# 1_4.net
KiCad netlist of a schematic drawn in Altium Designer
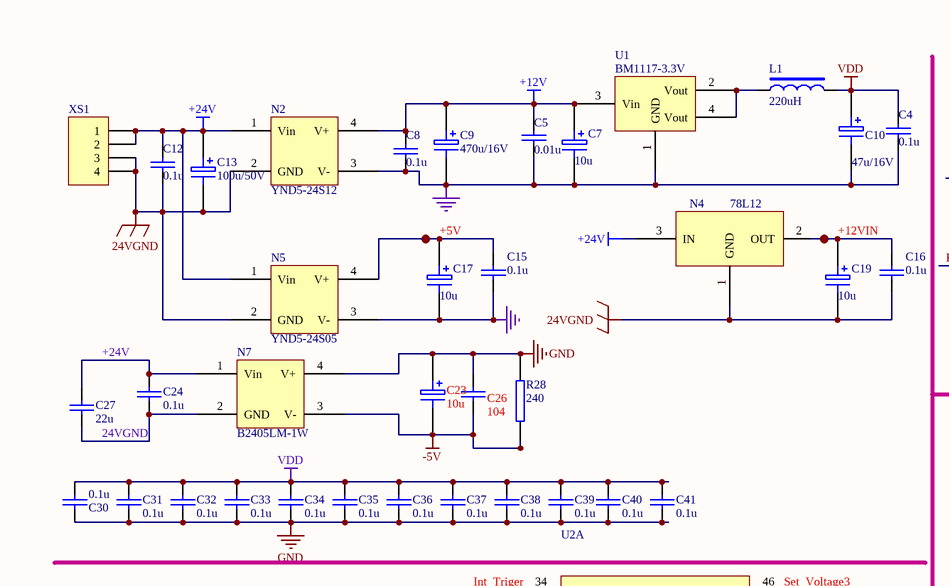
[diagram p0: 总控制板1控4.SchDoc, top left]
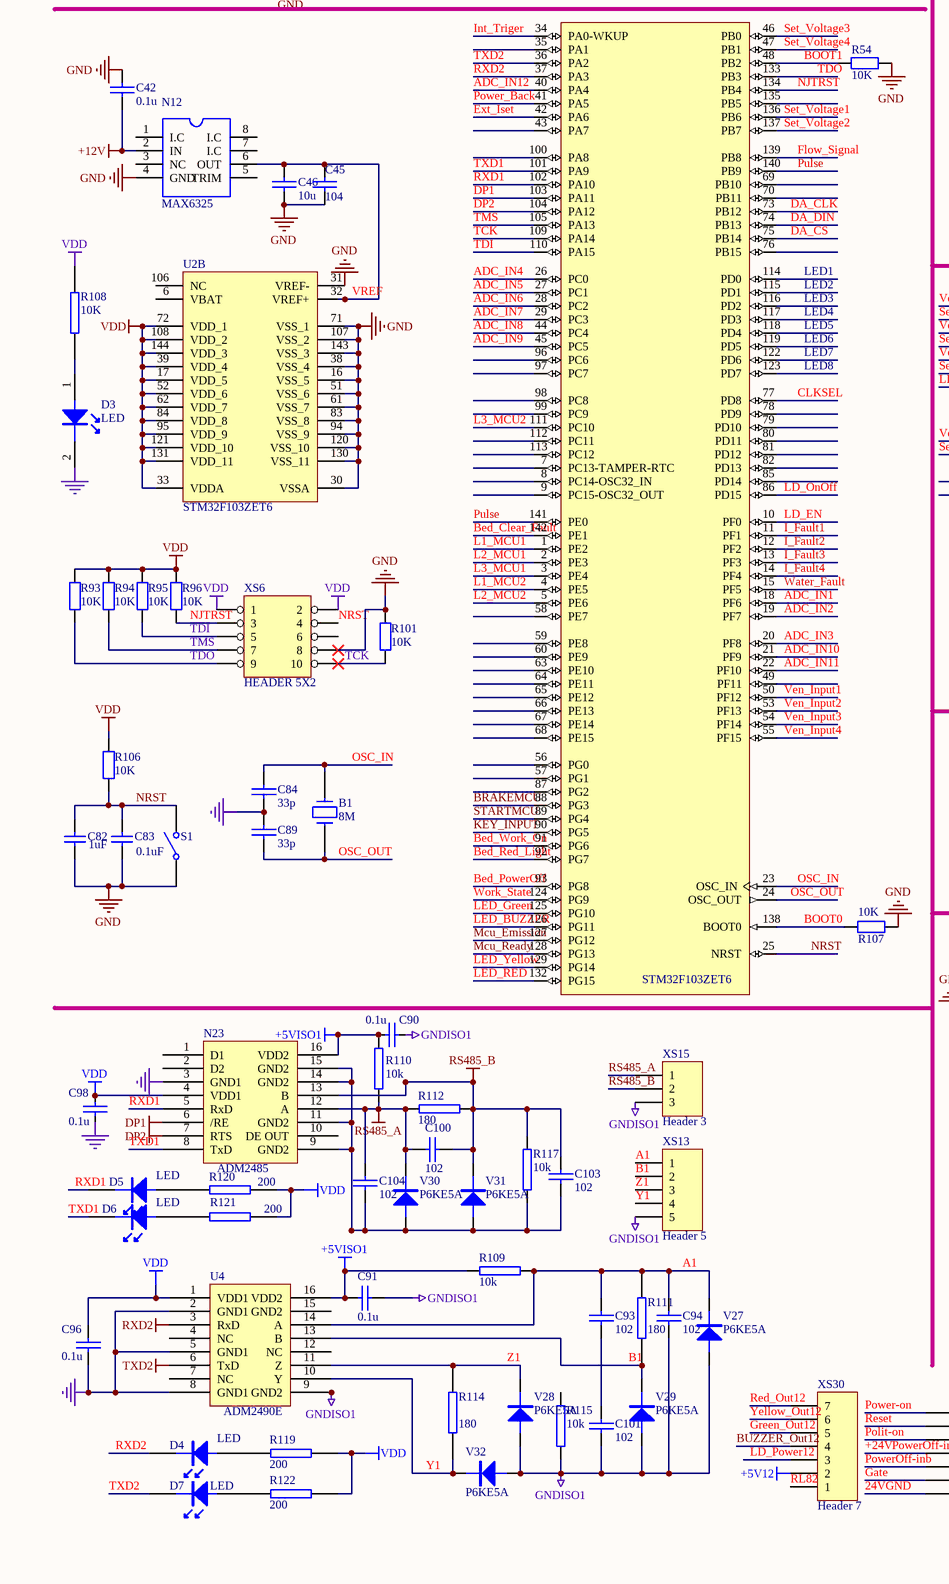
[diagram p1: 总控制板1控4.SchDoc, bottom left]
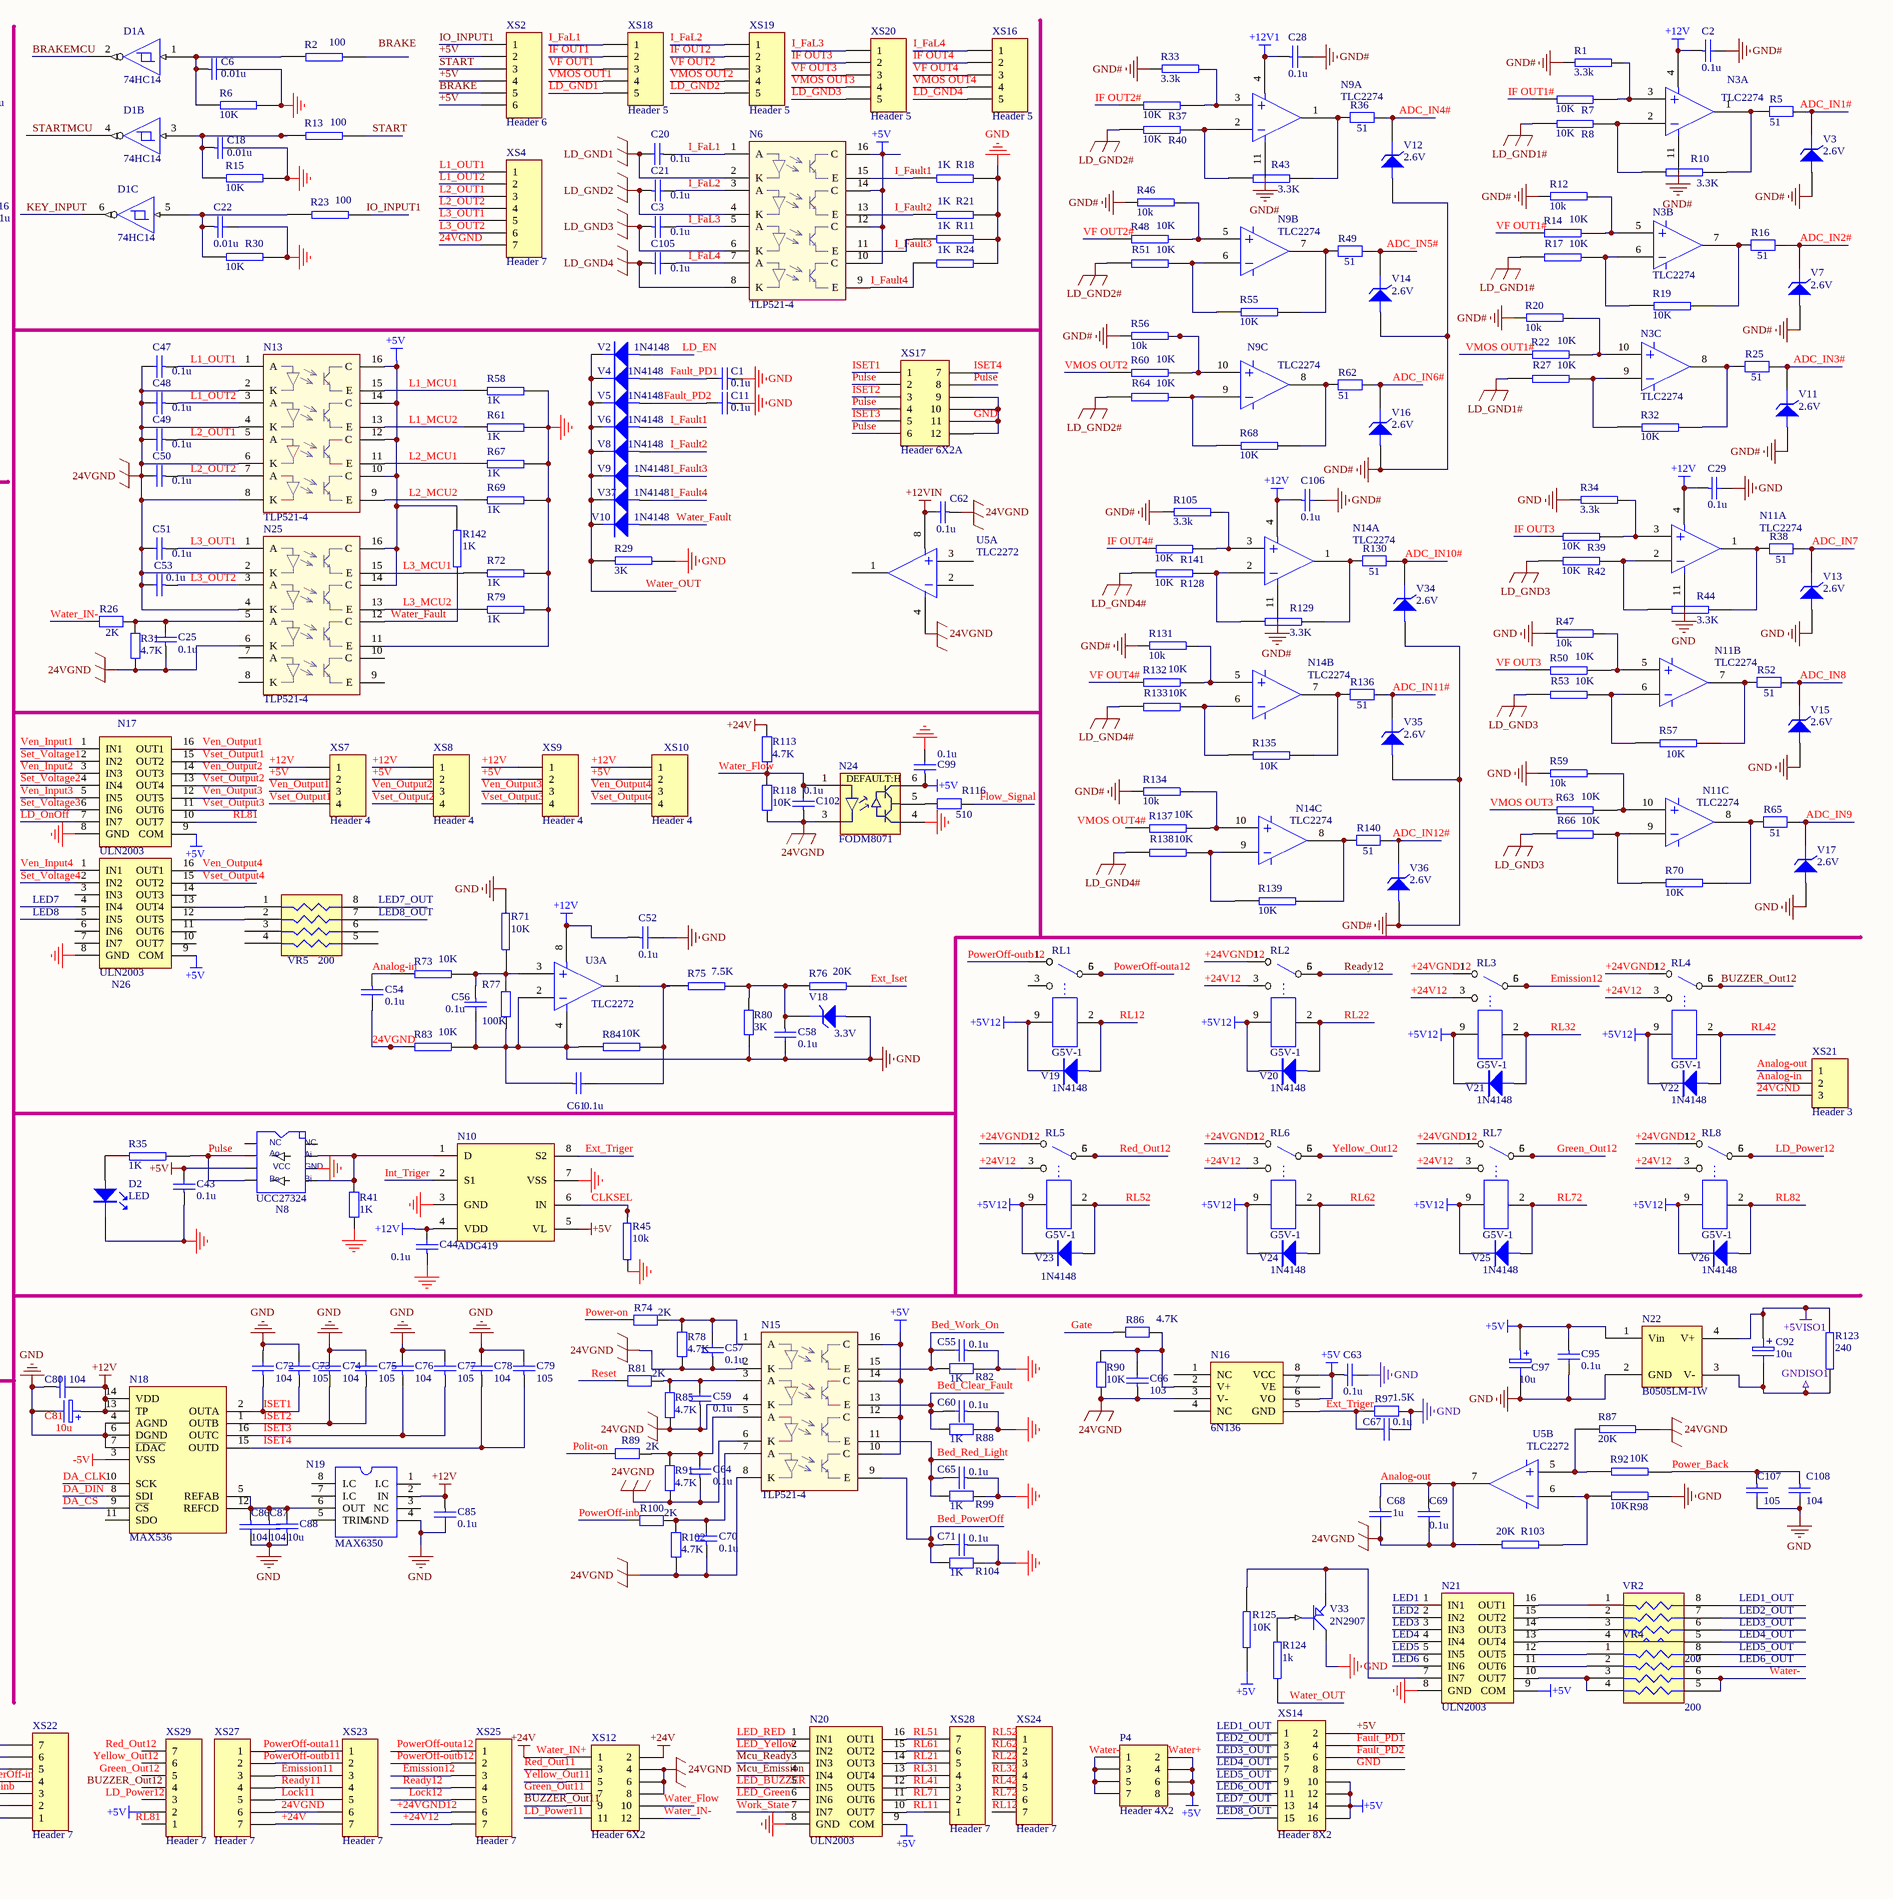
[diagram p2: 总控制板1控4.SchDoc, bottom right]

(export (version "E")
  (design (tool "Eeschema 10.0.6"))
  (components
    (comp (ref "B1")
      (value "8M")
      (footprint "CRY_SMB")
      (description "Crystal")
      (libsource (lib "*") (part "CRYSTAL"))
    )
    (comp (ref "C1") (value "0.1u") (footprint "0805") (libsource (lib "") (part "CAP_1")))
    (comp (ref "C2")
      (value "0.1u")
      (footprint "0805")
      (description "Capacitor")
      (libsource (lib "*") (part "CAP"))
    )
    (comp (ref "C3")
      (value "0.1u")
      (footprint "0805")
      (description "Capacitor")
      (libsource (lib "*") (part "CAP"))
    )
    (comp (ref "C4")
      (value "0.1u")
      (footprint "0805")
      (description "Capacitor")
      (libsource (lib "*") (part "CAP"))
    )
    (comp (ref "C5")
      (value "0.01u")
      (footprint "0805")
      (description "Capacitor")
      (libsource (lib "*") (part "CAP"))
    )
    (comp (ref "C6")
      (value "0.01u")
      (footprint "0805")
      (description "Capacitor")
      (libsource (lib "*") (part "CAP"))
    )
    (comp (ref "C7")
      (value "10u")
      (footprint "1206")
      (description "Electrolytic Capacitor")
      (libsource (lib "*") (part "ELECTRO1"))
    )
    (comp (ref "C8")
      (value "0.1u")
      (footprint "0805")
      (description "Capacitor")
      (libsource (lib "*") (part "CAP"))
    )
    (comp (ref "C9")
      (value "470u/16V")
      (footprint "3008")
      (description "Electrolytic Capacitor")
      (libsource (lib "*") (part "ELECTRO1"))
    )
    (comp (ref "C10")
      (value "47u/16V")
      (footprint "1206")
      (description "Electrolytic Capacitor")
      (libsource (lib "*") (part "ELECTRO1"))
    )
    (comp (ref "C11") (value "0.1u") (footprint "0805") (libsource (lib "") (part "CAP_1")))
    (comp (ref "C12")
      (value "0.1u")
      (footprint "0805")
      (description "Capacitor")
      (libsource (lib "*") (part "CAP"))
    )
    (comp (ref "C13")
      (value "100u/50V")
      (footprint "CD5-8")
      (description "Electrolytic Capacitor")
      (libsource (lib "*") (part "ELECTRO1"))
    )
    (comp (ref "C15") (value "0.1u") (footprint "0805") (libsource (lib "") (part "CAP_1")))
    (comp (ref "C16") (value "0.1u") (footprint "0805") (libsource (lib "") (part "CAP_1")))
    (comp (ref "C17")
      (value "10u")
      (footprint "1206")
      (description "Electrolytic Capacitor")
      (libsource (lib "*") (part "ELECTRO1"))
    )
    (comp (ref "C18")
      (value "0.01u")
      (footprint "0805")
      (description "Capacitor")
      (libsource (lib "*") (part "CAP"))
    )
    (comp (ref "C19")
      (value "10u")
      (footprint "1206")
      (description "Electrolytic Capacitor")
      (libsource (lib "*") (part "ELECTRO1"))
    )
    (comp (ref "C20")
      (value "0.1u")
      (footprint "0805")
      (description "Capacitor")
      (libsource (lib "*") (part "CAP"))
    )
    (comp (ref "C21")
      (value "0.1u")
      (footprint "0805")
      (description "Capacitor")
      (libsource (lib "*") (part "CAP"))
    )
    (comp (ref "C22")
      (value "0.01u")
      (footprint "0805")
      (description "Capacitor")
      (libsource (lib "*") (part "CAP"))
    )
    (comp (ref "C23")
      (value "10u")
      (footprint "1206")
      (description "Electrolytic Capacitor")
      (libsource (lib "*") (part "ELECTRO1"))
    )
    (comp (ref "C24")
      (value "0.1u")
      (footprint "0805")
      (description "Capacitor")
      (libsource (lib "*") (part "CAP"))
    )
    (comp (ref "C25") (value "0.1u") (footprint "0805") (libsource (lib "") (part "CAP_1")))
    (comp (ref "C26")
      (value "104")
      (footprint "0805")
      (description "Capacitor")
      (libsource (lib "*") (part "CAP"))
    )
    (comp (ref "C27")
      (value "22u")
      (footprint "1206")
      (description "Capacitor")
      (libsource (lib "*") (part "CAP"))
    )
    (comp (ref "C28")
      (value "0.1u")
      (footprint "0805")
      (description "Capacitor")
      (libsource (lib "*") (part "CAP"))
    )
    (comp (ref "C29")
      (value "0.1u")
      (footprint "0805")
      (description "Capacitor")
      (libsource (lib "*") (part "CAP"))
    )
    (comp (ref "C30")
      (value "0.1u")
      (footprint "0805")
      (description "Capacitor")
      (libsource (lib "*") (part "CAP"))
    )
    (comp (ref "C31")
      (value "0.1u")
      (footprint "0805")
      (description "Capacitor")
      (libsource (lib "*") (part "CAP"))
    )
    (comp (ref "C32")
      (value "0.1u")
      (footprint "0805")
      (description "Capacitor")
      (libsource (lib "*") (part "CAP"))
    )
    (comp (ref "C33")
      (value "0.1u")
      (footprint "0805")
      (description "Capacitor")
      (libsource (lib "*") (part "CAP"))
    )
    (comp (ref "C34")
      (value "0.1u")
      (footprint "0805")
      (description "Capacitor")
      (libsource (lib "*") (part "CAP"))
    )
    (comp (ref "C35")
      (value "0.1u")
      (footprint "0805")
      (description "Capacitor")
      (libsource (lib "*") (part "CAP"))
    )
    (comp (ref "C36")
      (value "0.1u")
      (footprint "0805")
      (description "Capacitor")
      (libsource (lib "*") (part "CAP"))
    )
    (comp (ref "C37")
      (value "0.1u")
      (footprint "0805")
      (description "Capacitor")
      (libsource (lib "*") (part "CAP"))
    )
    (comp (ref "C38")
      (value "0.1u")
      (footprint "0805")
      (description "Capacitor")
      (libsource (lib "*") (part "CAP"))
    )
    (comp (ref "C39")
      (value "0.1u")
      (footprint "0805")
      (description "Capacitor")
      (libsource (lib "*") (part "CAP"))
    )
    (comp (ref "C40")
      (value "0.1u")
      (footprint "0805")
      (description "Capacitor")
      (libsource (lib "*") (part "CAP"))
    )
    (comp (ref "C41")
      (value "0.1u")
      (footprint "0805")
      (description "Capacitor")
      (libsource (lib "*") (part "CAP"))
    )
    (comp (ref "C42") (value "0.1u") (footprint "0805") (libsource (lib "") (part "CAP_1")))
    (comp (ref "C43") (value "0.1u") (footprint "0805") (libsource (lib "") (part "CAP_1")))
    (comp (ref "C44") (value "0.1u") (footprint "0805") (libsource (lib "") (part "CAP_1")))
    (comp (ref "C45") (value "104") (footprint "0805") (libsource (lib "THT") (part "CAP")))
    (comp (ref "C46") (value "10u") (footprint "0805") (libsource (lib "") (part "CAP_1")))
    (comp (ref "C47")
      (value "0.1u")
      (footprint "0805")
      (description "Capacitor")
      (libsource (lib "*") (part "CAP"))
    )
    (comp (ref "C48")
      (value "0.1u")
      (footprint "0805")
      (description "Capacitor")
      (libsource (lib "*") (part "CAP"))
    )
    (comp (ref "C49")
      (value "0.1u")
      (footprint "0805")
      (description "Capacitor")
      (libsource (lib "*") (part "CAP"))
    )
    (comp (ref "C50")
      (value "0.1u")
      (footprint "0805")
      (description "Capacitor")
      (libsource (lib "*") (part "CAP"))
    )
    (comp (ref "C51")
      (value "0.1u")
      (footprint "0805")
      (description "Capacitor")
      (libsource (lib "*") (part "CAP"))
    )
    (comp (ref "C52")
      (value "0.1u")
      (footprint "0805")
      (description "Capacitor")
      (libsource (lib "*") (part "CAP"))
    )
    (comp (ref "C53")
      (value "0.1u")
      (footprint "0805")
      (description "Capacitor")
      (libsource (lib "*") (part "CAP"))
    )
    (comp (ref "C54")
      (value "0.1u")
      (footprint "0805")
      (description "Capacitor")
      (libsource (lib "*") (part "CAP"))
    )
    (comp (ref "C55") (value "0.1u") (footprint "0805") (libsource (lib "") (part "CAP_1")))
    (comp (ref "C56")
      (value "0.1u")
      (footprint "0805")
      (description "Capacitor")
      (libsource (lib "*") (part "CAP"))
    )
    (comp (ref "C57") (value "0.1u") (footprint "0805") (libsource (lib "") (part "CAP_1")))
    (comp (ref "C58")
      (value "0.1u")
      (footprint "0805")
      (description "Capacitor")
      (libsource (lib "*") (part "CAP"))
    )
    (comp (ref "C59") (value "0.1u") (footprint "0805") (libsource (lib "") (part "CAP_1")))
    (comp (ref "C60") (value "0.1u") (footprint "0805") (libsource (lib "") (part "CAP_1")))
    (comp (ref "C61")
      (value "0.1u")
      (footprint "0805")
      (description "Capacitor")
      (libsource (lib "*") (part "CAP"))
    )
    (comp (ref "C62")
      (value "0.1u")
      (footprint "0805")
      (description "Capacitor")
      (libsource (lib "*") (part "CAP"))
    )
    (comp (ref "C63")
      (value "0.1u")
      (footprint "0805")
      (description "Capacitor")
      (libsource (lib "*") (part "CAP"))
    )
    (comp (ref "C64") (value "0.1u") (footprint "0805") (libsource (lib "") (part "CAP_1")))
    (comp (ref "C65") (value "0.1u") (footprint "0805") (libsource (lib "") (part "CAP_1")))
    (comp (ref "C66") (value "103") (footprint "0805") (libsource (lib "") (part "CAP_1")))
    (comp (ref "C67") (value "0.1u") (footprint "0805") (libsource (lib "") (part "CAP_1")))
    (comp (ref "C68")
      (value "1u")
      (footprint "0805")
      (description "Capacitor")
      (libsource (lib "*") (part "CAP"))
    )
    (comp (ref "C69")
      (value "0.1u")
      (footprint "0805")
      (description "Capacitor")
      (libsource (lib "*") (part "CAP"))
    )
    (comp (ref "C70") (value "0.1u") (footprint "0805") (libsource (lib "") (part "CAP_1")))
    (comp (ref "C71") (value "0.1u") (footprint "0805") (libsource (lib "") (part "CAP_1")))
    (comp (ref "C72") (value "104") (footprint "0805") (libsource (lib "THT") (part "CAP")))
    (comp (ref "C73") (value "105") (footprint "0805") (libsource (lib "THT") (part "CAP")))
    (comp (ref "C74") (value "104") (footprint "0805") (libsource (lib "THT") (part "CAP")))
    (comp (ref "C75") (value "105") (footprint "0805") (libsource (lib "THT") (part "CAP")))
    (comp (ref "C76") (value "104") (footprint "0805") (libsource (lib "THT") (part "CAP")))
    (comp (ref "C77") (value "105") (footprint "0805") (libsource (lib "THT") (part "CAP")))
    (comp (ref "C78") (value "104") (footprint "0805") (libsource (lib "THT") (part "CAP")))
    (comp (ref "C79") (value "105") (footprint "0805") (libsource (lib "THT") (part "CAP")))
    (comp (ref "C80") (value "104") (footprint "0805") (libsource (lib "THT") (part "CAP")))
    (comp (ref "C81")
      (value "10u")
      (footprint "1206")
      (description "Electrolytic Capacitor")
      (libsource (lib "*") (part "ELECTRO1"))
    )
    (comp (ref "C82")
      (value "1uF")
      (footprint "0805")
      (description "Capacitor")
      (fields (field (name "PUBLISHER") "Altium Limited"))
      (libsource (lib "Miscellaneous Devices") (part "Cap"))
    )
    (comp (ref "C83")
      (value "0.1uF")
      (footprint "0805")
      (description "Capacitor")
      (fields (field (name "PUBLISHER") "Altium Limited"))
      (libsource (lib "Miscellaneous Devices") (part "Cap"))
    )
    (comp (ref "C84")
      (value "33p")
      (footprint "0805")
      (description "Capacitor")
      (libsource (lib "*") (part "CAP"))
    )
    (comp (ref "C85") (value "0.1u") (footprint "0805") (libsource (lib "") (part "CAP_1")))
    (comp (ref "C86") (value "104") (footprint "0805") (libsource (lib "THT") (part "CAP")))
    (comp (ref "C87") (value "104") (footprint "0805") (libsource (lib "THT") (part "CAP")))
    (comp (ref "C88") (value "10u") (footprint "0805") (libsource (lib "") (part "CAP_1")))
    (comp (ref "C89")
      (value "33p")
      (footprint "0805")
      (description "Capacitor")
      (libsource (lib "*") (part "CAP"))
    )
    (comp (ref "C90") (value "0.1u") (footprint "0805") (libsource (lib "") (part "CAP_2")))
    (comp (ref "C91")
      (value "0.1u")
      (footprint "0805")
      (description "Capacitor")
      (libsource (lib "*") (part "CAP"))
    )
    (comp (ref "C92")
      (value "10u")
      (footprint "1206")
      (description "Electrolytic Capacitor")
      (libsource (lib "*") (part "ELECTRO1"))
    )
    (comp (ref "C93")
      (value "102")
      (footprint "0805")
      (description "Capacitor")
      (libsource (lib "*") (part "CAP"))
    )
    (comp (ref "C94")
      (value "102")
      (footprint "0805")
      (description "Capacitor")
      (libsource (lib "*") (part "CAP"))
    )
    (comp (ref "C95")
      (value "0.1u")
      (footprint "0805")
      (description "Capacitor")
      (libsource (lib "*") (part "CAP"))
    )
    (comp (ref "C96")
      (value "0.1u")
      (footprint "0805")
      (description "Capacitor")
      (libsource (lib "*") (part "CAP"))
    )
    (comp (ref "C97")
      (value "10u")
      (footprint "1206")
      (description "Electrolytic Capacitor")
      (libsource (lib "*") (part "ELECTRO1"))
    )
    (comp (ref "C98") (value "0.1u") (footprint "0805") (libsource (lib "") (part "CAP_2")))
    (comp (ref "C99") (value "0.1u") (footprint "0805") (libsource (lib "") (part "CAP_1")))
    (comp (ref "C100")
      (value "102")
      (footprint "0805")
      (description "Capacitor")
      (libsource (lib "*") (part "CAP"))
    )
    (comp (ref "C101")
      (value "102")
      (footprint "0805")
      (description "Capacitor")
      (libsource (lib "*") (part "CAP"))
    )
    (comp (ref "C102") (value "0.1u") (footprint "0805") (libsource (lib "") (part "CAP_1")))
    (comp (ref "C103")
      (value "102")
      (footprint "0805")
      (description "Capacitor")
      (libsource (lib "*") (part "CAP"))
    )
    (comp (ref "C104")
      (value "102")
      (footprint "0805")
      (description "Capacitor")
      (libsource (lib "*") (part "CAP"))
    )
    (comp (ref "C105")
      (value "0.1u")
      (footprint "0805")
      (description "Capacitor")
      (libsource (lib "*") (part "CAP"))
    )
    (comp (ref "C106")
      (value "0.1u")
      (footprint "0805")
      (description "Capacitor")
      (libsource (lib "*") (part "CAP"))
    )
    (comp (ref "C107") (value "105") (footprint "0805") (libsource (lib "THT") (part "CAP")))
    (comp (ref "C108") (value "104") (footprint "0805") (libsource (lib "THT") (part "CAP")))
    (comp (ref "D1") (value "74HC14") (footprint "SO-14") (libsource (lib "*") (part "4584")))
    (comp (ref "D2") (value "LED") (footprint "1206A") (libsource (lib "*") (part "LED")))
    (comp (ref "D3") (value "LED") (footprint "1206A") (libsource (lib "") (part "LED_1")))
    (comp (ref "D4") (value "LED") (footprint "1206A") (libsource (lib "*") (part "LED")))
    (comp (ref "D5") (value "LED") (footprint "1206A") (libsource (lib "*") (part "LED")))
    (comp (ref "D6") (value "LED") (footprint "1206A") (libsource (lib "*") (part "LED")))
    (comp (ref "D7") (value "LED") (footprint "1206A") (libsource (lib "*") (part "LED")))
    (comp (ref "L1") (value "220uH") (footprint "1812") (libsource (lib "*") (part "L")))
    (comp (ref "N2") (value "YND5-24S12") (footprint "YND5") (libsource (lib "*") (part "B0505LM")))
    (comp (ref "N3") (value "TLC2274") (footprint "SO-14") (libsource (lib "*") (part "LM124")))
    (comp (ref "N4") (value "78L12") (footprint "TO-92_2") (libsource (lib "*") (part "VOL")))
    (comp (ref "N5") (value "YND5-24S05") (footprint "YND5") (libsource (lib "*") (part "B0505LM")))
    (comp (ref "N6")
      (value "TLP521-4")
      (footprint "ILEAD-16")
      (libsource (lib "work_ruilei") (part "TLP521-4"))
    )
    (comp (ref "N7") (value "B2405LM-1W") (footprint "B0505LM") (libsource (lib "*") (part "B0505LM")))
    (comp (ref "N8") (value "UCC27324") (footprint "SO-8") (libsource (lib "框图2") (part "UCC27324")))
    (comp (ref "N9") (value "TLC2274") (footprint "SO-14") (libsource (lib "*") (part "LM124")))
    (comp (ref "N10") (value "ADG419") (footprint "SO-8") (libsource (lib "40hz") (part "ADG419")))
    (comp (ref "N11") (value "TLC2274") (footprint "SO-14") (libsource (lib "*") (part "LM124")))
    (comp (ref "N12") (value "MAX6325") (footprint "SO-8") (libsource (lib "") (part "MAX6341_1")))
    (comp (ref "N13")
      (value "TLP521-4")
      (footprint "ILEAD-16")
      (libsource (lib "work_ruilei") (part "TLP521-4"))
    )
    (comp (ref "N14") (value "TLC2274") (footprint "SO-14") (libsource (lib "*") (part "LM124")))
    (comp (ref "N15")
      (value "TLP521-4")
      (footprint "ILEAD-16")
      (libsource (lib "work_ruilei") (part "TLP521-4"))
    )
    (comp (ref "N16") (value "6N136") (footprint "ILEAD-8") (libsource (lib "*") (part "HCPL2601")))
    (comp (ref "N17")
      (value "ULN2003")
      (footprint "SOIC127P600-16N")
      (libsource (lib "work_ruilei") (part "ULN2003A"))
    )
    (comp (ref "N18") (value "MAX536") (footprint "SOIC-16") (libsource (lib "work_ruilei") (part "MAX536")))
    (comp (ref "N19") (value "MAX6350") (footprint "SO-8") (libsource (lib "TH2") (part "MAX6341")))
    (comp (ref "N20")
      (value "ULN2003")
      (footprint "SOIC127P600-16N")
      (libsource (lib "work_ruilei") (part "ULN2003A"))
    )
    (comp (ref "N21")
      (value "ULN2003")
      (footprint "SOIC127P600-16N")
      (libsource (lib "work_ruilei") (part "ULN2003A"))
    )
    (comp (ref "N22") (value "B0505LM-1W") (footprint "B0505LM") (libsource (lib "*") (part "B0505LM")))
    (comp (ref "N23") (value "ADM2485") (footprint "SOIC-16") (libsource (lib "C8051F021") (part "ADM2485")))
    (comp (ref "N24") (value "FODM8071") (footprint "SO-8") (libsource (lib "work_ruilei") (part "FODM8071")))
    (comp (ref "N25")
      (value "TLP521-4")
      (footprint "ILEAD-16")
      (libsource (lib "work_ruilei") (part "TLP521-4"))
    )
    (comp (ref "N26")
      (value "ULN2003")
      (footprint "SOIC127P600-16N")
      (libsource (lib "work_ruilei") (part "ULN2003A"))
    )
    (comp (ref "P4")
      (value "Header 4X2")
      (footprint "HDR2X4")
      (description "Header, 4-Pin, Dual row")
      (fields (field (name "PUBLISHER") "Altium Limited"))
      (libsource (lib "Miscellaneous Connectors") (part "Header 4X2"))
    )
    (comp (ref "R1") (value "3.3k") (footprint "0805") (libsource (lib "*") (part "R")))
    (comp (ref "R2") (value "100") (footprint "0805") (libsource (lib "*") (part "RES2")))
    (comp (ref "R5")
      (value "51")
      (footprint "0805")
      (description "Resistor")
      (fields (field (name "PUBLISHER") "Altium Limited"))
      (libsource (lib "") (part "Res2_2"))
    )
    (comp (ref "R6") (value "10K") (footprint "0805") (libsource (lib "*") (part "RES2")))
    (comp (ref "R7") (value "10K") (footprint "0805") (libsource (lib "*") (part "RES2")))
    (comp (ref "R8") (value "10K") (footprint "0805") (libsource (lib "*") (part "RES2")))
    (comp (ref "R10") (value "3.3K") (footprint "0805") (libsource (lib "*") (part "RES2")))
    (comp (ref "R11") (value "1K") (footprint "0805") (libsource (lib "*") (part "RES2")))
    (comp (ref "R12") (value "10k") (footprint "0805") (libsource (lib "*") (part "R")))
    (comp (ref "R13") (value "100") (footprint "0805") (libsource (lib "*") (part "RES2")))
    (comp (ref "R14") (value "10K") (footprint "0805") (libsource (lib "*") (part "RES2")))
    (comp (ref "R15") (value "10K") (footprint "0805") (libsource (lib "*") (part "RES2")))
    (comp (ref "R16")
      (value "51")
      (footprint "0805")
      (description "Resistor")
      (fields (field (name "PUBLISHER") "Altium Limited"))
      (libsource (lib "") (part "Res2_2"))
    )
    (comp (ref "R17") (value "10K") (footprint "0805") (libsource (lib "*") (part "RES2")))
    (comp (ref "R18") (value "1K") (footprint "0805") (libsource (lib "*") (part "RES2")))
    (comp (ref "R19") (value "10K") (footprint "0805") (libsource (lib "*") (part "RES2")))
    (comp (ref "R20") (value "10k") (footprint "0805") (libsource (lib "*") (part "R")))
    (comp (ref "R21") (value "1K") (footprint "0805") (libsource (lib "*") (part "RES2")))
    (comp (ref "R22") (value "10K") (footprint "0805") (libsource (lib "*") (part "RES2")))
    (comp (ref "R23") (value "100") (footprint "0805") (libsource (lib "*") (part "RES2")))
    (comp (ref "R24") (value "1K") (footprint "0805") (libsource (lib "*") (part "RES2")))
    (comp (ref "R25")
      (value "51")
      (footprint "0805")
      (description "Resistor")
      (fields (field (name "PUBLISHER") "Altium Limited"))
      (libsource (lib "") (part "Res2_2"))
    )
    (comp (ref "R26")
      (value "2K")
      (footprint "0805")
      (description "Resistor")
      (fields (field (name "PUBLISHER") "Altium Limited"))
      (libsource (lib "") (part "Res2_2"))
    )
    (comp (ref "R27") (value "10K") (footprint "0805") (libsource (lib "*") (part "RES2")))
    (comp (ref "R28") (value "240") (footprint "1206") (libsource (lib "*") (part "RES2")))
    (comp (ref "R29") (value "3K") (footprint "0805") (libsource (lib "*") (part "RES2")))
    (comp (ref "R30") (value "10K") (footprint "0805") (libsource (lib "*") (part "RES2")))
    (comp (ref "R31")
      (value "4.7K")
      (footprint "0805")
      (description "Resistor")
      (fields (field (name "PUBLISHER") "Altium Limited"))
      (libsource (lib "Miscellaneous Devices") (part "Res2"))
    )
    (comp (ref "R32") (value "10K") (footprint "0805") (libsource (lib "*") (part "RES2")))
    (comp (ref "R33") (value "3.3k") (footprint "0805") (libsource (lib "*") (part "R")))
    (comp (ref "R34") (value "3.3k") (footprint "0805") (libsource (lib "*") (part "R")))
    (comp (ref "R35") (value "1K") (footprint "0805") (libsource (lib "*") (part "RES2")))
    (comp (ref "R36")
      (value "51")
      (footprint "0805")
      (description "Resistor")
      (fields (field (name "PUBLISHER") "Altium Limited"))
      (libsource (lib "") (part "Res2_2"))
    )
    (comp (ref "R37") (value "10K") (footprint "0805") (libsource (lib "*") (part "RES2")))
    (comp (ref "R38")
      (value "51")
      (footprint "0805")
      (description "Resistor")
      (fields (field (name "PUBLISHER") "Altium Limited"))
      (libsource (lib "") (part "Res2_2"))
    )
    (comp (ref "R39") (value "10K") (footprint "0805") (libsource (lib "*") (part "RES2")))
    (comp (ref "R40") (value "10K") (footprint "0805") (libsource (lib "*") (part "RES2")))
    (comp (ref "R41")
      (value "1K")
      (footprint "0805")
      (description "Resistor")
      (fields (field (name "PUBLISHER") "Altium Limited"))
      (libsource (lib "Miscellaneous Devices") (part "Res2"))
    )
    (comp (ref "R42") (value "10K") (footprint "0805") (libsource (lib "*") (part "RES2")))
    (comp (ref "R43") (value "3.3K") (footprint "0805") (libsource (lib "*") (part "RES2")))
    (comp (ref "R44") (value "3.3K") (footprint "0805") (libsource (lib "*") (part "RES2")))
    (comp (ref "R45") (value "10k") (footprint "0805") (libsource (lib "") (part "R_1")))
    (comp (ref "R46") (value "10k") (footprint "0805") (libsource (lib "*") (part "R")))
    (comp (ref "R47") (value "10k") (footprint "0805") (libsource (lib "*") (part "R")))
    (comp (ref "R48") (value "10K") (footprint "0805") (libsource (lib "*") (part "RES2")))
    (comp (ref "R49")
      (value "51")
      (footprint "0805")
      (description "Resistor")
      (fields (field (name "PUBLISHER") "Altium Limited"))
      (libsource (lib "") (part "Res2_2"))
    )
    (comp (ref "R50") (value "10K") (footprint "0805") (libsource (lib "*") (part "RES2")))
    (comp (ref "R51") (value "10K") (footprint "0805") (libsource (lib "*") (part "RES2")))
    (comp (ref "R52")
      (value "51")
      (footprint "0805")
      (description "Resistor")
      (fields (field (name "PUBLISHER") "Altium Limited"))
      (libsource (lib "") (part "Res2_2"))
    )
    (comp (ref "R53") (value "10K") (footprint "0805") (libsource (lib "*") (part "RES2")))
    (comp (ref "R54")
      (value "10K")
      (footprint "0805")
      (description "Resistor")
      (fields (field (name "PUBLISHER") "Altium Limited"))
      (libsource (lib "") (part "Res2_2"))
    )
    (comp (ref "R55") (value "10K") (footprint "0805") (libsource (lib "*") (part "RES2")))
    (comp (ref "R56") (value "10k") (footprint "0805") (libsource (lib "*") (part "R")))
    (comp (ref "R57") (value "10K") (footprint "0805") (libsource (lib "*") (part "RES2")))
    (comp (ref "R58") (value "1K") (footprint "0805") (libsource (lib "*") (part "RES2")))
    (comp (ref "R59") (value "10k") (footprint "0805") (libsource (lib "*") (part "R")))
    (comp (ref "R60") (value "10K") (footprint "0805") (libsource (lib "*") (part "RES2")))
    (comp (ref "R61") (value "1K") (footprint "0805") (libsource (lib "*") (part "RES2")))
    (comp (ref "R62")
      (value "51")
      (footprint "0805")
      (description "Resistor")
      (fields (field (name "PUBLISHER") "Altium Limited"))
      (libsource (lib "") (part "Res2_2"))
    )
    (comp (ref "R63") (value "10K") (footprint "0805") (libsource (lib "*") (part "RES2")))
    (comp (ref "R64") (value "10K") (footprint "0805") (libsource (lib "*") (part "RES2")))
    (comp (ref "R65")
      (value "51")
      (footprint "0805")
      (description "Resistor")
      (fields (field (name "PUBLISHER") "Altium Limited"))
      (libsource (lib "") (part "Res2_2"))
    )
    (comp (ref "R66") (value "10K") (footprint "0805") (libsource (lib "*") (part "RES2")))
    (comp (ref "R67") (value "1K") (footprint "0805") (libsource (lib "*") (part "RES2")))
    (comp (ref "R68") (value "10K") (footprint "0805") (libsource (lib "*") (part "RES2")))
    (comp (ref "R69") (value "1K") (footprint "0805") (libsource (lib "*") (part "RES2")))
    (comp (ref "R70") (value "10K") (footprint "0805") (libsource (lib "*") (part "RES2")))
    (comp (ref "R71") (value "10K") (footprint "0805") (libsource (lib "*") (part "RES2")))
    (comp (ref "R72") (value "1K") (footprint "0805") (libsource (lib "*") (part "RES2")))
    (comp (ref "R73") (value "10K") (footprint "0805") (libsource (lib "*") (part "RES2")))
    (comp (ref "R74")
      (value "2K")
      (footprint "0805")
      (description "Resistor")
      (fields (field (name "PUBLISHER") "Altium Limited"))
      (libsource (lib "") (part "Res2_2"))
    )
    (comp (ref "R75") (value "7.5K") (footprint "0805") (libsource (lib "*") (part "RES2")))
    (comp (ref "R76") (value "20K") (footprint "0805") (libsource (lib "*") (part "RES2")))
    (comp (ref "R77")
      (value "100K")
      (footprint "0805")
      (description "Resistor")
      (fields (field (name "PUBLISHER") "Altium Limited"))
      (libsource (lib "") (part "Res2_3"))
    )
    (comp (ref "R78")
      (value "4.7K")
      (footprint "0805")
      (description "Resistor")
      (fields (field (name "PUBLISHER") "Altium Limited"))
      (libsource (lib "Miscellaneous Devices") (part "Res2"))
    )
    (comp (ref "R79") (value "1K") (footprint "0805") (libsource (lib "*") (part "RES2")))
    (comp (ref "R80")
      (value "3K")
      (footprint "0805")
      (description "Resistor")
      (fields (field (name "PUBLISHER") "Altium Limited"))
      (libsource (lib "Miscellaneous Devices") (part "Res2"))
    )
    (comp (ref "R81")
      (value "2K")
      (footprint "0805")
      (description "Resistor")
      (fields (field (name "PUBLISHER") "Altium Limited"))
      (libsource (lib "") (part "Res2_2"))
    )
    (comp (ref "R82")
      (value "1K")
      (footprint "0805")
      (description "Resistor")
      (fields (field (name "PUBLISHER") "Altium Limited"))
      (libsource (lib "") (part "Res2_1"))
    )
    (comp (ref "R83") (value "10K") (footprint "0805") (libsource (lib "*") (part "RES2")))
    (comp (ref "R84") (value "10K") (footprint "0805") (libsource (lib "*") (part "RES2")))
    (comp (ref "R85")
      (value "4.7K")
      (footprint "0805")
      (description "Resistor")
      (fields (field (name "PUBLISHER") "Altium Limited"))
      (libsource (lib "Miscellaneous Devices") (part "Res2"))
    )
    (comp (ref "R86")
      (value "4.7K")
      (footprint "1206")
      (description "Resistor")
      (fields (field (name "PUBLISHER") "Altium Limited"))
      (libsource (lib "") (part "Res2_2"))
    )
    (comp (ref "R87") (value "20K") (footprint "0805") (libsource (lib "") (part "RES2_2")))
    (comp (ref "R88")
      (value "1K")
      (footprint "0805")
      (description "Resistor")
      (fields (field (name "PUBLISHER") "Altium Limited"))
      (libsource (lib "") (part "Res2_1"))
    )
    (comp (ref "R89")
      (value "2K")
      (footprint "0805")
      (description "Resistor")
      (fields (field (name "PUBLISHER") "Altium Limited"))
      (libsource (lib "") (part "Res2_2"))
    )
    (comp (ref "R90")
      (value "10K")
      (footprint "0805")
      (description "Resistor")
      (fields (field (name "PUBLISHER") "Altium Limited"))
      (libsource (lib "Miscellaneous Devices") (part "Res2"))
    )
    (comp (ref "R91")
      (value "4.7K")
      (footprint "0805")
      (description "Resistor")
      (fields (field (name "PUBLISHER") "Altium Limited"))
      (libsource (lib "Miscellaneous Devices") (part "Res2"))
    )
    (comp (ref "R92") (value "10K") (footprint "0805") (libsource (lib "*") (part "RES2")))
    (comp (ref "R93")
      (value "10K")
      (footprint "0805")
      (description "Resistor")
      (fields (field (name "PUBLISHER") "Altium Limited"))
      (libsource (lib "Miscellaneous Devices") (part "Res2"))
    )
    (comp (ref "R94")
      (value "10K")
      (footprint "0805")
      (description "Resistor")
      (fields (field (name "PUBLISHER") "Altium Limited"))
      (libsource (lib "Miscellaneous Devices") (part "Res2"))
    )
    (comp (ref "R95")
      (value "10K")
      (footprint "0805")
      (description "Resistor")
      (fields (field (name "PUBLISHER") "Altium Limited"))
      (libsource (lib "Miscellaneous Devices") (part "Res2"))
    )
    (comp (ref "R96")
      (value "10K")
      (footprint "0805")
      (description "Resistor")
      (fields (field (name "PUBLISHER") "Altium Limited"))
      (libsource (lib "Miscellaneous Devices") (part "Res2"))
    )
    (comp (ref "R97")
      (value "1.5K")
      (footprint "0805")
      (description "Resistor")
      (fields (field (name "PUBLISHER") "Altium Limited"))
      (libsource (lib "") (part "Res2_1"))
    )
    (comp (ref "R98") (value "10K") (footprint "0805") (libsource (lib "*") (part "RES2")))
    (comp (ref "R99")
      (value "1K")
      (footprint "0805")
      (description "Resistor")
      (fields (field (name "PUBLISHER") "Altium Limited"))
      (libsource (lib "") (part "Res2_1"))
    )
    (comp (ref "R100")
      (value "2K")
      (footprint "0805")
      (description "Resistor")
      (fields (field (name "PUBLISHER") "Altium Limited"))
      (libsource (lib "") (part "Res2_2"))
    )
    (comp (ref "R101")
      (value "10K")
      (footprint "0805")
      (description "Resistor")
      (fields (field (name "PUBLISHER") "Altium Limited"))
      (libsource (lib "Miscellaneous Devices") (part "Res2"))
    )
    (comp (ref "R102")
      (value "4.7K")
      (footprint "0805")
      (description "Resistor")
      (fields (field (name "PUBLISHER") "Altium Limited"))
      (libsource (lib "Miscellaneous Devices") (part "Res2"))
    )
    (comp (ref "R103") (value "20K") (footprint "0805") (libsource (lib "*") (part "RES2")))
    (comp (ref "R104")
      (value "1K")
      (footprint "0805")
      (description "Resistor")
      (fields (field (name "PUBLISHER") "Altium Limited"))
      (libsource (lib "") (part "Res2_1"))
    )
    (comp (ref "R105") (value "3.3k") (footprint "0805") (libsource (lib "*") (part "R")))
    (comp (ref "R106")
      (value "10K")
      (footprint "0805")
      (description "Resistor")
      (fields (field (name "Comment") "Res2") (field (name "PUBLISHER") "Altium Limited"))
      (libsource (lib "") (part "Res2_3"))
    )
    (comp (ref "R107")
      (value "10K")
      (footprint "0805")
      (description "Resistor")
      (fields (field (name "PUBLISHER") "Altium Limited"))
      (libsource (lib "") (part "Res2_2"))
    )
    (comp (ref "R108") (value "10K") (footprint "0805") (libsource (lib "*") (part "RES2")))
    (comp (ref "R109") (value "10k") (footprint "0805") (libsource (lib "") (part "R_1")))
    (comp (ref "R110") (value "10k") (footprint "0805") (libsource (lib "") (part "R_1")))
    (comp (ref "R111") (value "180") (footprint "1206") (libsource (lib "*") (part "RES2")))
    (comp (ref "R112") (value "180") (footprint "1206") (libsource (lib "") (part "RES2_1")))
    (comp (ref "R113")
      (value "4.7K")
      (footprint "0805")
      (description "Resistor")
      (fields (field (name "PUBLISHER") "Altium Limited"))
      (libsource (lib "") (part "Res2_4"))
    )
    (comp (ref "R114") (value "180") (footprint "1206") (libsource (lib "*") (part "RES2")))
    (comp (ref "R115") (value "10k") (footprint "0805") (libsource (lib "") (part "R_1")))
    (comp (ref "R116")
      (value "510")
      (footprint "0805")
      (description "Resistor")
      (fields (field (name "PUBLISHER") "Altium Limited"))
      (libsource (lib "") (part "Res2_2"))
    )
    (comp (ref "R117") (value "10k") (footprint "0805") (libsource (lib "") (part "R_1")))
    (comp (ref "R118")
      (value "10K")
      (footprint "0805")
      (description "Resistor")
      (fields (field (name "PUBLISHER") "Altium Limited"))
      (libsource (lib "Miscellaneous Devices") (part "Res2"))
    )
    (comp (ref "R119") (value "200") (footprint "0805") (libsource (lib "*") (part "RES2")))
    (comp (ref "R120") (value "200") (footprint "0805") (libsource (lib "*") (part "RES2")))
    (comp (ref "R121") (value "200") (footprint "0805") (libsource (lib "*") (part "RES2")))
    (comp (ref "R122") (value "200") (footprint "0805") (libsource (lib "*") (part "RES2")))
    (comp (ref "R123") (value "240") (footprint "1206") (libsource (lib "*") (part "RES2")))
    (comp (ref "R124") (value "1k") (footprint "1206") (libsource (lib "*") (part "RES2")))
    (comp (ref "R125") (value "10K") (footprint "0805") (libsource (lib "") (part "RES2_2")))
    (comp (ref "R128") (value "10K") (footprint "0805") (libsource (lib "*") (part "RES2")))
    (comp (ref "R129") (value "3.3K") (footprint "0805") (libsource (lib "*") (part "RES2")))
    (comp (ref "R130")
      (value "51")
      (footprint "0805")
      (description "Resistor")
      (fields (field (name "PUBLISHER") "Altium Limited"))
      (libsource (lib "") (part "Res2_2"))
    )
    (comp (ref "R131") (value "10k") (footprint "0805") (libsource (lib "*") (part "R")))
    (comp (ref "R132") (value "10K") (footprint "0805") (libsource (lib "*") (part "RES2")))
    (comp (ref "R133") (value "10K") (footprint "0805") (libsource (lib "*") (part "RES2")))
    (comp (ref "R134") (value "10k") (footprint "0805") (libsource (lib "*") (part "R")))
    (comp (ref "R135") (value "10K") (footprint "0805") (libsource (lib "*") (part "RES2")))
    (comp (ref "R136")
      (value "51")
      (footprint "0805")
      (description "Resistor")
      (fields (field (name "PUBLISHER") "Altium Limited"))
      (libsource (lib "") (part "Res2_2"))
    )
    (comp (ref "R137") (value "10K") (footprint "0805") (libsource (lib "*") (part "RES2")))
    (comp (ref "R138") (value "10K") (footprint "0805") (libsource (lib "*") (part "RES2")))
    (comp (ref "R139") (value "10K") (footprint "0805") (libsource (lib "*") (part "RES2")))
    (comp (ref "R140")
      (value "51")
      (footprint "0805")
      (description "Resistor")
      (fields (field (name "PUBLISHER") "Altium Limited"))
      (libsource (lib "") (part "Res2_2"))
    )
    (comp (ref "R141") (value "10K") (footprint "0805") (libsource (lib "*") (part "RES2")))
    (comp (ref "R142") (value "1K") (footprint "0805") (libsource (lib "") (part "RES2_2")))
    (comp (ref "RL1") (value "G5V-1") (footprint "G5V-1") (libsource (lib "work_ruilei") (part "G5V-1")))
    (comp (ref "RL2") (value "G5V-1") (footprint "G5V-1") (libsource (lib "work_ruilei") (part "G5V-1")))
    (comp (ref "RL3") (value "G5V-1") (footprint "G5V-1") (libsource (lib "work_ruilei") (part "G5V-1")))
    (comp (ref "RL4") (value "G5V-1") (footprint "G5V-1") (libsource (lib "work_ruilei") (part "G5V-1")))
    (comp (ref "RL5") (value "G5V-1") (footprint "G5V-1") (libsource (lib "work_ruilei") (part "G5V-1")))
    (comp (ref "RL6") (value "G5V-1") (footprint "G5V-1") (libsource (lib "work_ruilei") (part "G5V-1")))
    (comp (ref "RL7") (value "G5V-1") (footprint "G5V-1") (libsource (lib "work_ruilei") (part "G5V-1")))
    (comp (ref "RL8") (value "G5V-1") (footprint "G5V-1") (libsource (lib "work_ruilei") (part "G5V-1")))
    (comp (ref "S1")
      (value "SW-SPST")
      (footprint "KEY_3*6*2.5")
      (description "Single-Pole, Single-Throw Switch")
      (fields (field (name "PUBLISHER") "Altium Limited"))
      (libsource (lib "Miscellaneous Devices") (part "SW-SPST"))
    )
    (comp (ref "U1") (value "BM1117-3.3V") (footprint "SOT-223") (libsource (lib "*") (part "BM1117")))
    (comp (ref "U2")
      (value "STM32F103ZET6")
      (footprint "LQFP144_N")
      (libsource (lib "STMicroelectronics STM32 F1") (part "STM32F103ZET6"))
    )
    (comp (ref "U3") (value "TLC2272") (footprint "SO-8") (libsource (lib "*") (part "1458")))
    (comp (ref "U4") (value "ADM2490E") (footprint "SOIC-16") (libsource (lib "*") (part "ADM2490E")))
    (comp (ref "U5") (value "TLC2272") (footprint "SO-8") (libsource (lib "*") (part "1458")))
    (comp (ref "V2") (value "1N4148") (footprint "1206A") (libsource (lib "*") (part "D")))
    (comp (ref "V3")
      (value "2.6V")
      (footprint "1206A")
      (description "Zener Diode")
      (libsource (lib "*") (part "ZENER3"))
    )
    (comp (ref "V4") (value "1N4148") (footprint "1206A") (libsource (lib "*") (part "D")))
    (comp (ref "V5") (value "1N4148") (footprint "1206A") (libsource (lib "*") (part "D")))
    (comp (ref "V6") (value "1N4148") (footprint "1206A") (libsource (lib "*") (part "D")))
    (comp (ref "V7")
      (value "2.6V")
      (footprint "1206A")
      (description "Zener Diode")
      (libsource (lib "*") (part "ZENER3"))
    )
    (comp (ref "V8") (value "1N4148") (footprint "1206A") (libsource (lib "*") (part "D")))
    (comp (ref "V9") (value "1N4148") (footprint "1206A") (libsource (lib "*") (part "D")))
    (comp (ref "V10") (value "1N4148") (footprint "1206A") (libsource (lib "*") (part "D")))
    (comp (ref "V11")
      (value "2.6V")
      (footprint "1206A")
      (description "Zener Diode")
      (libsource (lib "*") (part "ZENER3"))
    )
    (comp (ref "V12")
      (value "2.6V")
      (footprint "1206A")
      (description "Zener Diode")
      (libsource (lib "*") (part "ZENER3"))
    )
    (comp (ref "V13")
      (value "2.6V")
      (footprint "1206A")
      (description "Zener Diode")
      (libsource (lib "*") (part "ZENER3"))
    )
    (comp (ref "V14")
      (value "2.6V")
      (footprint "1206A")
      (description "Zener Diode")
      (libsource (lib "*") (part "ZENER3"))
    )
    (comp (ref "V15")
      (value "2.6V")
      (footprint "1206A")
      (description "Zener Diode")
      (libsource (lib "*") (part "ZENER3"))
    )
    (comp (ref "V16")
      (value "2.6V")
      (footprint "1206A")
      (description "Zener Diode")
      (libsource (lib "*") (part "ZENER3"))
    )
    (comp (ref "V17")
      (value "2.6V")
      (footprint "1206A")
      (description "Zener Diode")
      (libsource (lib "*") (part "ZENER3"))
    )
    (comp (ref "V18")
      (value "3.3V")
      (footprint "1206A")
      (description "Zener Diode")
      (libsource (lib "*") (part "ZENER3"))
    )
    (comp (ref "V19") (value "1N4148") (footprint "1206A") (libsource (lib "") (part "D_1")))
    (comp (ref "V20") (value "1N4148") (footprint "1206A") (libsource (lib "") (part "D_1")))
    (comp (ref "V21") (value "1N4148") (footprint "1206A") (libsource (lib "") (part "D_1")))
    (comp (ref "V22") (value "1N4148") (footprint "1206A") (libsource (lib "") (part "D_1")))
    (comp (ref "V23") (value "1N4148") (footprint "1206A") (libsource (lib "") (part "D_1")))
    (comp (ref "V24") (value "1N4148") (footprint "1206A") (libsource (lib "") (part "D_1")))
    (comp (ref "V25") (value "1N4148") (footprint "1206A") (libsource (lib "") (part "D_1")))
    (comp (ref "V26") (value "1N4148") (footprint "1206A") (libsource (lib "") (part "D_1")))
    (comp (ref "V27") (value "P6KE5A") (footprint "1206-D") (libsource (lib "*") (part "DIODE")))
    (comp (ref "V28") (value "P6KE5A") (footprint "1206-D") (libsource (lib "*") (part "DIODE")))
    (comp (ref "V29") (value "P6KE5A") (footprint "1206-D") (libsource (lib "*") (part "DIODE")))
    (comp (ref "V30") (value "P6KE5A") (footprint "1206-D") (libsource (lib "*") (part "DIODE")))
    (comp (ref "V31") (value "P6KE5A") (footprint "1206-D") (libsource (lib "*") (part "DIODE")))
    (comp (ref "V32") (value "P6KE5A") (footprint "1206-D") (libsource (lib "*") (part "DIODE")))
    (comp (ref "V33") (value "2N2907") (footprint "SOT-23") (libsource (lib "TH1") (part "PNP2")))
    (comp (ref "V34")
      (value "2.6V")
      (footprint "1206A")
      (description "Zener Diode")
      (libsource (lib "*") (part "ZENER3"))
    )
    (comp (ref "V35")
      (value "2.6V")
      (footprint "1206A")
      (description "Zener Diode")
      (libsource (lib "*") (part "ZENER3"))
    )
    (comp (ref "V36")
      (value "2.6V")
      (footprint "1206A")
      (description "Zener Diode")
      (libsource (lib "*") (part "ZENER3"))
    )
    (comp (ref "V37") (value "1N4148") (footprint "1206A") (libsource (lib "*") (part "D")))
    (comp (ref "VR2") (value "200") (footprint "MINZIP") (libsource (lib "bom9200") (part "RN-742")))
    (comp (ref "VR4") (value "200") (footprint "MINZIP") (libsource (lib "bom9200") (part "RN-742")))
    (comp (ref "VR5") (value "200") (footprint "MINZIP") (libsource (lib "bom9200") (part "RN-742")))
    (comp (ref "XS1")
      (value "Header 4")
      (footprint "SIP-4")
      (description "Header, 4-Pin")
      (fields (field (name "PUBLISHER") "Altium Limited"))
      (libsource (lib "") (part "Header 4_1"))
    )
    (comp (ref "XS2")
      (value "Header 6")
      (footprint "SIP-6")
      (description "Header, 6-Pin")
      (fields (field (name "PUBLISHER") "Altium Limited"))
      (libsource (lib "Miscellaneous Connectors") (part "Header 6"))
    )
    (comp (ref "XS4")
      (value "Header 7")
      (footprint "SIP-7")
      (description "Header, 7-Pin")
      (fields (field (name "PUBLISHER") "Altium Limited"))
      (libsource (lib "Miscellaneous Connectors") (part "Header 7"))
    )
    (comp (ref "XS6") (value "HEADER 5X2") (footprint "PHD-2*5") (libsource (lib "*") (part "HEADER 5X2")))
    (comp (ref "XS7")
      (value "Header 4")
      (footprint "SIP-4")
      (description "Header, 4-Pin")
      (fields (field (name "PUBLISHER") "Altium Limited"))
      (libsource (lib "Miscellaneous Connectors") (part "Header 4"))
    )
    (comp (ref "XS8")
      (value "Header 4")
      (footprint "SIP-4")
      (description "Header, 4-Pin")
      (fields (field (name "PUBLISHER") "Altium Limited"))
      (libsource (lib "Miscellaneous Connectors") (part "Header 4"))
    )
    (comp (ref "XS9")
      (value "Header 4")
      (footprint "SIP-4")
      (description "Header, 4-Pin")
      (fields (field (name "PUBLISHER") "Altium Limited"))
      (libsource (lib "Miscellaneous Connectors") (part "Header 4"))
    )
    (comp (ref "XS10")
      (value "Header 4")
      (footprint "SIP-4")
      (description "Header, 4-Pin")
      (fields (field (name "PUBLISHER") "Altium Limited"))
      (libsource (lib "Miscellaneous Connectors") (part "Header 4"))
    )
    (comp (ref "XS12")
      (value "Header 6X2")
      (footprint "PHD-2*6")
      (description "Header, 6-Pin, Dual row")
      (fields (field (name "PUBLISHER") "Altium Limited"))
      (libsource (lib "Miscellaneous Connectors") (part "Header 6X2"))
    )
    (comp (ref "XS13")
      (value "Header 5")
      (footprint "SIP-5")
      (description "Header, 5-Pin")
      (fields (field (name "PUBLISHER") "Altium Limited"))
      (libsource (lib "Miscellaneous Connectors") (part "Header 5"))
    )
    (comp (ref "XS14")
      (value "Header 8X2")
      (footprint "HDR2X8")
      (description "Header, 8-Pin, Dual row")
      (fields (field (name "PUBLISHER") "Altium Limited"))
      (libsource (lib "Miscellaneous Connectors") (part "Header 8X2"))
    )
    (comp (ref "XS15")
      (value "Header 3")
      (footprint "SIP-3")
      (description "Header, 3-Pin")
      (fields (field (name "PUBLISHER") "Altium Limited"))
      (libsource (lib "Miscellaneous Connectors") (part "Header 3"))
    )
    (comp (ref "XS16")
      (value "Header 5")
      (footprint "SIP-5")
      (description "Header, 5-Pin")
      (fields (field (name "PUBLISHER") "Altium Limited"))
      (libsource (lib "Miscellaneous Connectors") (part "Header 5"))
    )
    (comp (ref "XS17")
      (value "Header 6X2A")
      (footprint "HDR2X6_CEN")
      (description "Header, 6-Pin, Dual row")
      (fields (field (name "PUBLISHER") "Altium Limited"))
      (libsource (lib "Miscellaneous Connectors") (part "Header 6X2A"))
    )
    (comp (ref "XS18")
      (value "Header 5")
      (footprint "SIP-5")
      (description "Header, 5-Pin")
      (fields (field (name "PUBLISHER") "Altium Limited"))
      (libsource (lib "Miscellaneous Connectors") (part "Header 5"))
    )
    (comp (ref "XS19")
      (value "Header 5")
      (footprint "SIP-5")
      (description "Header, 5-Pin")
      (fields (field (name "PUBLISHER") "Altium Limited"))
      (libsource (lib "Miscellaneous Connectors") (part "Header 5"))
    )
    (comp (ref "XS20")
      (value "Header 5")
      (footprint "SIP-5")
      (description "Header, 5-Pin")
      (fields (field (name "PUBLISHER") "Altium Limited"))
      (libsource (lib "Miscellaneous Connectors") (part "Header 5"))
    )
    (comp (ref "XS21")
      (value "Header 3")
      (footprint "sip-3")
      (description "Header, 3-Pin")
      (fields (field (name "PUBLISHER") "Altium Limited"))
      (libsource (lib "Miscellaneous Connectors") (part "Header 3"))
    )
    (comp (ref "XS22")
      (value "Header 7")
      (footprint "sip-7")
      (description "Header, 7-Pin")
      (fields (field (name "PUBLISHER") "Altium Limited"))
      (libsource (lib "") (part "Header 7_1"))
    )
    (comp (ref "XS23")
      (value "Header 7")
      (footprint "sip-7")
      (description "Header, 7-Pin")
      (fields (field (name "PUBLISHER") "Altium Limited"))
      (libsource (lib "Miscellaneous Connectors") (part "Header 7"))
    )
    (comp (ref "XS24")
      (value "Header 7")
      (footprint "HDR1X7")
      (description "Header, 7-Pin")
      (fields (field (name "PUBLISHER") "Altium Limited"))
      (libsource (lib "Miscellaneous Connectors") (part "Header 7"))
    )
    (comp (ref "XS25")
      (value "Header 7")
      (footprint "HDR1X7")
      (description "Header, 7-Pin")
      (fields (field (name "PUBLISHER") "Altium Limited"))
      (libsource (lib "Miscellaneous Connectors") (part "Header 7"))
    )
    (comp (ref "XS27")
      (value "Header 7")
      (footprint "HDR1X7")
      (description "Header, 7-Pin")
      (fields (field (name "PUBLISHER") "Altium Limited"))
      (libsource (lib "") (part "Header 7_2"))
    )
    (comp (ref "XS28")
      (value "Header 7")
      (footprint "HDR1X7")
      (description "Header, 7-Pin")
      (fields (field (name "PUBLISHER") "Altium Limited"))
      (libsource (lib "") (part "Header 7_1"))
    )
    (comp (ref "XS29")
      (value "Header 7")
      (footprint "HDR1X7")
      (description "Header, 7-Pin")
      (fields (field (name "PUBLISHER") "Altium Limited"))
      (libsource (lib "") (part "Header 7_1"))
    )
    (comp (ref "XS30")
      (value "Header 7")
      (footprint "HDR1X7")
      (description "Header, 7-Pin")
      (fields (field (name "PUBLISHER") "Altium Limited"))
      (libsource (lib "") (part "Header 7_1"))
    )
  )
  (nets
    (net (code "1") (name "+5V") (class "Default")
      (node (ref "C15") (pin "1") (pinfunction "1_1") (pintype "passive"))
      (node (ref "C17") (pin "1") (pinfunction "1_1") (pintype "passive"))
      (node (ref "C43") (pin "2") (pinfunction "2_2") (pintype "passive"))
      (node (ref "C63") (pin "1") (pinfunction "1_1") (pintype "passive"))
      (node (ref "C95") (pin "1") (pinfunction "1_1") (pintype "passive"))
      (node (ref "C97") (pin "1") (pinfunction "1_1") (pintype "passive"))
      (node (ref "C99") (pin "1") (pinfunction "1_1") (pintype "passive"))
      (node (ref "D1") (pin "14") (pinfunction "+5V_14") (pintype "power_in"))
      (node (ref "N10") (pin "5") (pinfunction "VL_5") (pintype "passive"))
      (node (ref "N13") (pin "10") (pinfunction "C_10") (pintype "passive"))
      (node (ref "N13") (pin "12") (pinfunction "C_12") (pintype "passive"))
      (node (ref "N13") (pin "14") (pinfunction "C_14") (pintype "passive"))
      (node (ref "N13") (pin "16") (pinfunction "C_16") (pintype "passive"))
      (node (ref "N15") (pin "10") (pinfunction "C_10") (pintype "passive"))
      (node (ref "N15") (pin "12") (pinfunction "C_12") (pintype "passive"))
      (node (ref "N15") (pin "14") (pinfunction "C_14") (pintype "passive"))
      (node (ref "N15") (pin "16") (pinfunction "C_16") (pintype "passive"))
      (node (ref "N16") (pin "6") (pinfunction "VO_6") (pintype "passive"))
      (node (ref "N16") (pin "8") (pinfunction "VCC_8") (pintype "passive"))
      (node (ref "N17") (pin "9") (pinfunction "COM_9") (pintype "passive"))
      (node (ref "N20") (pin "9") (pinfunction "COM_9") (pintype "passive"))
      (node (ref "N21") (pin "9") (pinfunction "COM_9") (pintype "passive"))
      (node (ref "N22") (pin "1") (pinfunction "Vin_1") (pintype "passive"))
      (node (ref "N24") (pin "6") (pinfunction "VDD_6") (pintype "passive"))
      (node (ref "N25") (pin "14") (pinfunction "C_14") (pintype "passive"))
      (node (ref "N25") (pin "16") (pinfunction "C_16") (pintype "passive"))
      (node (ref "N26") (pin "9") (pinfunction "COM_9") (pintype "passive"))
      (node (ref "N5") (pin "4") (pinfunction "V+_4") (pintype "passive"))
      (node (ref "N6") (pin "10") (pinfunction "C_10") (pintype "passive"))
      (node (ref "N6") (pin "12") (pinfunction "C_12") (pintype "passive"))
      (node (ref "N6") (pin "14") (pinfunction "C_14") (pintype "passive"))
      (node (ref "N6") (pin "16") (pinfunction "C_16") (pintype "passive"))
      (node (ref "N8") (pin "6") (pinfunction "VCC_6") (pintype "passive"))
      (node (ref "P4") (pin "2") (pinfunction "2_2") (pintype "passive"))
      (node (ref "P4") (pin "4") (pinfunction "4_4") (pintype "passive"))
      (node (ref "P4") (pin "6") (pinfunction "6_6") (pintype "passive"))
      (node (ref "P4") (pin "8") (pinfunction "8_8") (pintype "passive"))
      (node (ref "R125") (pin "1") (pinfunction "1_1") (pintype "passive"))
      (node (ref "R142") (pin "2") (pinfunction "2_2") (pintype "passive"))
      (node (ref "XS10") (pin "2") (pinfunction "2_2") (pintype "passive"))
      (node (ref "XS14") (pin "10") (pinfunction "10_10") (pintype "passive"))
      (node (ref "XS14") (pin "12") (pinfunction "12_12") (pintype "passive"))
      (node (ref "XS14") (pin "14") (pinfunction "14_14") (pintype "passive"))
      (node (ref "XS14") (pin "16") (pinfunction "16_16") (pintype "passive"))
      (node (ref "XS14") (pin "2") (pinfunction "2_2") (pintype "passive"))
      (node (ref "XS2") (pin "2") (pinfunction "2_2") (pintype "passive"))
      (node (ref "XS2") (pin "4") (pinfunction "4_4") (pintype "passive"))
      (node (ref "XS2") (pin "6") (pinfunction "6_6") (pintype "passive"))
      (node (ref "XS29") (pin "2") (pinfunction "2_2") (pintype "passive"))
      (node (ref "XS7") (pin "2") (pinfunction "2_2") (pintype "passive"))
      (node (ref "XS8") (pin "2") (pinfunction "2_2") (pintype "passive"))
      (node (ref "XS9") (pin "2") (pinfunction "2_2") (pintype "passive"))
    )
    (net (code "2") (name "+5V12") (class "Default")
      (node (ref "RL1") (pin "9") (pinfunction "9_9") (pintype "passive"))
      (node (ref "RL2") (pin "9") (pinfunction "9_9") (pintype "passive"))
      (node (ref "RL3") (pin "9") (pinfunction "9_9") (pintype "passive"))
      (node (ref "RL4") (pin "9") (pinfunction "9_9") (pintype "passive"))
      (node (ref "RL5") (pin "9") (pinfunction "9_9") (pintype "passive"))
      (node (ref "RL6") (pin "9") (pinfunction "9_9") (pintype "passive"))
      (node (ref "RL7") (pin "9") (pinfunction "9_9") (pintype "passive"))
      (node (ref "RL8") (pin "9") (pinfunction "9_9") (pintype "passive"))
      (node (ref "V19") (pin "2") (pinfunction "K_2") (pintype "passive"))
      (node (ref "V20") (pin "2") (pinfunction "K_2") (pintype "passive"))
      (node (ref "V21") (pin "2") (pinfunction "K_2") (pintype "passive"))
      (node (ref "V22") (pin "2") (pinfunction "K_2") (pintype "passive"))
      (node (ref "V23") (pin "2") (pinfunction "K_2") (pintype "passive"))
      (node (ref "V24") (pin "2") (pinfunction "K_2") (pintype "passive"))
      (node (ref "V25") (pin "2") (pinfunction "K_2") (pintype "passive"))
      (node (ref "V26") (pin "2") (pinfunction "K_2") (pintype "passive"))
      (node (ref "XS30") (pin "2") (pinfunction "2_2") (pintype "passive"))
    )
    (net (code "3") (name "+5VISO1") (class "Default")
      (node (ref "C90") (pin "2") (pintype "passive"))
      (node (ref "C91") (pin "2") (pinfunction "2_2") (pintype "passive"))
      (node (ref "C92") (pin "1") (pinfunction "1_1") (pintype "passive"))
      (node (ref "N22") (pin "4") (pinfunction "V+_4") (pintype "passive"))
      (node (ref "N23") (pin "16") (pinfunction "VDD2_16") (pintype "passive"))
      (node (ref "R109") (pin "1") (pinfunction "1_1") (pintype "passive"))
      (node (ref "R110") (pin "1") (pinfunction "1_1") (pintype "passive"))
      (node (ref "R123") (pin "2") (pinfunction "2_2") (pintype "passive"))
      (node (ref "U4") (pin "16") (pinfunction "VDD2_16") (pintype "passive"))
    )
    (net (code "4") (name "+12V") (class "Default")
      (node (ref "C106") (pin "1") (pinfunction "1_1") (pintype "passive"))
      (node (ref "C2") (pin "1") (pinfunction "1_1") (pintype "passive"))
      (node (ref "C29") (pin "1") (pinfunction "1_1") (pintype "passive"))
      (node (ref "C42") (pin "1") (pinfunction "1_1") (pintype "passive"))
      (node (ref "C44") (pin "2") (pinfunction "2_2") (pintype "passive"))
      (node (ref "C5") (pin "1") (pinfunction "1_1") (pintype "passive"))
      (node (ref "C52") (pin "1") (pinfunction "1_1") (pintype "passive"))
      (node (ref "C7") (pin "1") (pinfunction "1_1") (pintype "passive"))
      (node (ref "C8") (pin "1") (pinfunction "1_1") (pintype "passive"))
      (node (ref "C80") (pin "2") (pintype "passive"))
      (node (ref "C81") (pin "1") (pinfunction "1_1") (pintype "passive"))
      (node (ref "C85") (pin "1") (pinfunction "1_1") (pintype "passive"))
      (node (ref "C9") (pin "1") (pinfunction "1_1") (pintype "passive"))
      (node (ref "N10") (pin "4") (pinfunction "VDD_4") (pintype "passive"))
      (node (ref "N11") (pin "4") (pintype "passive"))
      (node (ref "N12") (pin "2") (pinfunction "IN_2") (pintype "passive"))
      (node (ref "N14") (pin "4") (pintype "passive"))
      (node (ref "N18") (pin "13") (pinfunction "TP_13") (pintype "passive"))
      (node (ref "N18") (pin "14") (pinfunction "VDD_14") (pintype "passive"))
      (node (ref "N19") (pin "2") (pinfunction "IN_2") (pintype "passive"))
      (node (ref "N2") (pin "4") (pinfunction "V+_4") (pintype "passive"))
      (node (ref "N3") (pin "4") (pintype "passive"))
      (node (ref "U1") (pin "3") (pinfunction "Vin_3") (pintype "passive"))
      (node (ref "U3") (pin "8") (pintype "passive"))
      (node (ref "XS10") (pin "1") (pinfunction "1_1") (pintype "passive"))
      (node (ref "XS7") (pin "1") (pinfunction "1_1") (pintype "passive"))
      (node (ref "XS8") (pin "1") (pinfunction "1_1") (pintype "passive"))
      (node (ref "XS9") (pin "1") (pinfunction "1_1") (pintype "passive"))
    )
    (net (code "5") (name "+12V1") (class "Default")
      (node (ref "C28") (pin "1") (pinfunction "1_1") (pintype "passive"))
      (node (ref "N9") (pin "4") (pintype "passive"))
    )
    (net (code "6") (name "+12VIN") (class "Default")
      (node (ref "C16") (pin "1") (pinfunction "1_1") (pintype "passive"))
      (node (ref "C19") (pin "1") (pinfunction "1_1") (pintype "passive"))
      (node (ref "C62") (pin "2") (pinfunction "2_2") (pintype "passive"))
      (node (ref "N4") (pin "2") (pinfunction "OUT_2") (pintype "passive"))
      (node (ref "U5") (pin "8") (pintype "passive"))
    )
    (net (code "7") (name "+24V") (class "Default")
      (node (ref "C12") (pin "1") (pinfunction "1_1") (pintype "passive"))
      (node (ref "C13") (pin "1") (pinfunction "1_1") (pintype "passive"))
      (node (ref "C24") (pin "2") (pinfunction "2_2") (pintype "passive"))
      (node (ref "C27") (pin "2") (pinfunction "2_2") (pintype "passive"))
      (node (ref "N2") (pin "1") (pinfunction "Vin_1") (pintype "passive"))
      (node (ref "N4") (pin "3") (pinfunction "IN_3") (pintype "passive"))
      (node (ref "N5") (pin "1") (pinfunction "Vin_1") (pintype "passive"))
      (node (ref "N7") (pin "1") (pinfunction "Vin_1") (pintype "passive"))
      (node (ref "R113") (pin "2") (pinfunction "2_2") (pintype "passive"))
      (node (ref "XS1") (pin "1") (pinfunction "1_1") (pintype "passive"))
      (node (ref "XS1") (pin "2") (pinfunction "2_2") (pintype "passive"))
      (node (ref "XS12") (pin "1") (pinfunction "1_1") (pintype "passive"))
      (node (ref "XS12") (pin "2") (pinfunction "2_2") (pintype "passive"))
      (node (ref "XS22") (pin "4") (pinfunction "4_4") (pintype "passive"))
      (node (ref "XS23") (pin "7") (pinfunction "7_7") (pintype "passive"))
      (node (ref "XS27") (pin "7") (pinfunction "7_7") (pintype "passive"))
    )
    (net (code "8") (name "-5V") (class "Default")
      (node (ref "C23") (pin "2") (pinfunction "2_2") (pintype "passive"))
      (node (ref "C26") (pin "2") (pinfunction "2_2") (pintype "passive"))
      (node (ref "N18") (pin "3") (pinfunction "VSS_3") (pintype "passive"))
      (node (ref "N7") (pin "3") (pinfunction "V-_3") (pintype "passive"))
      (node (ref "R28") (pin "1") (pinfunction "1_1") (pintype "passive"))
    )
    (net (code "9") (name "/+24V12") (class "Default")
      (node (ref "RL2") (pin "3") (pinfunction "3_3") (pintype "passive"))
      (node (ref "RL3") (pin "3") (pinfunction "3_3") (pintype "passive"))
      (node (ref "RL4") (pin "3") (pinfunction "3_3") (pintype "passive"))
      (node (ref "RL5") (pin "3") (pinfunction "3_3") (pintype "passive"))
      (node (ref "RL6") (pin "3") (pinfunction "3_3") (pintype "passive"))
      (node (ref "RL7") (pin "3") (pinfunction "3_3") (pintype "passive"))
      (node (ref "RL8") (pin "3") (pinfunction "3_3") (pintype "passive"))
      (node (ref "XS25") (pin "7") (pinfunction "7_7") (pintype "passive"))
    )
    (net (code "10") (name "/+24VGND12") (class "Default")
      (node (ref "RL2") (pin "1") (pinfunction "5_1") (pintype "passive"))
      (node (ref "RL3") (pin "1") (pinfunction "5_1") (pintype "passive"))
      (node (ref "RL4") (pin "1") (pinfunction "5_1") (pintype "passive"))
      (node (ref "RL5") (pin "1") (pinfunction "5_1") (pintype "passive"))
      (node (ref "RL6") (pin "1") (pinfunction "5_1") (pintype "passive"))
      (node (ref "RL7") (pin "1") (pinfunction "5_1") (pintype "passive"))
      (node (ref "RL8") (pin "1") (pinfunction "5_1") (pintype "passive"))
      (node (ref "XS25") (pin "6") (pinfunction "6_6") (pintype "passive"))
    )
    (net (code "11") (name "/A1") (class "Default")
      (node (ref "C93") (pin "1") (pinfunction "1_1") (pintype "passive"))
      (node (ref "C94") (pin "1") (pinfunction "1_1") (pintype "passive"))
      (node (ref "R109") (pin "2") (pinfunction "2_2") (pintype "passive"))
      (node (ref "R111") (pin "1") (pinfunction "1_1") (pintype "passive"))
      (node (ref "U4") (pin "14") (pinfunction "A_14") (pintype "passive"))
      (node (ref "V27") (pin "K") (pintype "passive"))
      (node (ref "XS13") (pin "1") (pinfunction "1_1") (pintype "passive"))
    )
    (net (code "12") (name "/ADC_IN1") (class "Default")
      (node (ref "U2") (pin "18") (pinfunction "PF6_18") (pintype "bidirectional"))
    )
    (net (code "14") (name "/ADC_IN2") (class "Default")
      (node (ref "U2") (pin "19") (pinfunction "PF7_19") (pintype "bidirectional"))
    )
    (net (code "15") (name "/ADC_IN2#") (class "Default")
      (node (ref "R16") (pin "1") (pinfunction "1_1") (pintype "passive"))
      (node (ref "V7") (pin "2") (pinfunction "K_2") (pintype "passive"))
    )
    (net (code "16") (name "/ADC_IN3") (class "Default")
      (node (ref "U2") (pin "20") (pinfunction "PF8_20") (pintype "bidirectional"))
    )
    (net (code "17") (name "/ADC_IN3#") (class "Default")
      (node (ref "R25") (pin "1") (pinfunction "1_1") (pintype "passive"))
      (node (ref "V11") (pin "2") (pinfunction "K_2") (pintype "passive"))
    )
    (net (code "18") (name "/ADC_IN4") (class "Default")
      (node (ref "U2") (pin "26") (pinfunction "PC0_26") (pintype "bidirectional"))
    )
    (net (code "19") (name "/ADC_IN4#") (class "Default")
      (node (ref "R36") (pin "1") (pinfunction "1_1") (pintype "passive"))
      (node (ref "V12") (pin "2") (pinfunction "K_2") (pintype "passive"))
    )
    (net (code "20") (name "/ADC_IN5") (class "Default")
      (node (ref "U2") (pin "27") (pinfunction "PC1_27") (pintype "bidirectional"))
    )
    (net (code "21") (name "/ADC_IN5#") (class "Default")
      (node (ref "R49") (pin "1") (pinfunction "1_1") (pintype "passive"))
      (node (ref "V14") (pin "2") (pinfunction "K_2") (pintype "passive"))
    )
    (net (code "22") (name "/ADC_IN6") (class "Default")
      (node (ref "U2") (pin "28") (pinfunction "PC2_28") (pintype "bidirectional"))
    )
    (net (code "23") (name "/ADC_IN6#") (class "Default")
      (node (ref "R62") (pin "1") (pinfunction "1_1") (pintype "passive"))
      (node (ref "V16") (pin "2") (pinfunction "K_2") (pintype "passive"))
    )
    (net (code "24") (name "/ADC_IN7") (class "Default")
      (node (ref "R38") (pin "1") (pinfunction "1_1") (pintype "passive"))
      (node (ref "U2") (pin "29") (pinfunction "PC3_29") (pintype "bidirectional"))
      (node (ref "V13") (pin "2") (pinfunction "K_2") (pintype "passive"))
    )
    (net (code "25") (name "/ADC_IN8") (class "Default")
      (node (ref "R52") (pin "1") (pinfunction "1_1") (pintype "passive"))
      (node (ref "U2") (pin "44") (pinfunction "PC4_44") (pintype "bidirectional"))
      (node (ref "V15") (pin "2") (pinfunction "K_2") (pintype "passive"))
    )
    (net (code "26") (name "/ADC_IN9") (class "Default")
      (node (ref "R65") (pin "1") (pinfunction "1_1") (pintype "passive"))
      (node (ref "U2") (pin "45") (pinfunction "PC5_45") (pintype "bidirectional"))
      (node (ref "V17") (pin "2") (pinfunction "K_2") (pintype "passive"))
    )
    (net (code "27") (name "/ADC_IN10") (class "Default")
      (node (ref "U2") (pin "21") (pinfunction "PF9_21") (pintype "bidirectional"))
    )
    (net (code "28") (name "/ADC_IN10#") (class "Default")
      (node (ref "R130") (pin "1") (pinfunction "1_1") (pintype "passive"))
      (node (ref "V34") (pin "2") (pinfunction "K_2") (pintype "passive"))
    )
    (net (code "29") (name "/ADC_IN11") (class "Default")
      (node (ref "U2") (pin "22") (pinfunction "PF10_22") (pintype "bidirectional"))
    )
    (net (code "30") (name "/ADC_IN11#") (class "Default")
      (node (ref "R136") (pin "1") (pinfunction "1_1") (pintype "passive"))
      (node (ref "V35") (pin "2") (pinfunction "K_2") (pintype "passive"))
    )
    (net (code "31") (name "/ADC_IN12") (class "Default")
      (node (ref "U2") (pin "40") (pinfunction "PA4_40") (pintype "bidirectional"))
    )
    (net (code "32") (name "/ADC_IN12#") (class "Default")
      (node (ref "R140") (pin "1") (pinfunction "1_1") (pintype "passive"))
      (node (ref "V36") (pin "2") (pinfunction "K_2") (pintype "passive"))
    )
    (net (code "33") (name "/Analog-in") (class "Default")
      (node (ref "C54") (pin "1") (pinfunction "1_1") (pintype "passive"))
      (node (ref "R73") (pin "1") (pinfunction "1_1") (pintype "passive"))
      (node (ref "XS21") (pin "2") (pinfunction "2_2") (pintype "passive"))
    )
    (net (code "34") (name "/B1") (class "Default")
      (node (ref "R111") (pin "2") (pinfunction "2_2") (pintype "passive"))
      (node (ref "U4") (pin "13") (pinfunction "B_13") (pintype "passive"))
      (node (ref "V29") (pin "K") (pintype "passive"))
      (node (ref "XS13") (pin "2") (pinfunction "2_2") (pintype "passive"))
    )
    (net (code "35") (name "/BOOT0") (class "Default")
      (node (ref "R107") (pin "2") (pinfunction "2_2") (pintype "passive"))
      (node (ref "U2") (pin "138") (pinfunction "BOOT0_138") (pintype "input"))
    )
    (net (code "36") (name "/BOOT1") (class "Default")
      (node (ref "R54") (pin "2") (pinfunction "2_2") (pintype "passive"))
      (node (ref "U2") (pin "48") (pinfunction "PB2_48") (pintype "bidirectional"))
    )
    (net (code "37") (name "/BRAKE") (class "Default")
      (node (ref "XS2") (pin "5") (pinfunction "5_5") (pintype "passive"))
    )
    (net (code "38") (name "/BRAKEMCU") (class "Default")
      (node (ref "D1") (pin "2") (pintype "output"))
      (node (ref "U2") (pin "88") (pinfunction "PG3_88") (pintype "bidirectional"))
    )
    (net (code "39") (name "/BUZZER_Out11") (class "Default")
      (node (ref "XS12") (pin "9") (pinfunction "9_9") (pintype "passive"))
    )
    (net (code "40") (name "/BUZZER_Out12") (class "Default")
      (node (ref "RL4") (pin "5") (pinfunction "5_5") (pintype "passive"))
      (node (ref "RL4") (pin "6") (pinfunction "6_6") (pintype "passive"))
      (node (ref "XS30") (pin "4") (pinfunction "4_4") (pintype "passive"))
    )
    (net (code "41") (name "/Bed_Clear_Fault") (class "Default")
      (node (ref "C60") (pin "2") (pinfunction "2_2") (pintype "passive"))
      (node (ref "N15") (pin "13") (pinfunction "E_13") (pintype "passive"))
      (node (ref "R88") (pin "1") (pinfunction "1_1") (pintype "passive"))
      (node (ref "U2") (pin "142") (pinfunction "PE1_142") (pintype "bidirectional"))
    )
    (net (code "42") (name "/Bed_PowerOff") (class "Default")
      (node (ref "C71") (pin "2") (pinfunction "2_2") (pintype "passive"))
      (node (ref "N15") (pin "9") (pinfunction "E_9") (pintype "passive"))
      (node (ref "R104") (pin "1") (pinfunction "1_1") (pintype "passive"))
      (node (ref "U2") (pin "93") (pinfunction "PG8_93") (pintype "bidirectional"))
    )
    (net (code "43") (name "/Bed_Red_Light") (class "Default")
      (node (ref "C65") (pin "2") (pinfunction "2_2") (pintype "passive"))
      (node (ref "N15") (pin "11") (pinfunction "E_11") (pintype "passive"))
      (node (ref "R99") (pin "1") (pinfunction "1_1") (pintype "passive"))
      (node (ref "U2") (pin "92") (pinfunction "PG7_92") (pintype "bidirectional"))
    )
    (net (code "44") (name "/Bed_Work_On") (class "Default")
      (node (ref "C55") (pin "2") (pinfunction "2_2") (pintype "passive"))
      (node (ref "N15") (pin "15") (pinfunction "E_15") (pintype "passive"))
      (node (ref "R82") (pin "1") (pinfunction "1_1") (pintype "passive"))
      (node (ref "U2") (pin "91") (pinfunction "PG6_91") (pintype "bidirectional"))
    )
    (net (code "45") (name "/CLKSEL") (class "Default")
      (node (ref "N10") (pin "6") (pinfunction "IN_6") (pintype "passive"))
      (node (ref "R45") (pin "2") (pinfunction "2_2") (pintype "passive"))
      (node (ref "U2") (pin "77") (pinfunction "PD8_77") (pintype "bidirectional"))
    )
    (net (code "46") (name "/DA_CLK") (class "Default")
      (node (ref "N18") (pin "10") (pinfunction "SCK_10") (pintype "passive"))
      (node (ref "U2") (pin "73") (pinfunction "PB12_73") (pintype "bidirectional"))
    )
    (net (code "47") (name "/DA_CS") (class "Default")
      (node (ref "N18") (pin "9") (pinfunction "~{CS}_9") (pintype "passive"))
      (node (ref "U2") (pin "75") (pinfunction "PB14_75") (pintype "bidirectional"))
    )
    (net (code "48") (name "/DA_DIN") (class "Default")
      (node (ref "N18") (pin "8") (pinfunction "SDI_8") (pintype "passive"))
      (node (ref "U2") (pin "74") (pinfunction "PB13_74") (pintype "bidirectional"))
    )
    (net (code "49") (name "/Emission11") (class "Default")
      (node (ref "XS23") (pin "3") (pinfunction "3_3") (pintype "passive"))
      (node (ref "XS27") (pin "3") (pinfunction "3_3") (pintype "passive"))
    )
    (net (code "50") (name "/Emission12") (class "Default")
      (node (ref "RL3") (pin "5") (pinfunction "5_5") (pintype "passive"))
      (node (ref "RL3") (pin "6") (pinfunction "6_6") (pintype "passive"))
      (node (ref "XS25") (pin "3") (pinfunction "3_3") (pintype "passive"))
    )
    (net (code "51") (name "/Ext_Iset") (class "Default")
      (node (ref "R76") (pin "2") (pinfunction "2_2") (pintype "passive"))
      (node (ref "U2") (pin "42") (pinfunction "PA6_42") (pintype "bidirectional"))
    )
    (net (code "52") (name "/Ext_Triger") (class "Default")
      (node (ref "C67") (pin "2") (pinfunction "2_2") (pintype "passive"))
      (node (ref "N10") (pin "8") (pinfunction "S2_8") (pintype "passive"))
      (node (ref "N16") (pin "5") (pinfunction "GND_5") (pintype "passive"))
      (node (ref "R97") (pin "1") (pinfunction "1_1") (pintype "passive"))
    )
    (net (code "53") (name "/Fault_PD1") (class "Default")
      (node (ref "C1") (pin "2") (pinfunction "2_2") (pintype "passive"))
      (node (ref "V4") (pin "1") (pinfunction "A_1") (pintype "passive"))
      (node (ref "XS14") (pin "4") (pinfunction "4_4") (pintype "passive"))
    )
    (net (code "54") (name "/Fault_PD2") (class "Default")
      (node (ref "C11") (pin "2") (pinfunction "2_2") (pintype "passive"))
      (node (ref "V5") (pin "1") (pinfunction "A_1") (pintype "passive"))
      (node (ref "XS14") (pin "6") (pinfunction "6_6") (pintype "passive"))
    )
    (net (code "55") (name "/Flow_Signal") (class "Default")
      (node (ref "R116") (pin "1") (pinfunction "1_1") (pintype "passive"))
      (node (ref "U2") (pin "139") (pinfunction "PB8_139") (pintype "bidirectional"))
    )
    (net (code "56") (name "/Gate") (class "Default")
      (node (ref "R86") (pin "2") (pinfunction "2_2") (pintype "passive"))
      (node (ref "XS22") (pin "2") (pinfunction "2_2") (pintype "passive"))
    )
    (net (code "57") (name "/Green_Out11") (class "Default")
      (node (ref "XS12") (pin "7") (pinfunction "7_7") (pintype "passive"))
    )
    (net (code "58") (name "/Green_Out12") (class "Default")
      (node (ref "RL7") (pin "5") (pinfunction "5_5") (pintype "passive"))
      (node (ref "RL7") (pin "6") (pinfunction "6_6") (pintype "passive"))
      (node (ref "XS30") (pin "5") (pinfunction "5_5") (pintype "passive"))
    )
    (net (code "59") (name "/IF OUT1") (class "Default")
      (node (ref "XS18") (pin "2") (pinfunction "2_2") (pintype "passive"))
    )
    (net (code "60") (name "/IF OUT1#") (class "Default")
      (node (ref "R7") (pin "1") (pinfunction "1_1") (pintype "passive"))
    )
    (net (code "61") (name "/IF OUT2") (class "Default")
      (node (ref "XS19") (pin "2") (pinfunction "2_2") (pintype "passive"))
    )
    (net (code "62") (name "/IF OUT2#") (class "Default")
      (node (ref "R37") (pin "1") (pinfunction "1_1") (pintype "passive"))
    )
    (net (code "63") (name "/IF OUT3") (class "Default")
      (node (ref "R39") (pin "1") (pinfunction "1_1") (pintype "passive"))
      (node (ref "XS20") (pin "2") (pinfunction "2_2") (pintype "passive"))
    )
    (net (code "64") (name "/IF OUT4") (class "Default")
      (node (ref "XS16") (pin "2") (pinfunction "2_2") (pintype "passive"))
    )
    (net (code "65") (name "/IF OUT4#") (class "Default")
      (node (ref "R141") (pin "1") (pinfunction "1_1") (pintype "passive"))
    )
    (net (code "66") (name "/IO_INPUT1") (class "Default")
      (node (ref "XS2") (pin "1") (pinfunction "1_1") (pintype "passive"))
    )
    (net (code "67") (name "/ISET1") (class "Default")
      (node (ref "C72") (pin "1") (pintype "passive"))
      (node (ref "C73") (pin "1") (pintype "passive"))
      (node (ref "N18") (pin "2") (pinfunction "OUTA_2") (pintype "passive"))
      (node (ref "XS17") (pin "ISET1") (pinfunction "1_ISET1") (pintype "passive"))
    )
    (net (code "68") (name "/ISET2") (class "Default")
      (node (ref "C74") (pin "1") (pintype "passive"))
      (node (ref "C75") (pin "1") (pintype "passive"))
      (node (ref "N18") (pin "1") (pinfunction "OUTB_1") (pintype "passive"))
      (node (ref "XS17") (pin "3") (pinfunction "3_3") (pintype "passive"))
    )
    (net (code "69") (name "/ISET3") (class "Default")
      (node (ref "C76") (pin "1") (pintype "passive"))
      (node (ref "C77") (pin "1") (pintype "passive"))
      (node (ref "N18") (pin "16") (pinfunction "OUTC_16") (pintype "passive"))
      (node (ref "XS17") (pin "5") (pinfunction "5_5") (pintype "passive"))
    )
    (net (code "70") (name "/ISET4") (class "Default")
      (node (ref "C78") (pin "1") (pintype "passive"))
      (node (ref "C79") (pin "1") (pintype "passive"))
      (node (ref "N18") (pin "15") (pinfunction "OUTD_15") (pintype "passive"))
      (node (ref "XS17") (pin "7") (pinfunction "7_7") (pintype "passive"))
    )
    (net (code "71") (name "/I_FaL1") (class "Default")
      (node (ref "C20") (pin "1") (pinfunction "1_1") (pintype "passive"))
      (node (ref "N6") (pin "1") (pinfunction "A_1") (pintype "passive"))
      (node (ref "XS18") (pin "1") (pinfunction "1_1") (pintype "passive"))
    )
    (net (code "72") (name "/I_FaL2") (class "Default")
      (node (ref "C21") (pin "2") (pinfunction "2_2") (pintype "passive"))
      (node (ref "N6") (pin "3") (pinfunction "A_3") (pintype "passive"))
      (node (ref "XS19") (pin "1") (pinfunction "1_1") (pintype "passive"))
    )
    (net (code "73") (name "/I_FaL3") (class "Default")
      (node (ref "C3") (pin "2") (pinfunction "2_2") (pintype "passive"))
      (node (ref "N6") (pin "5") (pinfunction "A_5") (pintype "passive"))
      (node (ref "XS20") (pin "1") (pinfunction "1_1") (pintype "passive"))
    )
    (net (code "74") (name "/I_FaL4") (class "Default")
      (node (ref "C105") (pin "2") (pinfunction "2_2") (pintype "passive"))
      (node (ref "N6") (pin "7") (pinfunction "A_7") (pintype "passive"))
      (node (ref "XS16") (pin "1") (pinfunction "1_1") (pintype "passive"))
    )
    (net (code "75") (name "/I_Fault1") (class "Default")
      (node (ref "N6") (pin "15") (pinfunction "E_15") (pintype "passive"))
      (node (ref "R18") (pin "1") (pinfunction "1_1") (pintype "passive"))
      (node (ref "U2") (pin "11") (pinfunction "PF1_11") (pintype "bidirectional"))
      (node (ref "V6") (pin "1") (pinfunction "A_1") (pintype "passive"))
    )
    (net (code "76") (name "/I_Fault2") (class "Default")
      (node (ref "N6") (pin "13") (pinfunction "E_13") (pintype "passive"))
      (node (ref "R21") (pin "1") (pinfunction "1_1") (pintype "passive"))
      (node (ref "U2") (pin "12") (pinfunction "PF2_12") (pintype "bidirectional"))
      (node (ref "V8") (pin "1") (pinfunction "A_1") (pintype "passive"))
    )
    (net (code "77") (name "/I_Fault3") (class "Default")
      (node (ref "N6") (pin "11") (pinfunction "E_11") (pintype "passive"))
      (node (ref "R11") (pin "1") (pinfunction "1_1") (pintype "passive"))
      (node (ref "U2") (pin "13") (pinfunction "PF3_13") (pintype "bidirectional"))
      (node (ref "V9") (pin "1") (pinfunction "A_1") (pintype "passive"))
    )
    (net (code "78") (name "/I_Fault4") (class "Default")
      (node (ref "N6") (pin "9") (pinfunction "E_9") (pintype "passive"))
      (node (ref "R24") (pin "1") (pinfunction "1_1") (pintype "passive"))
      (node (ref "U2") (pin "14") (pinfunction "PF4_14") (pintype "bidirectional"))
      (node (ref "V37") (pin "1") (pinfunction "A_1") (pintype "passive"))
    )
    (net (code "79") (name "/Int_Triger") (class "Default")
      (node (ref "N10") (pin "2") (pinfunction "S1_2") (pintype "passive"))
      (node (ref "U2") (pin "34") (pinfunction "PA0-WKUP_34") (pintype "bidirectional"))
    )
    (net (code "80") (name "/KEY_INPUT") (class "Default")
      (node (ref "D1") (pin "6") (pintype "output"))
      (node (ref "U2") (pin "90") (pinfunction "PG5_90") (pintype "bidirectional"))
    )
    (net (code "81") (name "/L1_MCU1") (class "Default")
      (node (ref "N13") (pin "15") (pinfunction "E_15") (pintype "passive"))
      (node (ref "R58") (pin "1") (pinfunction "1_1") (pintype "passive"))
      (node (ref "U2") (pin "1") (pinfunction "PE2_1") (pintype "bidirectional"))
    )
    (net (code "82") (name "/L1_MCU2") (class "Default")
      (node (ref "N13") (pin "13") (pinfunction "E_13") (pintype "passive"))
      (node (ref "R61") (pin "1") (pinfunction "1_1") (pintype "passive"))
      (node (ref "U2") (pin "4") (pinfunction "PE5_4") (pintype "bidirectional"))
    )
    (net (code "83") (name "/L1_OUT1") (class "Default")
      (node (ref "C47") (pin "1") (pinfunction "1_1") (pintype "passive"))
      (node (ref "N13") (pin "1") (pinfunction "A_1") (pintype "passive"))
      (node (ref "XS4") (pin "1") (pinfunction "1_1") (pintype "passive"))
    )
    (net (code "84") (name "/L1_OUT2") (class "Default")
      (node (ref "C48") (pin "1") (pinfunction "1_1") (pintype "passive"))
      (node (ref "N13") (pin "3") (pinfunction "A_3") (pintype "passive"))
      (node (ref "XS4") (pin "2") (pinfunction "2_2") (pintype "passive"))
    )
    (net (code "85") (name "/L2_MCU1") (class "Default")
      (node (ref "N13") (pin "11") (pinfunction "E_11") (pintype "passive"))
      (node (ref "R67") (pin "1") (pinfunction "1_1") (pintype "passive"))
      (node (ref "U2") (pin "2") (pinfunction "PE3_2") (pintype "bidirectional"))
    )
    (net (code "86") (name "/L2_MCU2") (class "Default")
      (node (ref "N13") (pin "9") (pinfunction "E_9") (pintype "passive"))
      (node (ref "R69") (pin "1") (pinfunction "1_1") (pintype "passive"))
      (node (ref "U2") (pin "5") (pinfunction "PE6_5") (pintype "bidirectional"))
    )
    (net (code "87") (name "/L2_OUT1") (class "Default")
      (node (ref "C49") (pin "1") (pinfunction "1_1") (pintype "passive"))
      (node (ref "N13") (pin "5") (pinfunction "A_5") (pintype "passive"))
      (node (ref "XS4") (pin "3") (pinfunction "3_3") (pintype "passive"))
    )
    (net (code "88") (name "/L2_OUT2") (class "Default")
      (node (ref "C50") (pin "1") (pinfunction "1_1") (pintype "passive"))
      (node (ref "N13") (pin "7") (pinfunction "A_7") (pintype "passive"))
      (node (ref "XS4") (pin "4") (pinfunction "4_4") (pintype "passive"))
    )
    (net (code "89") (name "/L3_MCU1") (class "Default")
      (node (ref "N25") (pin "15") (pinfunction "E_15") (pintype "passive"))
      (node (ref "R72") (pin "1") (pinfunction "1_1") (pintype "passive"))
      (node (ref "U2") (pin "3") (pinfunction "PE4_3") (pintype "bidirectional"))
    )
    (net (code "90") (name "/L3_MCU2") (class "Default")
      (node (ref "N25") (pin "13") (pinfunction "E_13") (pintype "passive"))
      (node (ref "R79") (pin "1") (pinfunction "1_1") (pintype "passive"))
      (node (ref "U2") (pin "111") (pinfunction "PC10_111") (pintype "bidirectional"))
    )
    (net (code "91") (name "/L3_OUT1") (class "Default")
      (node (ref "C51") (pin "1") (pinfunction "1_1") (pintype "passive"))
      (node (ref "N25") (pin "1") (pinfunction "A_1") (pintype "passive"))
      (node (ref "XS4") (pin "5") (pinfunction "5_5") (pintype "passive"))
    )
    (net (code "92") (name "/L3_OUT2") (class "Default")
      (node (ref "C53") (pin "1") (pinfunction "1_1") (pintype "passive"))
      (node (ref "N25") (pin "3") (pinfunction "A_3") (pintype "passive"))
      (node (ref "XS4") (pin "6") (pinfunction "6_6") (pintype "passive"))
    )
    (net (code "93") (name "/LD_EN") (class "Default")
      (node (ref "U2") (pin "10") (pinfunction "PF0_10") (pintype "bidirectional"))
      (node (ref "V2") (pin "1") (pinfunction "A_1") (pintype "passive"))
    )
    (net (code "94") (name "/LD_OnOff") (class "Default")
      (node (ref "N17") (pin "7") (pinfunction "IN7_7") (pintype "passive"))
      (node (ref "U2") (pin "86") (pinfunction "PD15_86") (pintype "bidirectional"))
    )
    (net (code "95") (name "/LD_Power11") (class "Default")
      (node (ref "XS12") (pin "11") (pinfunction "11_11") (pintype "passive"))
    )
    (net (code "96") (name "/LD_Power12") (class "Default")
      (node (ref "RL8") (pin "5") (pinfunction "5_5") (pintype "passive"))
      (node (ref "RL8") (pin "6") (pinfunction "6_6") (pintype "passive"))
      (node (ref "XS30") (pin "3") (pinfunction "3_3") (pintype "passive"))
    )
    (net (code "97") (name "/LED1") (class "Default")
      (node (ref "N21") (pin "1") (pinfunction "IN1_1") (pintype "passive"))
      (node (ref "U2") (pin "114") (pinfunction "PD0_114") (pintype "bidirectional"))
    )
    (net (code "98") (name "/LED1_OUT") (class "Default")
      (node (ref "VR2") (pin "8") (pinfunction "8_8") (pintype "passive"))
      (node (ref "XS14") (pin "1") (pinfunction "1_1") (pintype "passive"))
    )
    (net (code "99") (name "/LED2") (class "Default")
      (node (ref "N21") (pin "2") (pinfunction "IN2_2") (pintype "passive"))
      (node (ref "U2") (pin "115") (pinfunction "PD1_115") (pintype "bidirectional"))
    )
    (net (code "100") (name "/LED2_OUT") (class "Default")
      (node (ref "VR2") (pin "7") (pinfunction "7_7") (pintype "passive"))
      (node (ref "XS14") (pin "3") (pinfunction "3_3") (pintype "passive"))
    )
    (net (code "101") (name "/LED3") (class "Default")
      (node (ref "N21") (pin "3") (pinfunction "IN3_3") (pintype "passive"))
      (node (ref "U2") (pin "116") (pinfunction "PD2_116") (pintype "bidirectional"))
    )
    (net (code "102") (name "/LED3_OUT") (class "Default")
      (node (ref "VR2") (pin "6") (pinfunction "6_6") (pintype "passive"))
      (node (ref "XS14") (pin "5") (pinfunction "5_5") (pintype "passive"))
    )
    (net (code "103") (name "/LED4") (class "Default")
      (node (ref "N21") (pin "4") (pinfunction "IN4_4") (pintype "passive"))
      (node (ref "U2") (pin "117") (pinfunction "PD3_117") (pintype "bidirectional"))
    )
    (net (code "104") (name "/LED4_OUT") (class "Default")
      (node (ref "VR2") (pin "5") (pinfunction "5_5") (pintype "passive"))
      (node (ref "XS14") (pin "7") (pinfunction "7_7") (pintype "passive"))
    )
    (net (code "105") (name "/LED5") (class "Default")
      (node (ref "N21") (pin "5") (pinfunction "IN5_5") (pintype "passive"))
      (node (ref "U2") (pin "118") (pinfunction "PD4_118") (pintype "bidirectional"))
    )
    (net (code "106") (name "/LED5_OUT") (class "Default")
      (node (ref "VR4") (pin "8") (pinfunction "8_8") (pintype "passive"))
      (node (ref "XS14") (pin "9") (pinfunction "9_9") (pintype "passive"))
    )
    (net (code "107") (name "/LED6") (class "Default")
      (node (ref "N21") (pin "6") (pinfunction "IN6_6") (pintype "passive"))
      (node (ref "U2") (pin "119") (pinfunction "PD5_119") (pintype "bidirectional"))
    )
    (net (code "108") (name "/LED6_OUT") (class "Default")
      (node (ref "VR4") (pin "7") (pinfunction "7_7") (pintype "passive"))
      (node (ref "XS14") (pin "11") (pinfunction "11_11") (pintype "passive"))
    )
    (net (code "109") (name "/LED7") (class "Default")
      (node (ref "N26") (pin "4") (pinfunction "IN4_4") (pintype "passive"))
      (node (ref "U2") (pin "122") (pinfunction "PD6_122") (pintype "bidirectional"))
    )
    (net (code "110") (name "/LED7_OUT") (class "Default")
      (node (ref "VR5") (pin "8") (pinfunction "8_8") (pintype "passive"))
      (node (ref "XS14") (pin "13") (pinfunction "13_13") (pintype "passive"))
    )
    (net (code "111") (name "/LED8") (class "Default")
      (node (ref "N26") (pin "5") (pinfunction "IN5_5") (pintype "passive"))
      (node (ref "U2") (pin "123") (pinfunction "PD7_123") (pintype "bidirectional"))
    )
    (net (code "112") (name "/LED8_OUT") (class "Default")
      (node (ref "VR5") (pin "7") (pinfunction "7_7") (pintype "passive"))
      (node (ref "XS14") (pin "15") (pinfunction "15_15") (pintype "passive"))
    )
    (net (code "113") (name "/LED_BUZZER") (class "Default")
      (node (ref "N20") (pin "5") (pinfunction "IN5_5") (pintype "passive"))
      (node (ref "U2") (pin "126") (pinfunction "PG11_126") (pintype "bidirectional"))
    )
    (net (code "114") (name "/LED_Green") (class "Default")
      (node (ref "N20") (pin "6") (pinfunction "IN6_6") (pintype "passive"))
      (node (ref "U2") (pin "125") (pinfunction "PG10_125") (pintype "bidirectional"))
    )
    (net (code "115") (name "/LED_RED") (class "Default")
      (node (ref "N20") (pin "1") (pinfunction "IN1_1") (pintype "passive"))
      (node (ref "U2") (pin "132") (pinfunction "PG15_132") (pintype "bidirectional"))
    )
    (net (code "116") (name "/LED_Yellow") (class "Default")
      (node (ref "N20") (pin "2") (pinfunction "IN2_2") (pintype "passive"))
      (node (ref "U2") (pin "129") (pinfunction "PG14_129") (pintype "bidirectional"))
    )
    (net (code "117") (name "/Lock11") (class "Default")
      (node (ref "XS23") (pin "5") (pinfunction "5_5") (pintype "passive"))
      (node (ref "XS27") (pin "5") (pinfunction "5_5") (pintype "passive"))
    )
    (net (code "118") (name "/Lock12") (class "Default")
      (node (ref "XS25") (pin "5") (pinfunction "5_5") (pintype "passive"))
    )
    (net (code "119") (name "/Mcu_Emission") (class "Default")
      (node (ref "N20") (pin "4") (pinfunction "IN4_4") (pintype "passive"))
      (node (ref "U2") (pin "127") (pinfunction "PG12_127") (pintype "bidirectional"))
    )
    (net (code "120") (name "/Mcu_Ready") (class "Default")
      (node (ref "N20") (pin "3") (pinfunction "IN3_3") (pintype "passive"))
      (node (ref "U2") (pin "128") (pinfunction "PG13_128") (pintype "bidirectional"))
    )
    (net (code "121") (name "/NJTRST") (class "Default")
      (node (ref "R96") (pin "2") (pinfunction "2_2") (pintype "passive"))
      (node (ref "U2") (pin "134") (pinfunction "PB4_134") (pintype "bidirectional"))
      (node (ref "XS6") (pin "3") (pinfunction "3_3") (pintype "passive"))
    )
    (net (code "122") (name "/NRST") (class "Default")
      (node (ref "C82") (pin "2") (pinfunction "2_2") (pintype "passive"))
      (node (ref "C83") (pin "2") (pinfunction "2_2") (pintype "passive"))
      (node (ref "R106") (pin "1") (pinfunction "1_1") (pintype "passive"))
      (node (ref "S1") (pin "2") (pinfunction "NO_2") (pintype "passive"))
      (node (ref "U2") (pin "25") (pinfunction "NRST_25") (pintype "bidirectional"))
      (node (ref "XS6") (pin "4") (pinfunction "4_4") (pintype "passive"))
    )
    (net (code "123") (name "/OSC_IN") (class "Default")
      (node (ref "B1") (pin "2") (pinfunction "2_2") (pintype "passive"))
      (node (ref "C84") (pin "1") (pinfunction "1_1") (pintype "passive"))
      (node (ref "U2") (pin "23") (pinfunction "OSC_IN_23") (pintype "input"))
    )
    (net (code "124") (name "/OSC_OUT") (class "Default")
      (node (ref "B1") (pin "1") (pinfunction "1_1") (pintype "passive"))
      (node (ref "C89") (pin "2") (pinfunction "2_2") (pintype "passive"))
      (node (ref "U2") (pin "24") (pinfunction "OSC_OUT_24") (pintype "output"))
    )
    (net (code "125") (name "/Polit-on") (class "Default")
      (node (ref "R89") (pin "2") (pinfunction "2_2") (pintype "passive"))
      (node (ref "XS22") (pin "5") (pinfunction "5_5") (pintype "passive"))
    )
    (net (code "126") (name "/Power-on") (class "Default")
      (node (ref "R74") (pin "2") (pinfunction "2_2") (pintype "passive"))
      (node (ref "XS22") (pin "7") (pinfunction "7_7") (pintype "passive"))
    )
    (net (code "127") (name "/PowerOff-inb") (class "Default")
      (node (ref "R100") (pin "2") (pinfunction "2_2") (pintype "passive"))
      (node (ref "XS22") (pin "3") (pinfunction "3_3") (pintype "passive"))
    )
    (net (code "129") (name "/PowerOff-outa12") (class "Default")
      (node (ref "RL1") (pin "5") (pinfunction "5_5") (pintype "passive"))
      (node (ref "RL1") (pin "6") (pinfunction "6_6") (pintype "passive"))
      (node (ref "XS25") (pin "1") (pinfunction "1_1") (pintype "passive"))
    )
    (net (code "131") (name "/PowerOff-outb12") (class "Default")
      (node (ref "RL1") (pin "1") (pinfunction "5_1") (pintype "passive"))
      (node (ref "XS25") (pin "2") (pinfunction "2_2") (pintype "passive"))
    )
    (net (code "132") (name "/Power_Back") (class "Default")
      (node (ref "C107") (pin "1") (pintype "passive"))
      (node (ref "C108") (pin "1") (pintype "passive"))
      (node (ref "R92") (pin "1") (pinfunction "1_1") (pintype "passive"))
      (node (ref "U2") (pin "41") (pinfunction "PA5_41") (pintype "bidirectional"))
    )
    (net (code "133") (name "/Pulse") (class "Default")
      (node (ref "N8") (pin "5") (pinfunction "Bout_5") (pintype "passive"))
      (node (ref "N8") (pin "7") (pinfunction "Aout_7") (pintype "passive"))
      (node (ref "R35") (pin "2") (pinfunction "2_2") (pintype "passive"))
      (node (ref "U2") (pin "140") (pinfunction "PB9_140") (pintype "bidirectional"))
      (node (ref "U2") (pin "141") (pinfunction "PE0_141") (pintype "bidirectional"))
      (node (ref "XS17") (pin "2") (pinfunction "2_2") (pintype "passive"))
      (node (ref "XS17") (pin "4") (pinfunction "4_4") (pintype "passive"))
      (node (ref "XS17") (pin "6") (pinfunction "6_6") (pintype "passive"))
      (node (ref "XS17") (pin "8") (pinfunction "8_8") (pintype "passive"))
    )
    (net (code "134") (name "/RL11") (class "Default")
      (node (ref "N20") (pin "10") (pinfunction "OUT7_10") (pintype "passive"))
      (node (ref "XS28") (pin "1") (pinfunction "1_1") (pintype "passive"))
    )
    (net (code "135") (name "/RL12") (class "Default")
      (node (ref "RL1") (pin "2") (pinfunction "2_2") (pintype "passive"))
      (node (ref "V19") (pin "1") (pinfunction "A_1") (pintype "passive"))
      (node (ref "XS24") (pin "7") (pinfunction "7_7") (pintype "passive"))
    )
    (net (code "136") (name "/RL21") (class "Default")
      (node (ref "N20") (pin "14") (pinfunction "OUT3_14") (pintype "passive"))
      (node (ref "XS28") (pin "5") (pinfunction "5_5") (pintype "passive"))
    )
    (net (code "137") (name "/RL22") (class "Default")
      (node (ref "RL2") (pin "2") (pinfunction "2_2") (pintype "passive"))
      (node (ref "V20") (pin "1") (pinfunction "A_1") (pintype "passive"))
      (node (ref "XS24") (pin "3") (pinfunction "3_3") (pintype "passive"))
    )
    (net (code "138") (name "/RL31") (class "Default")
      (node (ref "N20") (pin "13") (pinfunction "OUT4_13") (pintype "passive"))
      (node (ref "XS28") (pin "4") (pinfunction "4_4") (pintype "passive"))
    )
    (net (code "139") (name "/RL32") (class "Default")
      (node (ref "RL3") (pin "2") (pinfunction "2_2") (pintype "passive"))
      (node (ref "V21") (pin "1") (pinfunction "A_1") (pintype "passive"))
      (node (ref "XS24") (pin "4") (pinfunction "4_4") (pintype "passive"))
    )
    (net (code "140") (name "/RL41") (class "Default")
      (node (ref "N20") (pin "12") (pinfunction "OUT5_12") (pintype "passive"))
      (node (ref "XS28") (pin "3") (pinfunction "3_3") (pintype "passive"))
    )
    (net (code "141") (name "/RL42") (class "Default")
      (node (ref "RL4") (pin "2") (pinfunction "2_2") (pintype "passive"))
      (node (ref "V22") (pin "1") (pinfunction "A_1") (pintype "passive"))
      (node (ref "XS24") (pin "5") (pinfunction "5_5") (pintype "passive"))
    )
    (net (code "142") (name "/RL51") (class "Default")
      (node (ref "N20") (pin "16") (pinfunction "OUT1_16") (pintype "passive"))
      (node (ref "XS28") (pin "7") (pinfunction "7_7") (pintype "passive"))
    )
    (net (code "143") (name "/RL52") (class "Default")
      (node (ref "RL5") (pin "2") (pinfunction "2_2") (pintype "passive"))
      (node (ref "V23") (pin "1") (pinfunction "A_1") (pintype "passive"))
      (node (ref "XS24") (pin "1") (pinfunction "1_1") (pintype "passive"))
    )
    (net (code "144") (name "/RL61") (class "Default")
      (node (ref "N20") (pin "15") (pinfunction "OUT2_15") (pintype "passive"))
      (node (ref "XS28") (pin "6") (pinfunction "6_6") (pintype "passive"))
    )
    (net (code "145") (name "/RL62") (class "Default")
      (node (ref "RL6") (pin "2") (pinfunction "2_2") (pintype "passive"))
      (node (ref "V24") (pin "1") (pinfunction "A_1") (pintype "passive"))
      (node (ref "XS24") (pin "2") (pinfunction "2_2") (pintype "passive"))
    )
    (net (code "146") (name "/RL71") (class "Default")
      (node (ref "N20") (pin "11") (pinfunction "OUT6_11") (pintype "passive"))
      (node (ref "XS28") (pin "2") (pinfunction "2_2") (pintype "passive"))
    )
    (net (code "147") (name "/RL72") (class "Default")
      (node (ref "RL7") (pin "2") (pinfunction "2_2") (pintype "passive"))
      (node (ref "V25") (pin "1") (pinfunction "A_1") (pintype "passive"))
      (node (ref "XS24") (pin "6") (pinfunction "6_6") (pintype "passive"))
    )
    (net (code "148") (name "/RL81") (class "Default")
      (node (ref "N17") (pin "10") (pinfunction "OUT7_10") (pintype "passive"))
    )
    (net (code "149") (name "/RL82") (class "Default")
      (node (ref "RL8") (pin "2") (pinfunction "2_2") (pintype "passive"))
      (node (ref "V26") (pin "1") (pinfunction "A_1") (pintype "passive"))
      (node (ref "XS30") (pin "1") (pinfunction "1_1") (pintype "passive"))
    )
    (net (code "150") (name "/RXD1") (class "Default")
      (node (ref "D5") (pin "2") (pinfunction "2_2") (pintype "passive"))
      (node (ref "N23") (pin "5") (pinfunction "RxD_5") (pintype "passive"))
      (node (ref "U2") (pin "102") (pinfunction "PA10_102") (pintype "bidirectional"))
    )
    (net (code "151") (name "/Ready11") (class "Default")
      (node (ref "XS23") (pin "4") (pinfunction "4_4") (pintype "passive"))
      (node (ref "XS27") (pin "4") (pinfunction "4_4") (pintype "passive"))
    )
    (net (code "152") (name "/Ready12") (class "Default")
      (node (ref "RL2") (pin "5") (pinfunction "5_5") (pintype "passive"))
      (node (ref "RL2") (pin "6") (pinfunction "6_6") (pintype "passive"))
      (node (ref "XS25") (pin "4") (pinfunction "4_4") (pintype "passive"))
    )
    (net (code "153") (name "/Red_Out11") (class "Default")
      (node (ref "XS12") (pin "3") (pinfunction "3_3") (pintype "passive"))
    )
    (net (code "154") (name "/Red_Out12") (class "Default")
      (node (ref "RL5") (pin "5") (pinfunction "5_5") (pintype "passive"))
      (node (ref "RL5") (pin "6") (pinfunction "6_6") (pintype "passive"))
      (node (ref "XS30") (pin "7") (pinfunction "7_7") (pintype "passive"))
    )
    (net (code "155") (name "/Reset") (class "Default")
      (node (ref "R81") (pin "2") (pinfunction "2_2") (pintype "passive"))
      (node (ref "XS22") (pin "6") (pinfunction "6_6") (pintype "passive"))
    )
    (net (code "156") (name "/START") (class "Default")
      (node (ref "R13") (pin "2") (pinfunction "2_2") (pintype "passive"))
      (node (ref "XS2") (pin "3") (pinfunction "3_3") (pintype "passive"))
    )
    (net (code "157") (name "/STARTMCU") (class "Default")
      (node (ref "D1") (pin "4") (pintype "output"))
      (node (ref "U2") (pin "89") (pinfunction "PG4_89") (pintype "bidirectional"))
    )
    (net (code "158") (name "/Set_Voltage1") (class "Default")
      (node (ref "N17") (pin "2") (pinfunction "IN2_2") (pintype "passive"))
      (node (ref "U2") (pin "136") (pinfunction "PB6_136") (pintype "bidirectional"))
    )
    (net (code "159") (name "/Set_Voltage2") (class "Default")
      (node (ref "N17") (pin "4") (pinfunction "IN4_4") (pintype "passive"))
      (node (ref "U2") (pin "137") (pinfunction "PB7_137") (pintype "bidirectional"))
    )
    (net (code "160") (name "/Set_Voltage3") (class "Default")
      (node (ref "N17") (pin "6") (pinfunction "IN6_6") (pintype "passive"))
      (node (ref "U2") (pin "46") (pinfunction "PB0_46") (pintype "bidirectional"))
    )
    (net (code "161") (name "/Set_Voltage4") (class "Default")
      (node (ref "N26") (pin "2") (pinfunction "IN2_2") (pintype "passive"))
      (node (ref "U2") (pin "47") (pinfunction "PB1_47") (pintype "bidirectional"))
    )
    (net (code "162") (name "/TCK") (class "Default")
      (node (ref "R101") (pin "2") (pinfunction "2_2") (pintype "passive"))
      (node (ref "U2") (pin "109") (pinfunction "PA14_109") (pintype "bidirectional"))
      (node (ref "XS6") (pin "10") (pinfunction "10_10") (pintype "passive"))
    )
    (net (code "163") (name "/TDI") (class "Default")
      (node (ref "R95") (pin "2") (pinfunction "2_2") (pintype "passive"))
      (node (ref "U2") (pin "110") (pinfunction "PA15_110") (pintype "bidirectional"))
      (node (ref "XS6") (pin "5") (pinfunction "5_5") (pintype "passive"))
    )
    (net (code "164") (name "/TDO") (class "Default")
      (node (ref "R93") (pin "2") (pinfunction "2_2") (pintype "passive"))
      (node (ref "U2") (pin "133") (pinfunction "PB3_133") (pintype "bidirectional"))
      (node (ref "XS6") (pin "9") (pinfunction "9_9") (pintype "passive"))
    )
    (net (code "165") (name "/TMS") (class "Default")
      (node (ref "R94") (pin "2") (pinfunction "2_2") (pintype "passive"))
      (node (ref "U2") (pin "105") (pinfunction "PA13_105") (pintype "bidirectional"))
      (node (ref "XS6") (pin "7") (pinfunction "7_7") (pintype "passive"))
    )
    (net (code "166") (name "/TXD1") (class "Default")
      (node (ref "D6") (pin "2") (pinfunction "2_2") (pintype "passive"))
      (node (ref "N23") (pin "8") (pinfunction "TxD_8") (pintype "passive"))
      (node (ref "U2") (pin "101") (pinfunction "PA9_101") (pintype "bidirectional"))
    )
    (net (code "167") (name "/VF OUT1") (class "Default")
      (node (ref "XS18") (pin "3") (pinfunction "3_3") (pintype "passive"))
    )
    (net (code "168") (name "/VF OUT1#") (class "Default")
      (node (ref "R14") (pin "1") (pinfunction "1_1") (pintype "passive"))
    )
    (net (code "169") (name "/VF OUT2") (class "Default")
      (node (ref "XS19") (pin "3") (pinfunction "3_3") (pintype "passive"))
    )
    (net (code "170") (name "/VF OUT2#") (class "Default")
      (node (ref "R48") (pin "1") (pinfunction "1_1") (pintype "passive"))
    )
    (net (code "171") (name "/VF OUT3") (class "Default")
      (node (ref "R50") (pin "1") (pinfunction "1_1") (pintype "passive"))
      (node (ref "XS20") (pin "3") (pinfunction "3_3") (pintype "passive"))
    )
    (net (code "172") (name "/VF OUT4") (class "Default")
      (node (ref "XS16") (pin "3") (pinfunction "3_3") (pintype "passive"))
    )
    (net (code "173") (name "/VF OUT4#") (class "Default")
      (node (ref "R132") (pin "1") (pinfunction "1_1") (pintype "passive"))
    )
    (net (code "174") (name "/VMOS OUT1") (class "Default")
      (node (ref "XS18") (pin "4") (pinfunction "4_4") (pintype "passive"))
    )
    (net (code "175") (name "/VMOS OUT1#") (class "Default")
      (node (ref "R22") (pin "1") (pinfunction "1_1") (pintype "passive"))
    )
    (net (code "176") (name "/VMOS OUT2") (class "Default")
      (node (ref "R60") (pin "1") (pinfunction "1_1") (pintype "passive"))
      (node (ref "XS19") (pin "4") (pinfunction "4_4") (pintype "passive"))
    )
    (net (code "177") (name "/VMOS OUT3") (class "Default")
      (node (ref "R63") (pin "1") (pinfunction "1_1") (pintype "passive"))
      (node (ref "XS20") (pin "4") (pinfunction "4_4") (pintype "passive"))
    )
    (net (code "178") (name "/VMOS OUT4") (class "Default")
      (node (ref "XS16") (pin "4") (pinfunction "4_4") (pintype "passive"))
    )
    (net (code "180") (name "/VREF") (class "Default")
      (node (ref "C45") (pin "1") (pintype "passive"))
      (node (ref "C46") (pin "2") (pinfunction "2_2") (pintype "passive"))
      (node (ref "N12") (pin "6") (pinfunction "OUT_6") (pintype "passive"))
      (node (ref "U2") (pin "32") (pinfunction "VREF+_32") (pintype "power_in"))
    )
    (net (code "181") (name "/Ven_Input1") (class "Default")
      (node (ref "N17") (pin "1") (pinfunction "IN1_1") (pintype "passive"))
      (node (ref "U2") (pin "50") (pinfunction "PF12_50") (pintype "bidirectional"))
    )
    (net (code "182") (name "/Ven_Input2") (class "Default")
      (node (ref "N17") (pin "3") (pinfunction "IN3_3") (pintype "passive"))
      (node (ref "U2") (pin "53") (pinfunction "PF13_53") (pintype "bidirectional"))
    )
    (net (code "183") (name "/Ven_Input3") (class "Default")
      (node (ref "N17") (pin "5") (pinfunction "IN5_5") (pintype "passive"))
      (node (ref "U2") (pin "54") (pinfunction "PF14_54") (pintype "bidirectional"))
    )
    (net (code "184") (name "/Ven_Input4") (class "Default")
      (node (ref "N26") (pin "1") (pinfunction "IN1_1") (pintype "passive"))
      (node (ref "U2") (pin "55") (pinfunction "PF15_55") (pintype "bidirectional"))
    )
    (net (code "185") (name "/Ven_Output1") (class "Default")
      (node (ref "N17") (pin "16") (pinfunction "OUT1_16") (pintype "passive"))
      (node (ref "XS7") (pin "3") (pinfunction "3_3") (pintype "passive"))
    )
    (net (code "186") (name "/Ven_Output2") (class "Default")
      (node (ref "N17") (pin "14") (pinfunction "OUT3_14") (pintype "passive"))
      (node (ref "XS8") (pin "3") (pinfunction "3_3") (pintype "passive"))
    )
    (net (code "187") (name "/Ven_Output3") (class "Default")
      (node (ref "N17") (pin "12") (pinfunction "OUT5_12") (pintype "passive"))
      (node (ref "XS9") (pin "3") (pinfunction "3_3") (pintype "passive"))
    )
    (net (code "188") (name "/Ven_Output4") (class "Default")
      (node (ref "N26") (pin "16") (pinfunction "OUT1_16") (pintype "passive"))
      (node (ref "XS10") (pin "3") (pinfunction "3_3") (pintype "passive"))
    )
    (net (code "189") (name "/Vset_Output1") (class "Default")
      (node (ref "N17") (pin "15") (pinfunction "OUT2_15") (pintype "passive"))
      (node (ref "XS7") (pin "4") (pinfunction "4_4") (pintype "passive"))
    )
    (net (code "190") (name "/Vset_Output2") (class "Default")
      (node (ref "N17") (pin "13") (pinfunction "OUT4_13") (pintype "passive"))
      (node (ref "XS8") (pin "4") (pinfunction "4_4") (pintype "passive"))
    )
    (net (code "191") (name "/Vset_Output3") (class "Default")
      (node (ref "N17") (pin "11") (pinfunction "OUT6_11") (pintype "passive"))
      (node (ref "XS9") (pin "4") (pinfunction "4_4") (pintype "passive"))
    )
    (net (code "192") (name "/Vset_Output4") (class "Default")
      (node (ref "N26") (pin "15") (pinfunction "OUT2_15") (pintype "passive"))
      (node (ref "XS10") (pin "4") (pinfunction "4_4") (pintype "passive"))
    )
    (net (code "194") (name "/Water-") (class "Default")
      (node (ref "VR4") (pin "5") (pinfunction "5_5") (pintype "passive"))
      (node (ref "VR4") (pin "6") (pinfunction "6_6") (pintype "passive"))
    )
    (net (code "195") (name "/Water_Fault") (class "Default")
      (node (ref "N25") (pin "12") (pinfunction "C_12") (pintype "passive"))
      (node (ref "R142") (pin "1") (pinfunction "1_1") (pintype "passive"))
      (node (ref "U2") (pin "15") (pinfunction "PF5_15") (pintype "bidirectional"))
      (node (ref "V10") (pin "1") (pinfunction "A_1") (pintype "passive"))
    )
    (net (code "196") (name "/Water_Flow") (class "Default")
      (node (ref "C102") (pin "2") (pinfunction "2_2") (pintype "passive"))
      (node (ref "N24") (pin "1") (pinfunction "IN+_1") (pintype "passive"))
      (node (ref "R113") (pin "1") (pinfunction "1_1") (pintype "passive"))
      (node (ref "R118") (pin "1") (pinfunction "1_1") (pintype "passive"))
      (node (ref "XS12") (pin "10") (pinfunction "10_10") (pintype "passive"))
    )
    (net (code "197") (name "/Water_IN-") (class "Default")
      (node (ref "R26") (pin "2") (pinfunction "2_2") (pintype "passive"))
      (node (ref "XS12") (pin "12") (pinfunction "12_12") (pintype "passive"))
    )
    (net (code "198") (name "/Water_OUT") (class "Default")
      (node (ref "R124") (pin "2") (pinfunction "2_2") (pintype "passive"))
      (node (ref "R29") (pin "2") (pinfunction "2_2") (pintype "passive"))
      (node (ref "V10") (pin "2") (pinfunction "K_2") (pintype "passive"))
      (node (ref "V2") (pin "2") (pinfunction "K_2") (pintype "passive"))
      (node (ref "V37") (pin "2") (pinfunction "K_2") (pintype "passive"))
      (node (ref "V4") (pin "2") (pinfunction "K_2") (pintype "passive"))
      (node (ref "V5") (pin "2") (pinfunction "K_2") (pintype "passive"))
      (node (ref "V6") (pin "2") (pinfunction "K_2") (pintype "passive"))
      (node (ref "V8") (pin "2") (pinfunction "K_2") (pintype "passive"))
      (node (ref "V9") (pin "2") (pinfunction "K_2") (pintype "passive"))
    )
    (net (code "199") (name "/Work_State") (class "Default")
      (node (ref "N20") (pin "7") (pinfunction "IN7_7") (pintype "passive"))
      (node (ref "U2") (pin "124") (pinfunction "PG9_124") (pintype "bidirectional"))
    )
    (net (code "200") (name "/Y1") (class "Default")
      (node (ref "R114") (pin "2") (pinfunction "2_2") (pintype "passive"))
      (node (ref "U4") (pin "10") (pinfunction "Y_10") (pintype "passive"))
      (node (ref "V32") (pin "K") (pintype "passive"))
      (node (ref "XS13") (pin "4") (pinfunction "4_4") (pintype "passive"))
    )
    (net (code "201") (name "/Yellow_Out11") (class "Default")
      (node (ref "XS12") (pin "5") (pinfunction "5_5") (pintype "passive"))
    )
    (net (code "202") (name "/Yellow_Out12") (class "Default")
      (node (ref "RL6") (pin "5") (pinfunction "5_5") (pintype "passive"))
      (node (ref "RL6") (pin "6") (pinfunction "6_6") (pintype "passive"))
      (node (ref "XS30") (pin "6") (pinfunction "6_6") (pintype "passive"))
    )
    (net (code "203") (name "/Z1") (class "Default")
      (node (ref "R114") (pin "1") (pinfunction "1_1") (pintype "passive"))
      (node (ref "U4") (pin "11") (pinfunction "Z_11") (pintype "passive"))
      (node (ref "V28") (pin "K") (pintype "passive"))
      (node (ref "XS13") (pin "3") (pinfunction "3_3") (pintype "passive"))
    )
    (net (code "204") (name "24VGND") (class "Default")
      (node (ref "C102") (pin "1") (pinfunction "1_1") (pintype "passive"))
      (node (ref "C12") (pin "2") (pinfunction "2_2") (pintype "passive"))
      (node (ref "C13") (pin "2") (pinfunction "2_2") (pintype "passive"))
      (node (ref "C16") (pin "2") (pinfunction "2_2") (pintype "passive"))
      (node (ref "C19") (pin "2") (pinfunction "2_2") (pintype "passive"))
      (node (ref "C24") (pin "1") (pinfunction "1_1") (pintype "passive"))
      (node (ref "C25") (pin "1") (pinfunction "1_1") (pintype "passive"))
      (node (ref "C27") (pin "1") (pinfunction "1_1") (pintype "passive"))
      (node (ref "C47") (pin "2") (pinfunction "2_2") (pintype "passive"))
      (node (ref "C48") (pin "2") (pinfunction "2_2") (pintype "passive"))
      (node (ref "C49") (pin "2") (pinfunction "2_2") (pintype "passive"))
      (node (ref "C50") (pin "2") (pinfunction "2_2") (pintype "passive"))
      (node (ref "C51") (pin "2") (pinfunction "2_2") (pintype "passive"))
      (node (ref "C53") (pin "2") (pinfunction "2_2") (pintype "passive"))
      (node (ref "C54") (pin "2") (pinfunction "2_2") (pintype "passive"))
      (node (ref "C57") (pin "1") (pinfunction "1_1") (pintype "passive"))
      (node (ref "C59") (pin "1") (pinfunction "1_1") (pintype "passive"))
      (node (ref "C62") (pin "1") (pinfunction "1_1") (pintype "passive"))
      (node (ref "C64") (pin "1") (pinfunction "1_1") (pintype "passive"))
      (node (ref "C66") (pin "1") (pinfunction "1_1") (pintype "passive"))
      (node (ref "C68") (pin "1") (pinfunction "1_1") (pintype "passive"))
      (node (ref "C68") (pin "2") (pinfunction "2_2") (pintype "passive"))
      (node (ref "C69") (pin "1") (pinfunction "1_1") (pintype "passive"))
      (node (ref "C69") (pin "2") (pinfunction "2_2") (pintype "passive"))
      (node (ref "C70") (pin "1") (pinfunction "1_1") (pintype "passive"))
      (node (ref "N13") (pin "2") (pinfunction "K_2") (pintype "passive"))
      (node (ref "N13") (pin "4") (pinfunction "K_4") (pintype "passive"))
      (node (ref "N13") (pin "6") (pinfunction "K_6") (pintype "passive"))
      (node (ref "N13") (pin "8") (pinfunction "K_8") (pintype "passive"))
      (node (ref "N15") (pin "2") (pinfunction "K_2") (pintype "passive"))
      (node (ref "N15") (pin "4") (pinfunction "K_4") (pintype "passive"))
      (node (ref "N15") (pin "6") (pinfunction "K_6") (pintype "passive"))
      (node (ref "N15") (pin "8") (pinfunction "K_8") (pintype "passive"))
      (node (ref "N16") (pin "3") (pinfunction "V-_3") (pintype "passive"))
      (node (ref "N2") (pin "2") (pinfunction "GND_2") (pintype "passive"))
      (node (ref "N24") (pin "3") (pinfunction "IN-_3") (pintype "passive"))
      (node (ref "N25") (pin "2") (pinfunction "K_2") (pintype "passive"))
      (node (ref "N25") (pin "4") (pinfunction "K_4") (pintype "passive"))
      (node (ref "N25") (pin "6") (pinfunction "K_6") (pintype "passive"))
      (node (ref "N4") (pin "1") (pinfunction "GND_1") (pintype "passive"))
      (node (ref "N5") (pin "2") (pinfunction "GND_2") (pintype "passive"))
      (node (ref "N7") (pin "2") (pinfunction "GND_2") (pintype "passive"))
      (node (ref "R102") (pin "2") (pinfunction "2_2") (pintype "passive"))
      (node (ref "R103") (pin "2") (pinfunction "2_2") (pintype "passive"))
      (node (ref "R118") (pin "2") (pinfunction "2_2") (pintype "passive"))
      (node (ref "R31") (pin "2") (pinfunction "2_2") (pintype "passive"))
      (node (ref "R78") (pin "2") (pinfunction "2_2") (pintype "passive"))
      (node (ref "R83") (pin "1") (pinfunction "1_1") (pintype "passive"))
      (node (ref "R85") (pin "2") (pinfunction "2_2") (pintype "passive"))
      (node (ref "R87") (pin "1") (pinfunction "1_1") (pintype "passive"))
      (node (ref "R90") (pin "2") (pinfunction "2_2") (pintype "passive"))
      (node (ref "R91") (pin "2") (pinfunction "2_2") (pintype "passive"))
      (node (ref "U5") (pin "4") (pintype "passive"))
      (node (ref "U5") (pin "7") (pintype "passive"))
      (node (ref "XS1") (pin "3") (pinfunction "3_3") (pintype "passive"))
      (node (ref "XS1") (pin "4") (pinfunction "4_4") (pintype "passive"))
      (node (ref "XS12") (pin "4") (pinfunction "4_4") (pintype "passive"))
      (node (ref "XS12") (pin "6") (pinfunction "6_6") (pintype "passive"))
      (node (ref "XS12") (pin "8") (pinfunction "8_8") (pintype "passive"))
      (node (ref "XS21") (pin "1") (pinfunction "1_1") (pintype "passive"))
      (node (ref "XS21") (pin "3") (pinfunction "3_3") (pintype "passive"))
      (node (ref "XS22") (pin "1") (pinfunction "1_1") (pintype "passive"))
      (node (ref "XS23") (pin "6") (pinfunction "6_6") (pintype "passive"))
      (node (ref "XS27") (pin "6") (pinfunction "6_6") (pintype "passive"))
      (node (ref "XS4") (pin "7") (pinfunction "7_7") (pintype "passive"))
    )
    (net (code "205") (name "DP1") (class "Default")
      (node (ref "N23") (pin "6") (pinfunction "/RE_6") (pintype "passive"))
      (node (ref "U2") (pin "103") (pinfunction "PA11_103") (pintype "bidirectional"))
    )
    (net (code "206") (name "DP2") (class "Default")
      (node (ref "N23") (pin "7") (pinfunction "RTS_7") (pintype "passive"))
      (node (ref "U2") (pin "104") (pinfunction "PA12_104") (pintype "bidirectional"))
    )
    (net (code "207") (name "GND") (class "Default")
      (node (ref "C1") (pin "1") (pinfunction "1_1") (pintype "passive"))
      (node (ref "C10") (pin "2") (pinfunction "2_2") (pintype "passive"))
      (node (ref "C107") (pin "2") (pintype "passive"))
      (node (ref "C108") (pin "2") (pintype "passive"))
      (node (ref "C11") (pin "1") (pinfunction "1_1") (pintype "passive"))
      (node (ref "C15") (pin "2") (pinfunction "2_2") (pintype "passive"))
      (node (ref "C17") (pin "2") (pinfunction "2_2") (pintype "passive"))
      (node (ref "C18") (pin "2") (pinfunction "2_2") (pintype "passive"))
      (node (ref "C22") (pin "2") (pinfunction "2_2") (pintype "passive"))
      (node (ref "C23") (pin "1") (pinfunction "1_1") (pintype "passive"))
      (node (ref "C26") (pin "1") (pinfunction "1_1") (pintype "passive"))
      (node (ref "C29") (pin "2") (pinfunction "2_2") (pintype "passive"))
      (node (ref "C30") (pin "2") (pinfunction "2_2") (pintype "passive"))
      (node (ref "C31") (pin "2") (pinfunction "2_2") (pintype "passive"))
      (node (ref "C32") (pin "2") (pinfunction "2_2") (pintype "passive"))
      (node (ref "C33") (pin "2") (pinfunction "2_2") (pintype "passive"))
      (node (ref "C34") (pin "2") (pinfunction "2_2") (pintype "passive"))
      (node (ref "C35") (pin "2") (pinfunction "2_2") (pintype "passive"))
      (node (ref "C36") (pin "2") (pinfunction "2_2") (pintype "passive"))
      (node (ref "C37") (pin "2") (pinfunction "2_2") (pintype "passive"))
      (node (ref "C38") (pin "2") (pinfunction "2_2") (pintype "passive"))
      (node (ref "C39") (pin "2") (pinfunction "2_2") (pintype "passive"))
      (node (ref "C4") (pin "2") (pinfunction "2_2") (pintype "passive"))
      (node (ref "C40") (pin "2") (pinfunction "2_2") (pintype "passive"))
      (node (ref "C41") (pin "2") (pinfunction "2_2") (pintype "passive"))
      (node (ref "C42") (pin "2") (pinfunction "2_2") (pintype "passive"))
      (node (ref "C43") (pin "1") (pinfunction "1_1") (pintype "passive"))
      (node (ref "C44") (pin "1") (pinfunction "1_1") (pintype "passive"))
      (node (ref "C45") (pin "2") (pintype "passive"))
      (node (ref "C46") (pin "1") (pinfunction "1_1") (pintype "passive"))
      (node (ref "C5") (pin "2") (pinfunction "2_2") (pintype "passive"))
      (node (ref "C52") (pin "2") (pinfunction "2_2") (pintype "passive"))
      (node (ref "C55") (pin "1") (pinfunction "1_1") (pintype "passive"))
      (node (ref "C56") (pin "2") (pinfunction "2_2") (pintype "passive"))
      (node (ref "C58") (pin "2") (pinfunction "2_2") (pintype "passive"))
      (node (ref "C6") (pin "2") (pinfunction "2_2") (pintype "passive"))
      (node (ref "C60") (pin "1") (pinfunction "1_1") (pintype "passive"))
      (node (ref "C61") (pin "1") (pinfunction "1_1") (pintype "passive"))
      (node (ref "C63") (pin "2") (pinfunction "2_2") (pintype "passive"))
      (node (ref "C65") (pin "1") (pinfunction "1_1") (pintype "passive"))
      (node (ref "C67") (pin "1") (pinfunction "1_1") (pintype "passive"))
      (node (ref "C7") (pin "2") (pinfunction "2_2") (pintype "passive"))
      (node (ref "C71") (pin "1") (pinfunction "1_1") (pintype "passive"))
      (node (ref "C72") (pin "2") (pintype "passive"))
      (node (ref "C73") (pin "2") (pintype "passive"))
      (node (ref "C74") (pin "2") (pintype "passive"))
      (node (ref "C75") (pin "2") (pintype "passive"))
      (node (ref "C76") (pin "2") (pintype "passive"))
      (node (ref "C77") (pin "2") (pintype "passive"))
      (node (ref "C78") (pin "2") (pintype "passive"))
      (node (ref "C79") (pin "2") (pintype "passive"))
      (node (ref "C8") (pin "2") (pinfunction "2_2") (pintype "passive"))
      (node (ref "C80") (pin "1") (pintype "passive"))
      (node (ref "C81") (pin "2") (pinfunction "2_2") (pintype "passive"))
      (node (ref "C82") (pin "1") (pinfunction "1_1") (pintype "passive"))
      (node (ref "C83") (pin "1") (pinfunction "1_1") (pintype "passive"))
      (node (ref "C84") (pin "2") (pinfunction "2_2") (pintype "passive"))
      (node (ref "C85") (pin "2") (pinfunction "2_2") (pintype "passive"))
      (node (ref "C86") (pin "2") (pintype "passive"))
      (node (ref "C87") (pin "2") (pintype "passive"))
      (node (ref "C88") (pin "1") (pinfunction "1_1") (pintype "passive"))
      (node (ref "C89") (pin "1") (pinfunction "1_1") (pintype "passive"))
      (node (ref "C9") (pin "2") (pinfunction "2_2") (pintype "passive"))
      (node (ref "C95") (pin "2") (pinfunction "2_2") (pintype "passive"))
      (node (ref "C96") (pin "2") (pinfunction "2_2") (pintype "passive"))
      (node (ref "C97") (pin "2") (pinfunction "2_2") (pintype "passive"))
      (node (ref "C98") (pin "2") (pintype "passive"))
      (node (ref "C99") (pin "2") (pinfunction "2_2") (pintype "passive"))
      (node (ref "D1") (pin "7") (pinfunction "GND_7") (pintype "power_in"))
      (node (ref "D2") (pin "2") (pinfunction "2_2") (pintype "passive"))
      (node (ref "D3") (pin "2") (pinfunction "2_2") (pintype "passive"))
      (node (ref "N10") (pin "3") (pinfunction "GND_3") (pintype "passive"))
      (node (ref "N10") (pin "7") (pinfunction "VSS_7") (pintype "passive"))
      (node (ref "N11") (pin "11") (pintype "passive"))
      (node (ref "N12") (pin "4") (pinfunction "GND_4") (pintype "passive"))
      (node (ref "N17") (pin "8") (pinfunction "GND_8") (pintype "passive"))
      (node (ref "N18") (pin "4") (pinfunction "AGND_4") (pintype "passive"))
      (node (ref "N18") (pin "6") (pinfunction "DGND_6") (pintype "passive"))
      (node (ref "N18") (pin "7") (pinfunction "~{LDAC}_7") (pintype "passive"))
      (node (ref "N19") (pin "4") (pinfunction "GND_4") (pintype "passive"))
      (node (ref "N2") (pin "3") (pinfunction "V-_3") (pintype "passive"))
      (node (ref "N20") (pin "8") (pinfunction "GND_8") (pintype "passive"))
      (node (ref "N21") (pin "8") (pinfunction "GND_8") (pintype "passive"))
      (node (ref "N22") (pin "2") (pinfunction "GND_2") (pintype "passive"))
      (node (ref "N23") (pin "3") (pinfunction "GND1_3") (pintype "passive"))
      (node (ref "N24") (pin "4") (pinfunction "GND_4") (pintype "passive"))
      (node (ref "N25") (pin "11") (pinfunction "E_11") (pintype "passive"))
      (node (ref "N26") (pin "8") (pinfunction "GND_8") (pintype "passive"))
      (node (ref "N5") (pin "3") (pinfunction "V-_3") (pintype "passive"))
      (node (ref "N7") (pin "4") (pinfunction "V+_4") (pintype "passive"))
      (node (ref "N8") (pin "3") (pinfunction "GND_3") (pintype "passive"))
      (node (ref "R101") (pin "1") (pinfunction "1_1") (pintype "passive"))
      (node (ref "R104") (pin "2") (pinfunction "2_2") (pintype "passive"))
      (node (ref "R107") (pin "1") (pinfunction "1_1") (pintype "passive"))
      (node (ref "R11") (pin "2") (pinfunction "2_2") (pintype "passive"))
      (node (ref "R15") (pin "1") (pinfunction "1_1") (pintype "passive"))
      (node (ref "R18") (pin "2") (pinfunction "2_2") (pintype "passive"))
      (node (ref "R21") (pin "2") (pinfunction "2_2") (pintype "passive"))
      (node (ref "R24") (pin "2") (pinfunction "2_2") (pintype "passive"))
      (node (ref "R28") (pin "2") (pinfunction "2_2") (pintype "passive"))
      (node (ref "R29") (pin "1") (pinfunction "1_1") (pintype "passive"))
      (node (ref "R30") (pin "1") (pinfunction "1_1") (pintype "passive"))
      (node (ref "R34") (pin "2") (pinfunction "2_2") (pintype "passive"))
      (node (ref "R41") (pin "2") (pinfunction "2_2") (pintype "passive"))
      (node (ref "R45") (pin "1") (pinfunction "1_1") (pintype "passive"))
      (node (ref "R47") (pin "2") (pinfunction "2_2") (pintype "passive"))
      (node (ref "R54") (pin "1") (pinfunction "1_1") (pintype "passive"))
      (node (ref "R58") (pin "2") (pinfunction "2_2") (pintype "passive"))
      (node (ref "R59") (pin "2") (pinfunction "2_2") (pintype "passive"))
      (node (ref "R6") (pin "1") (pinfunction "1_1") (pintype "passive"))
      (node (ref "R61") (pin "2") (pinfunction "2_2") (pintype "passive"))
      (node (ref "R67") (pin "2") (pinfunction "2_2") (pintype "passive"))
      (node (ref "R69") (pin "2") (pinfunction "2_2") (pintype "passive"))
      (node (ref "R71") (pin "2") (pinfunction "2_2") (pintype "passive"))
      (node (ref "R72") (pin "2") (pinfunction "2_2") (pintype "passive"))
      (node (ref "R77") (pin "1") (pinfunction "1_1") (pintype "passive"))
      (node (ref "R79") (pin "2") (pinfunction "2_2") (pintype "passive"))
      (node (ref "R80") (pin "2") (pinfunction "2_2") (pintype "passive"))
      (node (ref "R82") (pin "2") (pinfunction "2_2") (pintype "passive"))
      (node (ref "R83") (pin "2") (pinfunction "2_2") (pintype "passive"))
      (node (ref "R84") (pin "1") (pinfunction "1_1") (pintype "passive"))
      (node (ref "R88") (pin "2") (pinfunction "2_2") (pintype "passive"))
      (node (ref "R97") (pin "2") (pinfunction "2_2") (pintype "passive"))
      (node (ref "R98") (pin "1") (pinfunction "1_1") (pintype "passive"))
      (node (ref "R99") (pin "2") (pinfunction "2_2") (pintype "passive"))
      (node (ref "S1") (pin "1") (pinfunction "COMMON_1") (pintype "passive"))
      (node (ref "U1") (pin "1") (pinfunction "GND_1") (pintype "passive"))
      (node (ref "U2") (pin "107") (pinfunction "VSS_2_107") (pintype "power_in"))
      (node (ref "U2") (pin "120") (pinfunction "VSS_10_120") (pintype "power_in"))
      (node (ref "U2") (pin "130") (pinfunction "VSS_11_130") (pintype "power_in"))
      (node (ref "U2") (pin "143") (pinfunction "VSS_3_143") (pintype "power_in"))
      (node (ref "U2") (pin "16") (pinfunction "VSS_5_16") (pintype "power_in"))
      (node (ref "U2") (pin "30") (pinfunction "VSSA_30") (pintype "power_in"))
      (node (ref "U2") (pin "31") (pinfunction "VREF-_31") (pintype "power_in"))
      (node (ref "U2") (pin "38") (pinfunction "VSS_4_38") (pintype "power_in"))
      (node (ref "U2") (pin "51") (pinfunction "VSS_6_51") (pintype "power_in"))
      (node (ref "U2") (pin "61") (pinfunction "VSS_7_61") (pintype "power_in"))
      (node (ref "U2") (pin "71") (pinfunction "VSS_1_71") (pintype "power_in"))
      (node (ref "U2") (pin "83") (pinfunction "VSS_8_83") (pintype "power_in"))
      (node (ref "U2") (pin "94") (pinfunction "VSS_9_94") (pintype "power_in"))
      (node (ref "U3") (pin "2") (pintype "passive"))
      (node (ref "U3") (pin "4") (pintype "passive"))
      (node (ref "U4") (pin "2") (pinfunction "GND1_2") (pintype "passive"))
      (node (ref "U4") (pin "5") (pinfunction "GND1_5") (pintype "passive"))
      (node (ref "U4") (pin "8") (pinfunction "GND1_8") (pintype "passive"))
      (node (ref "V13") (pin "1") (pinfunction "A_1") (pintype "passive"))
      (node (ref "V15") (pin "1") (pinfunction "A_1") (pintype "passive"))
      (node (ref "V17") (pin "1") (pinfunction "A_1") (pintype "passive"))
      (node (ref "V18") (pin "1") (pinfunction "A_1") (pintype "passive"))
      (node (ref "V33") (pin "C") (pinfunction "C_C") (pintype "passive"))
      (node (ref "XS14") (pin "8") (pinfunction "8_8") (pintype "passive"))
      (node (ref "XS17") (pin "10") (pinfunction "10_10") (pintype "passive"))
      (node (ref "XS17") (pin "11") (pinfunction "11_11") (pintype "passive"))
      (node (ref "XS17") (pin "12") (pinfunction "12_12") (pintype "passive"))
      (node (ref "XS17") (pin "9") (pinfunction "9_9") (pintype "passive"))
      (node (ref "XS6") (pin "8") (pinfunction "8_8") (pintype "passive"))
    )
    (net (code "208") (name "GND#") (class "Default")
      (node (ref "C106") (pin "2") (pinfunction "2_2") (pintype "passive"))
      (node (ref "C2") (pin "2") (pinfunction "2_2") (pintype "passive"))
      (node (ref "C28") (pin "2") (pinfunction "2_2") (pintype "passive"))
      (node (ref "N14") (pin "11") (pintype "passive"))
      (node (ref "N3") (pin "11") (pintype "passive"))
      (node (ref "N9") (pin "11") (pintype "passive"))
      (node (ref "R1") (pin "2") (pinfunction "2_2") (pintype "passive"))
      (node (ref "R105") (pin "2") (pinfunction "2_2") (pintype "passive"))
      (node (ref "R12") (pin "2") (pinfunction "2_2") (pintype "passive"))
      (node (ref "R131") (pin "2") (pinfunction "2_2") (pintype "passive"))
      (node (ref "R134") (pin "2") (pinfunction "2_2") (pintype "passive"))
      (node (ref "R20") (pin "2") (pinfunction "2_2") (pintype "passive"))
      (node (ref "R33") (pin "2") (pinfunction "2_2") (pintype "passive"))
      (node (ref "R46") (pin "2") (pinfunction "2_2") (pintype "passive"))
      (node (ref "R56") (pin "2") (pinfunction "2_2") (pintype "passive"))
      (node (ref "V11") (pin "1") (pinfunction "A_1") (pintype "passive"))
      (node (ref "V12") (pin "1") (pinfunction "A_1") (pintype "passive"))
      (node (ref "V14") (pin "1") (pinfunction "A_1") (pintype "passive"))
      (node (ref "V16") (pin "1") (pinfunction "A_1") (pintype "passive"))
      (node (ref "V3") (pin "1") (pinfunction "A_1") (pintype "passive"))
      (node (ref "V34") (pin "1") (pinfunction "A_1") (pintype "passive"))
      (node (ref "V35") (pin "1") (pinfunction "A_1") (pintype "passive"))
      (node (ref "V36") (pin "1") (pinfunction "A_1") (pintype "passive"))
      (node (ref "V7") (pin "1") (pinfunction "A_1") (pintype "passive"))
    )
    (net (code "209") (name "GNDISO1") (class "Default")
      (node (ref "C101") (pin "2") (pinfunction "2_2") (pintype "passive"))
      (node (ref "C90") (pin "1") (pintype "passive"))
      (node (ref "C91") (pin "1") (pinfunction "1_1") (pintype "passive"))
      (node (ref "C92") (pin "2") (pinfunction "2_2") (pintype "passive"))
      (node (ref "C94") (pin "2") (pinfunction "2_2") (pintype "passive"))
      (node (ref "N22") (pin "3") (pinfunction "V-_3") (pintype "passive"))
      (node (ref "R115") (pin "2") (pinfunction "2_2") (pintype "passive"))
      (node (ref "R123") (pin "1") (pinfunction "1_1") (pintype "passive"))
      (node (ref "U4") (pin "9") (pinfunction "GND2_9") (pintype "passive"))
      (node (ref "V27") (pin "A") (pintype "passive"))
      (node (ref "V28") (pin "A") (pintype "passive"))
      (node (ref "V29") (pin "A") (pintype "passive"))
      (node (ref "V32") (pin "A") (pintype "passive"))
      (node (ref "XS13") (pin "5") (pinfunction "5_5") (pintype "passive"))
      (node (ref "XS15") (pin "3") (pinfunction "3_3") (pintype "passive"))
    )
    (net (code "210") (name "LD_GND1") (class "Default")
      (node (ref "C20") (pin "2") (pinfunction "2_2") (pintype "passive"))
      (node (ref "N6") (pin "2") (pinfunction "K_2") (pintype "passive"))
      (node (ref "XS18") (pin "5") (pinfunction "5_5") (pintype "passive"))
    )
    (net (code "211") (name "LD_GND1#") (class "Default")
      (node (ref "R17") (pin "1") (pinfunction "1_1") (pintype "passive"))
      (node (ref "R27") (pin "1") (pinfunction "1_1") (pintype "passive"))
      (node (ref "R8") (pin "1") (pinfunction "1_1") (pintype "passive"))
    )
    (net (code "212") (name "LD_GND2") (class "Default")
      (node (ref "C21") (pin "1") (pinfunction "1_1") (pintype "passive"))
      (node (ref "N6") (pin "4") (pinfunction "K_4") (pintype "passive"))
      (node (ref "XS19") (pin "5") (pinfunction "5_5") (pintype "passive"))
    )
    (net (code "213") (name "LD_GND2#") (class "Default")
      (node (ref "R40") (pin "1") (pinfunction "1_1") (pintype "passive"))
      (node (ref "R51") (pin "1") (pinfunction "1_1") (pintype "passive"))
      (node (ref "R64") (pin "1") (pinfunction "1_1") (pintype "passive"))
    )
    (net (code "214") (name "LD_GND3") (class "Default")
      (node (ref "C3") (pin "1") (pinfunction "1_1") (pintype "passive"))
      (node (ref "N6") (pin "6") (pinfunction "K_6") (pintype "passive"))
      (node (ref "R42") (pin "1") (pinfunction "1_1") (pintype "passive"))
      (node (ref "R53") (pin "1") (pinfunction "1_1") (pintype "passive"))
      (node (ref "R66") (pin "1") (pinfunction "1_1") (pintype "passive"))
      (node (ref "XS20") (pin "5") (pinfunction "5_5") (pintype "passive"))
    )
    (net (code "215") (name "LD_GND4") (class "Default")
      (node (ref "C105") (pin "1") (pinfunction "1_1") (pintype "passive"))
      (node (ref "N6") (pin "8") (pinfunction "K_8") (pintype "passive"))
      (node (ref "XS16") (pin "5") (pinfunction "5_5") (pintype "passive"))
    )
    (net (code "216") (name "LD_GND4#") (class "Default")
      (node (ref "R128") (pin "1") (pinfunction "1_1") (pintype "passive"))
      (node (ref "R133") (pin "1") (pinfunction "1_1") (pintype "passive"))
      (node (ref "R138") (pin "1") (pinfunction "1_1") (pintype "passive"))
    )
    (net (code "217") (name "Net-(C6-Pad1)") (class "Default")
      (node (ref "C6") (pin "1") (pinfunction "1_1") (pintype "passive"))
      (node (ref "D1") (pin "1") (pintype "input"))
      (node (ref "R2") (pin "1") (pinfunction "1_1") (pintype "passive"))
      (node (ref "R6") (pin "2") (pinfunction "2_2") (pintype "passive"))
    )
    (net (code "218") (name "Net-(C18-Pad1)") (class "Default")
      (node (ref "C18") (pin "1") (pinfunction "1_1") (pintype "passive"))
      (node (ref "D1") (pin "3") (pintype "input"))
      (node (ref "R13") (pin "1") (pinfunction "1_1") (pintype "passive"))
      (node (ref "R15") (pin "2") (pinfunction "2_2") (pintype "passive"))
    )
    (net (code "219") (name "Net-(C22-Pad1)") (class "Default")
      (node (ref "C22") (pin "1") (pinfunction "1_1") (pintype "passive"))
      (node (ref "D1") (pin "5") (pintype "input"))
      (node (ref "R23") (pin "1") (pinfunction "1_1") (pintype "passive"))
      (node (ref "R30") (pin "2") (pinfunction "2_2") (pintype "passive"))
    )
    (net (code "220") (name "Net-(C25-Pad2)") (class "Default")
      (node (ref "C25") (pin "2") (pinfunction "2_2") (pintype "passive"))
      (node (ref "N25") (pin "5") (pinfunction "A_5") (pintype "passive"))
      (node (ref "R26") (pin "1") (pinfunction "1_1") (pintype "passive"))
      (node (ref "R31") (pin "1") (pinfunction "1_1") (pintype "passive"))
    )
    (net (code "221") (name "Net-(C56-Pad1)") (class "Default")
      (node (ref "C56") (pin "1") (pinfunction "1_1") (pintype "passive"))
      (node (ref "R71") (pin "1") (pinfunction "1_1") (pintype "passive"))
      (node (ref "R73") (pin "2") (pinfunction "2_2") (pintype "passive"))
      (node (ref "R77") (pin "2") (pinfunction "2_2") (pintype "passive"))
      (node (ref "U3") (pin "3") (pintype "passive"))
    )
    (net (code "222") (name "Net-(C57-Pad2)") (class "Default")
      (node (ref "C57") (pin "2") (pinfunction "2_2") (pintype "passive"))
      (node (ref "N15") (pin "1") (pinfunction "A_1") (pintype "passive"))
      (node (ref "R74") (pin "1") (pinfunction "1_1") (pintype "passive"))
      (node (ref "R78") (pin "1") (pinfunction "1_1") (pintype "passive"))
    )
    (net (code "223") (name "Net-(C59-Pad2)") (class "Default")
      (node (ref "C59") (pin "2") (pinfunction "2_2") (pintype "passive"))
      (node (ref "N15") (pin "3") (pinfunction "A_3") (pintype "passive"))
      (node (ref "R81") (pin "1") (pinfunction "1_1") (pintype "passive"))
      (node (ref "R85") (pin "1") (pinfunction "1_1") (pintype "passive"))
    )
    (net (code "224") (name "Net-(C61-Pad2)") (class "Default")
      (node (ref "C61") (pin "2") (pinfunction "2_2") (pintype "passive"))
      (node (ref "R75") (pin "1") (pinfunction "1_1") (pintype "passive"))
      (node (ref "R84") (pin "2") (pinfunction "2_2") (pintype "passive"))
      (node (ref "U3") (pin "1") (pintype "passive"))
    )
    (net (code "225") (name "Net-(C64-Pad2)") (class "Default")
      (node (ref "C64") (pin "2") (pinfunction "2_2") (pintype "passive"))
      (node (ref "N15") (pin "5") (pinfunction "A_5") (pintype "passive"))
      (node (ref "R89") (pin "1") (pinfunction "1_1") (pintype "passive"))
      (node (ref "R91") (pin "1") (pinfunction "1_1") (pintype "passive"))
    )
    (net (code "226") (name "Net-(C70-Pad2)") (class "Default")
      (node (ref "C70") (pin "2") (pinfunction "2_2") (pintype "passive"))
      (node (ref "N15") (pin "7") (pinfunction "A_7") (pintype "passive"))
      (node (ref "R100") (pin "1") (pinfunction "1_1") (pintype "passive"))
      (node (ref "R102") (pin "1") (pinfunction "1_1") (pintype "passive"))
    )
    (net (code "227") (name "Net-(C101-Pad1)") (class "Default")
      (node (ref "C101") (pin "1") (pinfunction "1_1") (pintype "passive"))
      (node (ref "C93") (pin "2") (pinfunction "2_2") (pintype "passive"))
    )
    (net (code "228") (name "Net-(C103-Pad2)") (class "Default")
      (node (ref "C103") (pin "2") (pinfunction "2_2") (pintype "passive"))
      (node (ref "C104") (pin "2") (pinfunction "2_2") (pintype "passive"))
      (node (ref "N23") (pin "11") (pinfunction "GND2_11") (pintype "passive"))
      (node (ref "N23") (pin "14") (pinfunction "GND2_14") (pintype "passive"))
      (node (ref "N23") (pin "15") (pinfunction "GND2_15") (pintype "passive"))
      (node (ref "N23") (pin "9") (pinfunction "GND2_9") (pintype "passive"))
      (node (ref "R117") (pin "2") (pinfunction "2_2") (pintype "passive"))
      (node (ref "V30") (pin "A") (pintype "passive"))
      (node (ref "V31") (pin "A") (pintype "passive"))
    )
    (net (code "229") (name "Net-(D2-Pad1)") (class "Default")
      (node (ref "D2") (pin "1") (pinfunction "1_1") (pintype "passive"))
      (node (ref "R35") (pin "1") (pinfunction "1_1") (pintype "passive"))
    )
    (net (code "230") (name "Net-(D3-Pad1)") (class "Default")
      (node (ref "D3") (pin "1") (pinfunction "1_1") (pintype "passive"))
      (node (ref "R108") (pin "2") (pinfunction "2_2") (pintype "passive"))
    )
    (net (code "231") (name "Net-(D4-Pad1)") (class "Default")
      (node (ref "D4") (pin "1") (pinfunction "1_1") (pintype "passive"))
      (node (ref "R119") (pin "1") (pinfunction "1_1") (pintype "passive"))
    )
    (net (code "232") (name "Net-(D5-Pad1)") (class "Default")
      (node (ref "D5") (pin "1") (pinfunction "1_1") (pintype "passive"))
      (node (ref "R120") (pin "1") (pinfunction "1_1") (pintype "passive"))
    )
    (net (code "233") (name "Net-(D6-Pad1)") (class "Default")
      (node (ref "D6") (pin "1") (pinfunction "1_1") (pintype "passive"))
      (node (ref "R121") (pin "1") (pinfunction "1_1") (pintype "passive"))
    )
    (net (code "234") (name "Net-(D7-Pad1)") (class "Default")
      (node (ref "D7") (pin "1") (pinfunction "1_1") (pintype "passive"))
      (node (ref "R122") (pin "1") (pinfunction "1_1") (pintype "passive"))
    )
    (net (code "235") (name "Net-(L1-Pad1)") (class "Default")
      (node (ref "L1") (pin "1") (pinfunction "1_1") (pintype "passive"))
      (node (ref "U1") (pin "2") (pinfunction "Vout_2") (pintype "passive"))
      (node (ref "U1") (pin "4") (pinfunction "Vout_4") (pintype "passive"))
    )
    (net (code "236") (name "Net-(N3-Pad1)") (class "Default")
      (node (ref "N3") (pin "1") (pintype "passive"))
      (node (ref "R10") (pin "2") (pinfunction "2_2") (pintype "passive"))
      (node (ref "R5") (pin "2") (pinfunction "2_2") (pintype "passive"))
    )
    (net (code "237") (name "Net-(N3-Pad2)") (class "Default")
      (node (ref "N3") (pin "2") (pintype "passive"))
      (node (ref "R10") (pin "1") (pinfunction "1_1") (pintype "passive"))
      (node (ref "R8") (pin "2") (pinfunction "2_2") (pintype "passive"))
    )
    (net (code "238") (name "Net-(N3-Pad3)") (class "Default")
      (node (ref "N3") (pin "3") (pintype "passive"))
      (node (ref "R1") (pin "1") (pinfunction "1_1") (pintype "passive"))
      (node (ref "R7") (pin "2") (pinfunction "2_2") (pintype "passive"))
    )
    (net (code "239") (name "Net-(N3-Pad5)") (class "Default")
      (node (ref "N3") (pin "5") (pintype "passive"))
      (node (ref "R12") (pin "1") (pinfunction "1_1") (pintype "passive"))
      (node (ref "R14") (pin "2") (pinfunction "2_2") (pintype "passive"))
    )
    (net (code "240") (name "Net-(N3-Pad6)") (class "Default")
      (node (ref "N3") (pin "6") (pintype "passive"))
      (node (ref "R17") (pin "2") (pinfunction "2_2") (pintype "passive"))
      (node (ref "R19") (pin "1") (pinfunction "1_1") (pintype "passive"))
    )
    (net (code "241") (name "Net-(N3-Pad7)") (class "Default")
      (node (ref "N3") (pin "7") (pintype "passive"))
      (node (ref "R16") (pin "2") (pinfunction "2_2") (pintype "passive"))
      (node (ref "R19") (pin "2") (pinfunction "2_2") (pintype "passive"))
    )
    (net (code "242") (name "Net-(N3-Pad8)") (class "Default")
      (node (ref "N3") (pin "8") (pintype "passive"))
      (node (ref "R25") (pin "2") (pinfunction "2_2") (pintype "passive"))
      (node (ref "R32") (pin "2") (pinfunction "2_2") (pintype "passive"))
    )
    (net (code "243") (name "Net-(N3-Pad9)") (class "Default")
      (node (ref "N3") (pin "9") (pintype "passive"))
      (node (ref "R27") (pin "2") (pinfunction "2_2") (pintype "passive"))
      (node (ref "R32") (pin "1") (pinfunction "1_1") (pintype "passive"))
    )
    (net (code "244") (name "Net-(N3-Pad10)") (class "Default")
      (node (ref "N3") (pin "10") (pintype "passive"))
      (node (ref "R20") (pin "1") (pinfunction "1_1") (pintype "passive"))
      (node (ref "R22") (pin "2") (pinfunction "2_2") (pintype "passive"))
    )
    (net (code "245") (name "Net-(N9-Pad1)") (class "Default")
      (node (ref "N9") (pin "1") (pintype "passive"))
      (node (ref "R36") (pin "2") (pinfunction "2_2") (pintype "passive"))
      (node (ref "R43") (pin "2") (pinfunction "2_2") (pintype "passive"))
    )
    (net (code "246") (name "Net-(N9-Pad2)") (class "Default")
      (node (ref "N9") (pin "2") (pintype "passive"))
      (node (ref "R40") (pin "2") (pinfunction "2_2") (pintype "passive"))
      (node (ref "R43") (pin "1") (pinfunction "1_1") (pintype "passive"))
    )
    (net (code "247") (name "Net-(N9-Pad3)") (class "Default")
      (node (ref "N9") (pin "3") (pintype "passive"))
      (node (ref "R33") (pin "1") (pinfunction "1_1") (pintype "passive"))
      (node (ref "R37") (pin "2") (pinfunction "2_2") (pintype "passive"))
    )
    (net (code "248") (name "Net-(N9-Pad5)") (class "Default")
      (node (ref "N9") (pin "5") (pintype "passive"))
      (node (ref "R46") (pin "1") (pinfunction "1_1") (pintype "passive"))
      (node (ref "R48") (pin "2") (pinfunction "2_2") (pintype "passive"))
    )
    (net (code "249") (name "Net-(N9-Pad6)") (class "Default")
      (node (ref "N9") (pin "6") (pintype "passive"))
      (node (ref "R51") (pin "2") (pinfunction "2_2") (pintype "passive"))
      (node (ref "R55") (pin "1") (pinfunction "1_1") (pintype "passive"))
    )
    (net (code "250") (name "Net-(N9-Pad7)") (class "Default")
      (node (ref "N9") (pin "7") (pintype "passive"))
      (node (ref "R49") (pin "2") (pinfunction "2_2") (pintype "passive"))
      (node (ref "R55") (pin "2") (pinfunction "2_2") (pintype "passive"))
    )
    (net (code "251") (name "Net-(N9-Pad8)") (class "Default")
      (node (ref "N9") (pin "8") (pintype "passive"))
      (node (ref "R62") (pin "2") (pinfunction "2_2") (pintype "passive"))
      (node (ref "R68") (pin "2") (pinfunction "2_2") (pintype "passive"))
    )
    (net (code "252") (name "Net-(N9-Pad9)") (class "Default")
      (node (ref "N9") (pin "9") (pintype "passive"))
      (node (ref "R64") (pin "2") (pinfunction "2_2") (pintype "passive"))
      (node (ref "R68") (pin "1") (pinfunction "1_1") (pintype "passive"))
    )
    (net (code "253") (name "Net-(N9-Pad10)") (class "Default")
      (node (ref "N9") (pin "10") (pintype "passive"))
      (node (ref "R56") (pin "1") (pinfunction "1_1") (pintype "passive"))
      (node (ref "R60") (pin "2") (pinfunction "2_2") (pintype "passive"))
    )
    (net (code "254") (name "Net-(N10-D)") (class "Default")
      (node (ref "N10") (pin "1") (pinfunction "D_1") (pintype "passive"))
      (node (ref "N8") (pin "2") (pinfunction "Ain_2") (pintype "passive"))
      (node (ref "N8") (pin "4") (pinfunction "Bin_4") (pintype "passive"))
      (node (ref "R41") (pin "1") (pinfunction "1_1") (pintype "passive"))
    )
    (net (code "255") (name "Net-(N11-Pad1)") (class "Default")
      (node (ref "N11") (pin "1") (pintype "passive"))
      (node (ref "R38") (pin "2") (pinfunction "2_2") (pintype "passive"))
      (node (ref "R44") (pin "2") (pinfunction "2_2") (pintype "passive"))
    )
    (net (code "256") (name "Net-(N11-Pad2)") (class "Default")
      (node (ref "N11") (pin "2") (pintype "passive"))
      (node (ref "R42") (pin "2") (pinfunction "2_2") (pintype "passive"))
      (node (ref "R44") (pin "1") (pinfunction "1_1") (pintype "passive"))
    )
    (net (code "257") (name "Net-(N11-Pad3)") (class "Default")
      (node (ref "N11") (pin "3") (pintype "passive"))
      (node (ref "R34") (pin "1") (pinfunction "1_1") (pintype "passive"))
      (node (ref "R39") (pin "2") (pinfunction "2_2") (pintype "passive"))
    )
    (net (code "258") (name "Net-(N11-Pad5)") (class "Default")
      (node (ref "N11") (pin "5") (pintype "passive"))
      (node (ref "R47") (pin "1") (pinfunction "1_1") (pintype "passive"))
      (node (ref "R50") (pin "2") (pinfunction "2_2") (pintype "passive"))
    )
    (net (code "259") (name "Net-(N11-Pad6)") (class "Default")
      (node (ref "N11") (pin "6") (pintype "passive"))
      (node (ref "R53") (pin "2") (pinfunction "2_2") (pintype "passive"))
      (node (ref "R57") (pin "1") (pinfunction "1_1") (pintype "passive"))
    )
    (net (code "260") (name "Net-(N11-Pad7)") (class "Default")
      (node (ref "N11") (pin "7") (pintype "passive"))
      (node (ref "R52") (pin "2") (pinfunction "2_2") (pintype "passive"))
      (node (ref "R57") (pin "2") (pinfunction "2_2") (pintype "passive"))
    )
    (net (code "261") (name "Net-(N11-Pad8)") (class "Default")
      (node (ref "N11") (pin "8") (pintype "passive"))
      (node (ref "R65") (pin "2") (pinfunction "2_2") (pintype "passive"))
      (node (ref "R70") (pin "2") (pinfunction "2_2") (pintype "passive"))
    )
    (net (code "262") (name "Net-(N11-Pad9)") (class "Default")
      (node (ref "N11") (pin "9") (pintype "passive"))
      (node (ref "R66") (pin "2") (pinfunction "2_2") (pintype "passive"))
      (node (ref "R70") (pin "1") (pinfunction "1_1") (pintype "passive"))
    )
    (net (code "263") (name "Net-(N11-Pad10)") (class "Default")
      (node (ref "N11") (pin "10") (pintype "passive"))
      (node (ref "R59") (pin "1") (pinfunction "1_1") (pintype "passive"))
      (node (ref "R63") (pin "2") (pinfunction "2_2") (pintype "passive"))
    )
    (net (code "264") (name "Net-(N14-Pad1)") (class "Default")
      (node (ref "N14") (pin "1") (pintype "passive"))
      (node (ref "R129") (pin "2") (pinfunction "2_2") (pintype "passive"))
      (node (ref "R130") (pin "2") (pinfunction "2_2") (pintype "passive"))
    )
    (net (code "265") (name "Net-(N14-Pad2)") (class "Default")
      (node (ref "N14") (pin "2") (pintype "passive"))
      (node (ref "R128") (pin "2") (pinfunction "2_2") (pintype "passive"))
      (node (ref "R129") (pin "1") (pinfunction "1_1") (pintype "passive"))
    )
    (net (code "266") (name "Net-(N14-Pad3)") (class "Default")
      (node (ref "N14") (pin "3") (pintype "passive"))
      (node (ref "R105") (pin "1") (pinfunction "1_1") (pintype "passive"))
      (node (ref "R141") (pin "2") (pinfunction "2_2") (pintype "passive"))
    )
    (net (code "267") (name "Net-(N14-Pad5)") (class "Default")
      (node (ref "N14") (pin "5") (pintype "passive"))
      (node (ref "R131") (pin "1") (pinfunction "1_1") (pintype "passive"))
      (node (ref "R132") (pin "2") (pinfunction "2_2") (pintype "passive"))
    )
    (net (code "268") (name "Net-(N14-Pad6)") (class "Default")
      (node (ref "N14") (pin "6") (pintype "passive"))
      (node (ref "R133") (pin "2") (pinfunction "2_2") (pintype "passive"))
      (node (ref "R135") (pin "1") (pinfunction "1_1") (pintype "passive"))
    )
    (net (code "269") (name "Net-(N14-Pad7)") (class "Default")
      (node (ref "N14") (pin "7") (pintype "passive"))
      (node (ref "R135") (pin "2") (pinfunction "2_2") (pintype "passive"))
      (node (ref "R136") (pin "2") (pinfunction "2_2") (pintype "passive"))
    )
    (net (code "270") (name "Net-(N14-Pad8)") (class "Default")
      (node (ref "N14") (pin "8") (pintype "passive"))
      (node (ref "R139") (pin "2") (pinfunction "2_2") (pintype "passive"))
      (node (ref "R140") (pin "2") (pinfunction "2_2") (pintype "passive"))
    )
    (net (code "271") (name "Net-(N14-Pad9)") (class "Default")
      (node (ref "N14") (pin "9") (pintype "passive"))
      (node (ref "R138") (pin "2") (pinfunction "2_2") (pintype "passive"))
      (node (ref "R139") (pin "1") (pinfunction "1_1") (pintype "passive"))
    )
    (net (code "272") (name "Net-(N14-Pad10)") (class "Default")
      (node (ref "N14") (pin "10") (pintype "passive"))
      (node (ref "R134") (pin "1") (pinfunction "1_1") (pintype "passive"))
      (node (ref "R137") (pin "2") (pinfunction "2_2") (pintype "passive"))
    )
    (net (code "273") (name "Net-(N16-V+)") (class "Default")
      (node (ref "C66") (pin "2") (pinfunction "2_2") (pintype "passive"))
      (node (ref "N16") (pin "2") (pinfunction "V+_2") (pintype "passive"))
      (node (ref "R86") (pin "1") (pinfunction "1_1") (pintype "passive"))
      (node (ref "R90") (pin "1") (pinfunction "1_1") (pintype "passive"))
    )
    (net (code "274") (name "Net-(N18-REFAB)") (class "Default")
      (node (ref "C86") (pin "1") (pintype "passive"))
      (node (ref "C87") (pin "1") (pintype "passive"))
      (node (ref "C88") (pin "2") (pinfunction "2_2") (pintype "passive"))
      (node (ref "N18") (pin "12") (pinfunction "REFCD_12") (pintype "passive"))
      (node (ref "N18") (pin "5") (pinfunction "REFAB_5") (pintype "passive"))
      (node (ref "N19") (pin "6") (pinfunction "OUT_6") (pintype "passive"))
    )
    (net (code "275") (name "Net-(N21-IN7)") (class "Default")
      (node (ref "N21") (pin "7") (pinfunction "IN7_7") (pintype "passive"))
      (node (ref "R125") (pin "2") (pinfunction "2_2") (pintype "passive"))
      (node (ref "V33") (pin "E") (pinfunction "E_E") (pintype "passive"))
    )
    (net (code "276") (name "Net-(N21-OUT1)") (class "Default")
      (node (ref "N21") (pin "16") (pinfunction "OUT1_16") (pintype "passive"))
      (node (ref "VR2") (pin "1") (pinfunction "1_1") (pintype "passive"))
    )
    (net (code "277") (name "Net-(N21-OUT2)") (class "Default")
      (node (ref "N21") (pin "15") (pinfunction "OUT2_15") (pintype "passive"))
      (node (ref "VR2") (pin "2") (pinfunction "2_2") (pintype "passive"))
    )
    (net (code "278") (name "Net-(N21-OUT3)") (class "Default")
      (node (ref "N21") (pin "14") (pinfunction "OUT3_14") (pintype "passive"))
      (node (ref "VR2") (pin "3") (pinfunction "3_3") (pintype "passive"))
    )
    (net (code "279") (name "Net-(N21-OUT4)") (class "Default")
      (node (ref "N21") (pin "13") (pinfunction "OUT4_13") (pintype "passive"))
      (node (ref "VR2") (pin "4") (pinfunction "4_4") (pintype "passive"))
    )
    (net (code "280") (name "Net-(N21-OUT5)") (class "Default")
      (node (ref "N21") (pin "12") (pinfunction "OUT5_12") (pintype "passive"))
      (node (ref "VR4") (pin "1") (pinfunction "1_1") (pintype "passive"))
    )
    (net (code "281") (name "Net-(N21-OUT6)") (class "Default")
      (node (ref "N21") (pin "11") (pinfunction "OUT6_11") (pintype "passive"))
      (node (ref "VR4") (pin "2") (pinfunction "2_2") (pintype "passive"))
    )
    (net (code "282") (name "Net-(N21-OUT7)") (class "Default")
      (node (ref "N21") (pin "10") (pinfunction "OUT7_10") (pintype "passive"))
      (node (ref "VR4") (pin "3") (pinfunction "3_3") (pintype "passive"))
      (node (ref "VR4") (pin "4") (pinfunction "4_4") (pintype "passive"))
    )
    (net (code "283") (name "Net-(N24-VO)") (class "Default")
      (node (ref "N24") (pin "5") (pinfunction "VO_5") (pintype "passive"))
      (node (ref "R116") (pin "2") (pinfunction "2_2") (pintype "passive"))
    )
    (net (code "284") (name "Net-(N26-OUT4)") (class "Default")
      (node (ref "N26") (pin "13") (pinfunction "OUT4_13") (pintype "passive"))
      (node (ref "VR5") (pin "1") (pinfunction "1_1") (pintype "passive"))
    )
    (net (code "285") (name "Net-(N26-OUT5)") (class "Default")
      (node (ref "N26") (pin "12") (pinfunction "OUT5_12") (pintype "passive"))
      (node (ref "VR5") (pin "2") (pinfunction "2_2") (pintype "passive"))
    )
    (net (code "286") (name "Net-(P4-Pad1)") (class "Default")
      (node (ref "P4") (pin "1") (pinfunction "1_1") (pintype "passive"))
      (node (ref "P4") (pin "3") (pinfunction "3_3") (pintype "passive"))
      (node (ref "P4") (pin "5") (pinfunction "5_5") (pintype "passive"))
      (node (ref "P4") (pin "7") (pinfunction "7_7") (pintype "passive"))
    )
    (net (code "287") (name "Net-(R87-Pad2)") (class "Default")
      (node (ref "R87") (pin "2") (pinfunction "2_2") (pintype "passive"))
      (node (ref "R92") (pin "2") (pinfunction "2_2") (pintype "passive"))
      (node (ref "U5") (pin "5") (pintype "passive"))
    )
    (net (code "288") (name "Net-(R103-Pad1)") (class "Default")
      (node (ref "R103") (pin "1") (pinfunction "1_1") (pintype "passive"))
      (node (ref "R98") (pin "2") (pinfunction "2_2") (pintype "passive"))
      (node (ref "U5") (pin "6") (pintype "passive"))
    )
    (net (code "289") (name "Net-(R124-Pad1)") (class "Default")
      (node (ref "R124") (pin "1") (pinfunction "1_1") (pintype "passive"))
      (node (ref "V33") (pin "B") (pinfunction "B_B") (pintype "input"))
    )
    (net (code "290") (name "Net-(V3-K)") (class "Default")
      (node (ref "R5") (pin "1") (pinfunction "1_1") (pintype "passive"))
      (node (ref "V3") (pin "2") (pinfunction "K_2") (pintype "passive"))
    )
    (net (code "291") (name "Net-(V18-K)") (class "Default")
      (node (ref "C58") (pin "1") (pinfunction "1_1") (pintype "passive"))
      (node (ref "R75") (pin "2") (pinfunction "2_2") (pintype "passive"))
      (node (ref "R76") (pin "1") (pinfunction "1_1") (pintype "passive"))
      (node (ref "R80") (pin "1") (pinfunction "1_1") (pintype "passive"))
      (node (ref "V18") (pin "2") (pinfunction "K_2") (pintype "passive"))
    )
    (net (code "292") (name "Net-(XS23-Pad1)") (class "Default")
      (node (ref "XS23") (pin "1") (pinfunction "1_1") (pintype "passive"))
      (node (ref "XS27") (pin "1") (pinfunction "1_1") (pintype "passive"))
    )
    (net (code "293") (name "Net-(XS23-Pad2)") (class "Default")
      (node (ref "XS23") (pin "2") (pinfunction "2_2") (pintype "passive"))
      (node (ref "XS27") (pin "2") (pinfunction "2_2") (pintype "passive"))
    )
    (net (code "294") (name "RS485_A") (class "Default")
      (node (ref "C100") (pin "1") (pinfunction "1_1") (pintype "passive"))
      (node (ref "C104") (pin "1") (pinfunction "1_1") (pintype "passive"))
      (node (ref "N23") (pin "12") (pinfunction "A_12") (pintype "passive"))
      (node (ref "R110") (pin "2") (pinfunction "2_2") (pintype "passive"))
      (node (ref "R112") (pin "1") (pintype "passive"))
      (node (ref "V30") (pin "K") (pintype "passive"))
      (node (ref "XS15") (pin "1") (pinfunction "1_1") (pintype "passive"))
    )
    (net (code "295") (name "RS485_B") (class "Default")
      (node (ref "C100") (pin "2") (pinfunction "2_2") (pintype "passive"))
      (node (ref "C103") (pin "1") (pinfunction "1_1") (pintype "passive"))
      (node (ref "N23") (pin "13") (pinfunction "B_13") (pintype "passive"))
      (node (ref "R112") (pin "2") (pintype "passive"))
      (node (ref "R117") (pin "1") (pinfunction "1_1") (pintype "passive"))
      (node (ref "V31") (pin "K") (pintype "passive"))
      (node (ref "XS15") (pin "2") (pinfunction "2_2") (pintype "passive"))
    )
    (net (code "296") (name "RXD2") (class "Default")
      (node (ref "D4") (pin "2") (pinfunction "2_2") (pintype "passive"))
      (node (ref "U2") (pin "37") (pinfunction "PA3_37") (pintype "bidirectional"))
      (node (ref "U4") (pin "3") (pinfunction "RxD_3") (pintype "passive"))
    )
    (net (code "297") (name "TXD2") (class "Default")
      (node (ref "D7") (pin "2") (pinfunction "2_2") (pintype "passive"))
      (node (ref "U2") (pin "36") (pinfunction "PA2_36") (pintype "bidirectional"))
      (node (ref "U4") (pin "6") (pinfunction "TxD_6") (pintype "passive"))
    )
    (net (code "298") (name "VDD") (class "Default")
      (node (ref "C10") (pin "1") (pinfunction "1_1") (pintype "passive"))
      (node (ref "C30") (pin "1") (pinfunction "1_1") (pintype "passive"))
      (node (ref "C31") (pin "1") (pinfunction "1_1") (pintype "passive"))
      (node (ref "C32") (pin "1") (pinfunction "1_1") (pintype "passive"))
      (node (ref "C33") (pin "1") (pinfunction "1_1") (pintype "passive"))
      (node (ref "C34") (pin "1") (pinfunction "1_1") (pintype "passive"))
      (node (ref "C35") (pin "1") (pinfunction "1_1") (pintype "passive"))
      (node (ref "C36") (pin "1") (pinfunction "1_1") (pintype "passive"))
      (node (ref "C37") (pin "1") (pinfunction "1_1") (pintype "passive"))
      (node (ref "C38") (pin "1") (pinfunction "1_1") (pintype "passive"))
      (node (ref "C39") (pin "1") (pinfunction "1_1") (pintype "passive"))
      (node (ref "C4") (pin "1") (pinfunction "1_1") (pintype "passive"))
      (node (ref "C40") (pin "1") (pinfunction "1_1") (pintype "passive"))
      (node (ref "C41") (pin "1") (pinfunction "1_1") (pintype "passive"))
      (node (ref "C96") (pin "1") (pinfunction "1_1") (pintype "passive"))
      (node (ref "C98") (pin "1") (pintype "passive"))
      (node (ref "L1") (pin "2") (pinfunction "2_2") (pintype "passive"))
      (node (ref "N23") (pin "4") (pinfunction "VDD1_4") (pintype "passive"))
      (node (ref "R106") (pin "2") (pinfunction "2_2") (pintype "passive"))
      (node (ref "R108") (pin "1") (pinfunction "1_1") (pintype "passive"))
      (node (ref "R119") (pin "2") (pinfunction "2_2") (pintype "passive"))
      (node (ref "R120") (pin "2") (pinfunction "2_2") (pintype "passive"))
      (node (ref "R121") (pin "2") (pinfunction "2_2") (pintype "passive"))
      (node (ref "R122") (pin "2") (pinfunction "2_2") (pintype "passive"))
      (node (ref "R93") (pin "1") (pinfunction "1_1") (pintype "passive"))
      (node (ref "R94") (pin "1") (pinfunction "1_1") (pintype "passive"))
      (node (ref "R95") (pin "1") (pinfunction "1_1") (pintype "passive"))
      (node (ref "R96") (pin "1") (pinfunction "1_1") (pintype "passive"))
      (node (ref "U2") (pin "108") (pinfunction "VDD_2_108") (pintype "power_in"))
      (node (ref "U2") (pin "121") (pinfunction "VDD_10_121") (pintype "power_in"))
      (node (ref "U2") (pin "131") (pinfunction "VDD_11_131") (pintype "power_in"))
      (node (ref "U2") (pin "144") (pinfunction "VDD_3_144") (pintype "power_in"))
      (node (ref "U2") (pin "17") (pinfunction "VDD_5_17") (pintype "power_in"))
      (node (ref "U2") (pin "33") (pinfunction "VDDA_33") (pintype "power_in"))
      (node (ref "U2") (pin "39") (pinfunction "VDD_4_39") (pintype "power_in"))
      (node (ref "U2") (pin "52") (pinfunction "VDD_6_52") (pintype "power_in"))
      (node (ref "U2") (pin "62") (pinfunction "VDD_7_62") (pintype "power_in"))
      (node (ref "U2") (pin "72") (pinfunction "VDD_1_72") (pintype "power_in"))
      (node (ref "U2") (pin "84") (pinfunction "VDD_8_84") (pintype "power_in"))
      (node (ref "U2") (pin "95") (pinfunction "VDD_9_95") (pintype "power_in"))
      (node (ref "U4") (pin "1") (pinfunction "VDD1_1") (pintype "passive"))
      (node (ref "XS6") (pin "1") (pinfunction "1_1") (pintype "passive"))
      (node (ref "XS6") (pin "2") (pinfunction "2_2") (pintype "passive"))
    )
    (net (code "299") (name "unconnected-(N8-NC-Pad1)") (class "Default")
      (node (ref "N8") (pin "1") (pinfunction "NC_1") (pintype "passive"))
    )
    (net (code "300") (name "unconnected-(N8-NC-Pad8)") (class "Default")
      (node (ref "N8") (pin "8") (pinfunction "NC_8") (pintype "passive"))
    )
    (net (code "301") (name "unconnected-(N12-I.C-Pad1)") (class "Default")
      (node (ref "N12") (pin "1") (pinfunction "I.C_1") (pintype "passive"))
    )
    (net (code "302") (name "unconnected-(N12-I.C-Pad7)") (class "Default")
      (node (ref "N12") (pin "7") (pinfunction "I.C_7") (pintype "passive"))
    )
    (net (code "303") (name "unconnected-(N12-I.C-Pad8)") (class "Default")
      (node (ref "N12") (pin "8") (pinfunction "I.C_8") (pintype "passive"))
    )
    (net (code "304") (name "unconnected-(N12-NC-Pad3)") (class "Default")
      (node (ref "N12") (pin "3") (pinfunction "NC_3") (pintype "passive"))
    )
    (net (code "305") (name "unconnected-(N12-TRIM-Pad5)") (class "Default")
      (node (ref "N12") (pin "5") (pinfunction "TRIM_5") (pintype "passive"))
    )
    (net (code "306") (name "unconnected-(N16-NC-Pad1)") (class "Default")
      (node (ref "N16") (pin "1") (pinfunction "NC_1") (pintype "passive"))
    )
    (net (code "307") (name "unconnected-(N16-NC-Pad4)") (class "Default")
      (node (ref "N16") (pin "4") (pinfunction "NC_4") (pintype "passive"))
    )
    (net (code "308") (name "unconnected-(N16-VE-Pad7)") (class "Default")
      (node (ref "N16") (pin "7") (pinfunction "VE_7") (pintype "passive"))
    )
    (net (code "309") (name "unconnected-(N18-SDO-Pad11)") (class "Default")
      (node (ref "N18") (pin "11") (pinfunction "SDO_11") (pintype "passive"))
    )
    (net (code "310") (name "unconnected-(N19-I.C-Pad1)") (class "Default")
      (node (ref "N19") (pin "1") (pinfunction "I.C_1") (pintype "passive"))
    )
    (net (code "311") (name "unconnected-(N19-I.C-Pad7)") (class "Default")
      (node (ref "N19") (pin "7") (pinfunction "I.C_7") (pintype "passive"))
    )
    (net (code "312") (name "unconnected-(N19-I.C-Pad8)") (class "Default")
      (node (ref "N19") (pin "8") (pinfunction "I.C_8") (pintype "passive"))
    )
    (net (code "313") (name "unconnected-(N19-NC-Pad3)") (class "Default")
      (node (ref "N19") (pin "3") (pinfunction "NC_3") (pintype "passive"))
    )
    (net (code "314") (name "unconnected-(N19-TRIM-Pad5)") (class "Default")
      (node (ref "N19") (pin "5") (pinfunction "TRIM_5") (pintype "passive"))
    )
    (net (code "315") (name "unconnected-(N23-D1-Pad1)") (class "Default")
      (node (ref "N23") (pin "1") (pinfunction "D1_1") (pintype "passive"))
    )
    (net (code "316") (name "unconnected-(N23-D2-Pad2)") (class "Default")
      (node (ref "N23") (pin "2") (pinfunction "D2_2") (pintype "passive"))
    )
    (net (code "317") (name "unconnected-(N23-DE_OUT-Pad10)") (class "Default")
      (node (ref "N23") (pin "10") (pinfunction "DE_OUT_10") (pintype "passive"))
    )
    (net (code "318") (name "unconnected-(N24-NC-Pad2)") (class "Default")
      (node (ref "N24") (pin "2") (pinfunction "NC_2") (pintype "passive"))
    )
    (net (code "319") (name "unconnected-(N25-A-Pad7)") (class "Default")
      (node (ref "N25") (pin "7") (pinfunction "A_7") (pintype "passive"))
    )
    (net (code "320") (name "unconnected-(N25-C-Pad10)") (class "Default")
      (node (ref "N25") (pin "10") (pinfunction "C_10") (pintype "passive"))
    )
    (net (code "321") (name "unconnected-(N25-E-Pad9)") (class "Default")
      (node (ref "N25") (pin "9") (pinfunction "E_9") (pintype "passive"))
    )
    (net (code "322") (name "unconnected-(N25-K-Pad8)") (class "Default")
      (node (ref "N25") (pin "8") (pinfunction "K_8") (pintype "passive"))
    )
    (net (code "323") (name "unconnected-(N26-IN3-Pad3)") (class "Default")
      (node (ref "N26") (pin "3") (pinfunction "IN3_3") (pintype "passive"))
    )
    (net (code "324") (name "unconnected-(N26-IN6-Pad6)") (class "Default")
      (node (ref "N26") (pin "6") (pinfunction "IN6_6") (pintype "passive"))
    )
    (net (code "325") (name "unconnected-(N26-IN7-Pad7)") (class "Default")
      (node (ref "N26") (pin "7") (pinfunction "IN7_7") (pintype "passive"))
    )
    (net (code "326") (name "unconnected-(N26-OUT3-Pad14)") (class "Default")
      (node (ref "N26") (pin "14") (pinfunction "OUT3_14") (pintype "passive"))
    )
    (net (code "327") (name "unconnected-(N26-OUT6-Pad11)") (class "Default")
      (node (ref "N26") (pin "11") (pinfunction "OUT6_11") (pintype "passive"))
    )
    (net (code "328") (name "unconnected-(N26-OUT7-Pad10)") (class "Default")
      (node (ref "N26") (pin "10") (pinfunction "OUT7_10") (pintype "passive"))
    )
    (net (code "329") (name "unconnected-(R2-Pad2)") (class "Default")
      (node (ref "R2") (pin "2") (pinfunction "2_2") (pintype "passive"))
    )
    (net (code "330") (name "unconnected-(R23-Pad2)") (class "Default")
      (node (ref "R23") (pin "2") (pinfunction "2_2") (pintype "passive"))
    )
    (net (code "331") (name "unconnected-(R115-Pad1)") (class "Default")
      (node (ref "R115") (pin "1") (pinfunction "1_1") (pintype "passive"))
    )
    (net (code "332") (name "unconnected-(R137-Pad1)") (class "Default")
      (node (ref "R137") (pin "1") (pinfunction "1_1") (pintype "passive"))
    )
    (net (code "333") (name "unconnected-(RL1-Pad3)") (class "Default")
      (node (ref "RL1") (pin "3") (pinfunction "3_3") (pintype "passive"))
    )
    (net (code "334") (name "unconnected-(U2A-PA1-Pad35)") (class "Default")
      (node (ref "U2") (pin "35") (pinfunction "PA1_35") (pintype "bidirectional"))
    )
    (net (code "335") (name "unconnected-(U2A-PA7-Pad43)") (class "Default")
      (node (ref "U2") (pin "43") (pinfunction "PA7_43") (pintype "bidirectional"))
    )
    (net (code "336") (name "unconnected-(U2A-PA8-Pad100)") (class "Default")
      (node (ref "U2") (pin "100") (pinfunction "PA8_100") (pintype "bidirectional"))
    )
    (net (code "337") (name "unconnected-(U2A-PB5-Pad135)") (class "Default")
      (node (ref "U2") (pin "135") (pinfunction "PB5_135") (pintype "bidirectional"))
    )
    (net (code "338") (name "unconnected-(U2A-PB10-Pad69)") (class "Default")
      (node (ref "U2") (pin "69") (pinfunction "PB10_69") (pintype "bidirectional"))
    )
    (net (code "339") (name "unconnected-(U2A-PB11-Pad70)") (class "Default")
      (node (ref "U2") (pin "70") (pinfunction "PB11_70") (pintype "bidirectional"))
    )
    (net (code "340") (name "unconnected-(U2A-PB15-Pad76)") (class "Default")
      (node (ref "U2") (pin "76") (pinfunction "PB15_76") (pintype "bidirectional"))
    )
    (net (code "341") (name "unconnected-(U2A-PC6-Pad96)") (class "Default")
      (node (ref "U2") (pin "96") (pinfunction "PC6_96") (pintype "bidirectional"))
    )
    (net (code "342") (name "unconnected-(U2A-PC7-Pad97)") (class "Default")
      (node (ref "U2") (pin "97") (pinfunction "PC7_97") (pintype "bidirectional"))
    )
    (net (code "343") (name "unconnected-(U2A-PC8-Pad98)") (class "Default")
      (node (ref "U2") (pin "98") (pinfunction "PC8_98") (pintype "bidirectional"))
    )
    (net (code "344") (name "unconnected-(U2A-PC9-Pad99)") (class "Default")
      (node (ref "U2") (pin "99") (pinfunction "PC9_99") (pintype "bidirectional"))
    )
    (net (code "345") (name "unconnected-(U2A-PC11-Pad112)") (class "Default")
      (node (ref "U2") (pin "112") (pinfunction "PC11_112") (pintype "bidirectional"))
    )
    (net (code "346") (name "unconnected-(U2A-PC12-Pad113)") (class "Default")
      (node (ref "U2") (pin "113") (pinfunction "PC12_113") (pintype "bidirectional"))
    )
    (net (code "347") (name "unconnected-(U2A-PC13-TAMPER-RTC-Pad7)") (class "Default")
      (node (ref "U2") (pin "7") (pinfunction "PC13-TAMPER-RTC_7") (pintype "bidirectional"))
    )
    (net (code "348") (name "unconnected-(U2A-PC14-OSC32_IN-Pad8)") (class "Default")
      (node (ref "U2") (pin "8") (pinfunction "PC14-OSC32_IN_8") (pintype "bidirectional"))
    )
    (net (code "349") (name "unconnected-(U2A-PC15-OSC32_OUT-Pad9)") (class "Default")
      (node (ref "U2") (pin "9") (pinfunction "PC15-OSC32_OUT_9") (pintype "bidirectional"))
    )
    (net (code "350") (name "unconnected-(U2A-PD9-Pad78)") (class "Default")
      (node (ref "U2") (pin "78") (pinfunction "PD9_78") (pintype "bidirectional"))
    )
    (net (code "351") (name "unconnected-(U2A-PD10-Pad79)") (class "Default")
      (node (ref "U2") (pin "79") (pinfunction "PD10_79") (pintype "bidirectional"))
    )
    (net (code "352") (name "unconnected-(U2A-PD11-Pad80)") (class "Default")
      (node (ref "U2") (pin "80") (pinfunction "PD11_80") (pintype "bidirectional"))
    )
    (net (code "353") (name "unconnected-(U2A-PD12-Pad81)") (class "Default")
      (node (ref "U2") (pin "81") (pinfunction "PD12_81") (pintype "bidirectional"))
    )
    (net (code "354") (name "unconnected-(U2A-PD13-Pad82)") (class "Default")
      (node (ref "U2") (pin "82") (pinfunction "PD13_82") (pintype "bidirectional"))
    )
    (net (code "355") (name "unconnected-(U2A-PD14-Pad85)") (class "Default")
      (node (ref "U2") (pin "85") (pinfunction "PD14_85") (pintype "bidirectional"))
    )
    (net (code "356") (name "unconnected-(U2A-PE7-Pad58)") (class "Default")
      (node (ref "U2") (pin "58") (pinfunction "PE7_58") (pintype "bidirectional"))
    )
    (net (code "357") (name "unconnected-(U2A-PE8-Pad59)") (class "Default")
      (node (ref "U2") (pin "59") (pinfunction "PE8_59") (pintype "bidirectional"))
    )
    (net (code "358") (name "unconnected-(U2A-PE9-Pad60)") (class "Default")
      (node (ref "U2") (pin "60") (pinfunction "PE9_60") (pintype "bidirectional"))
    )
    (net (code "359") (name "unconnected-(U2A-PE10-Pad63)") (class "Default")
      (node (ref "U2") (pin "63") (pinfunction "PE10_63") (pintype "bidirectional"))
    )
    (net (code "360") (name "unconnected-(U2A-PE11-Pad64)") (class "Default")
      (node (ref "U2") (pin "64") (pinfunction "PE11_64") (pintype "bidirectional"))
    )
    (net (code "361") (name "unconnected-(U2A-PE12-Pad65)") (class "Default")
      (node (ref "U2") (pin "65") (pinfunction "PE12_65") (pintype "bidirectional"))
    )
    (net (code "362") (name "unconnected-(U2A-PE13-Pad66)") (class "Default")
      (node (ref "U2") (pin "66") (pinfunction "PE13_66") (pintype "bidirectional"))
    )
    (net (code "363") (name "unconnected-(U2A-PE14-Pad67)") (class "Default")
      (node (ref "U2") (pin "67") (pinfunction "PE14_67") (pintype "bidirectional"))
    )
    (net (code "364") (name "unconnected-(U2A-PE15-Pad68)") (class "Default")
      (node (ref "U2") (pin "68") (pinfunction "PE15_68") (pintype "bidirectional"))
    )
    (net (code "365") (name "unconnected-(U2A-PF11-Pad49)") (class "Default")
      (node (ref "U2") (pin "49") (pinfunction "PF11_49") (pintype "bidirectional"))
    )
    (net (code "366") (name "unconnected-(U2A-PG0-Pad56)") (class "Default")
      (node (ref "U2") (pin "56") (pinfunction "PG0_56") (pintype "bidirectional"))
    )
    (net (code "367") (name "unconnected-(U2A-PG1-Pad57)") (class "Default")
      (node (ref "U2") (pin "57") (pinfunction "PG1_57") (pintype "bidirectional"))
    )
    (net (code "368") (name "unconnected-(U2A-PG2-Pad87)") (class "Default")
      (node (ref "U2") (pin "87") (pinfunction "PG2_87") (pintype "bidirectional"))
    )
    (net (code "369") (name "unconnected-(U2B-NC-Pad106)") (class "Default")
      (node (ref "U2") (pin "106") (pinfunction "NC_106") (pintype "passive"))
    )
    (net (code "370") (name "unconnected-(U2B-VBAT-Pad6)") (class "Default")
      (node (ref "U2") (pin "6") (pinfunction "VBAT_6") (pintype "power_in"))
    )
    (net (code "371") (name "unconnected-(U4-GND2-Pad15)") (class "Default")
      (node (ref "U4") (pin "15") (pinfunction "GND2_15") (pintype "passive"))
    )
    (net (code "372") (name "unconnected-(U4-NC-Pad4)") (class "Default")
      (node (ref "U4") (pin "4") (pinfunction "NC_4") (pintype "passive"))
    )
    (net (code "373") (name "unconnected-(U4-NC-Pad7)") (class "Default")
      (node (ref "U4") (pin "7") (pinfunction "NC_7") (pintype "passive"))
    )
    (net (code "374") (name "unconnected-(U4-NC-Pad12)") (class "Default")
      (node (ref "U4") (pin "12") (pinfunction "NC_12") (pintype "passive"))
    )
    (net (code "375") (name "unconnected-(U5-Pad1)") (class "Default")
      (node (ref "U5") (pin "1") (pintype "passive"))
    )
    (net (code "376") (name "unconnected-(U5-Pad2)") (class "Default")
      (node (ref "U5") (pin "2") (pintype "passive"))
    )
    (net (code "377") (name "unconnected-(U5-Pad3)") (class "Default")
      (node (ref "U5") (pin "3") (pintype "passive"))
    )
    (net (code "378") (name "unconnected-(VR5-Pad3)") (class "Default")
      (node (ref "VR5") (pin "3") (pinfunction "3_3") (pintype "passive"))
    )
    (net (code "379") (name "unconnected-(VR5-Pad4)") (class "Default")
      (node (ref "VR5") (pin "4") (pinfunction "4_4") (pintype "passive"))
    )
    (net (code "380") (name "unconnected-(VR5-Pad5)") (class "Default")
      (node (ref "VR5") (pin "5") (pinfunction "5_5") (pintype "passive"))
    )
    (net (code "381") (name "unconnected-(VR5-Pad6)") (class "Default")
      (node (ref "VR5") (pin "6") (pinfunction "6_6") (pintype "passive"))
    )
    (net (code "382") (name "unconnected-(XS6-Pad6)") (class "Default")
      (node (ref "XS6") (pin "6") (pinfunction "6_6") (pintype "passive"))
    )
    (net (code "383") (name "unconnected-(XS29-Pad1)") (class "Default")
      (node (ref "XS29") (pin "1") (pinfunction "1_1") (pintype "passive"))
    )
    (net (code "384") (name "unconnected-(XS29-Pad3)") (class "Default")
      (node (ref "XS29") (pin "3") (pinfunction "3_3") (pintype "passive"))
    )
    (net (code "385") (name "unconnected-(XS29-Pad4)") (class "Default")
      (node (ref "XS29") (pin "4") (pinfunction "4_4") (pintype "passive"))
    )
    (net (code "386") (name "unconnected-(XS29-Pad5)") (class "Default")
      (node (ref "XS29") (pin "5") (pinfunction "5_5") (pintype "passive"))
    )
    (net (code "387") (name "unconnected-(XS29-Pad6)") (class "Default")
      (node (ref "XS29") (pin "6") (pinfunction "6_6") (pintype "passive"))
    )
    (net (code "388") (name "unconnected-(XS29-Pad7)") (class "Default")
      (node (ref "XS29") (pin "7") (pinfunction "7_7") (pintype "passive"))
    )
  )
)
